# PulseRain_M10.net
KiCad netlist of a schematic drawn in EAGLE
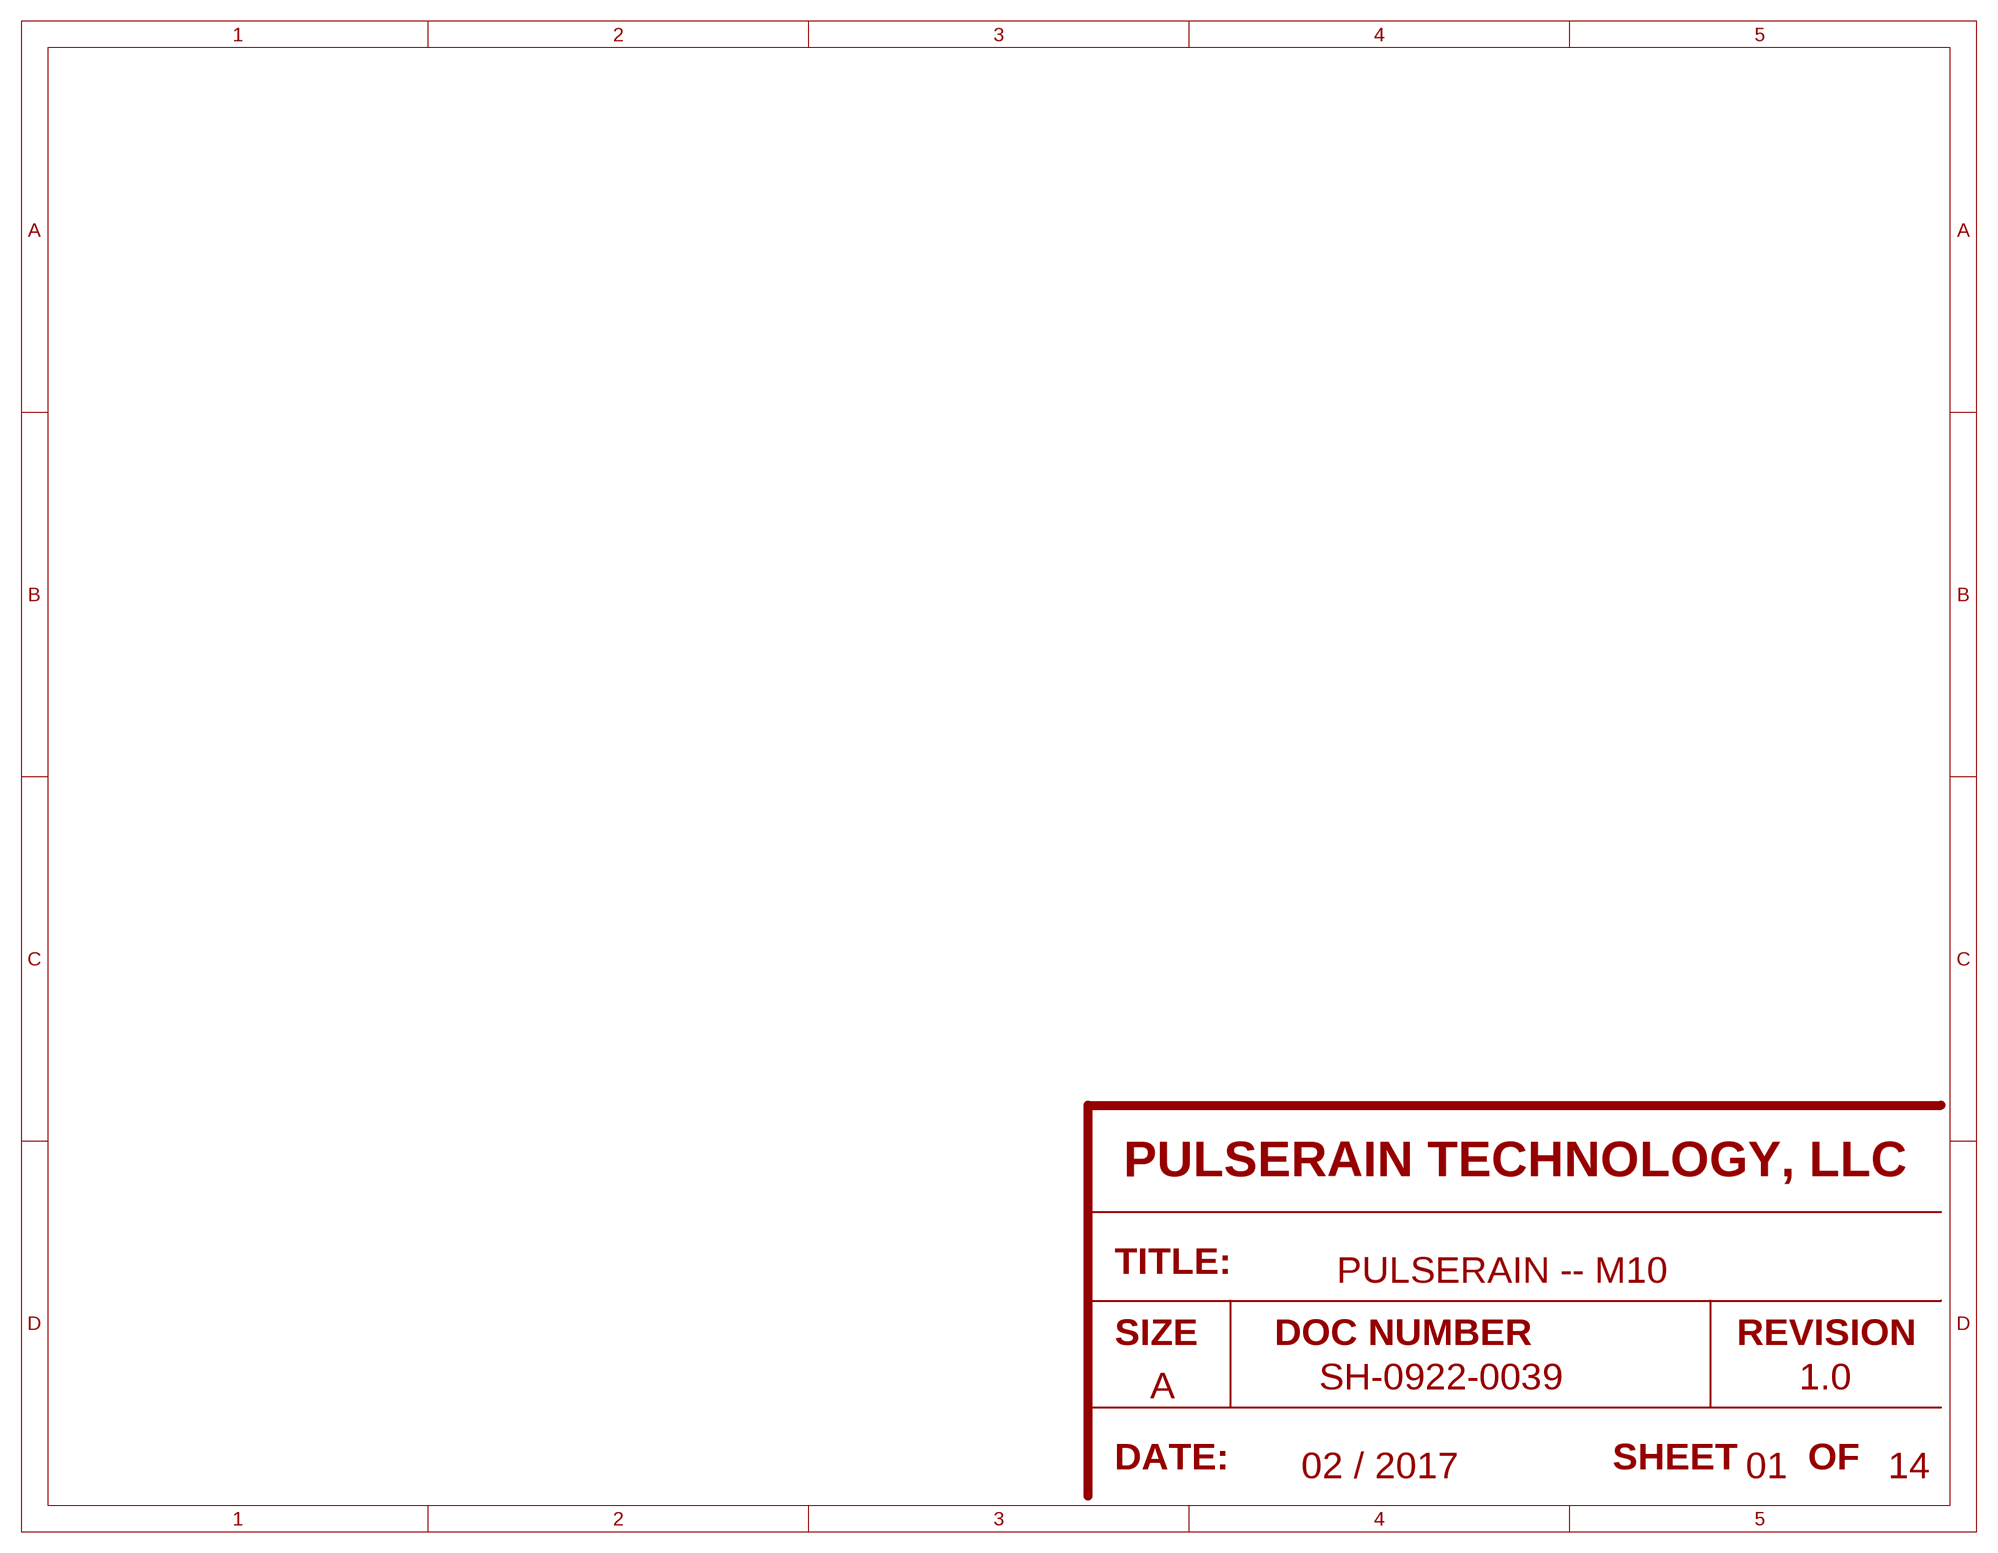
[diagram p0: schematic, sheet 1]
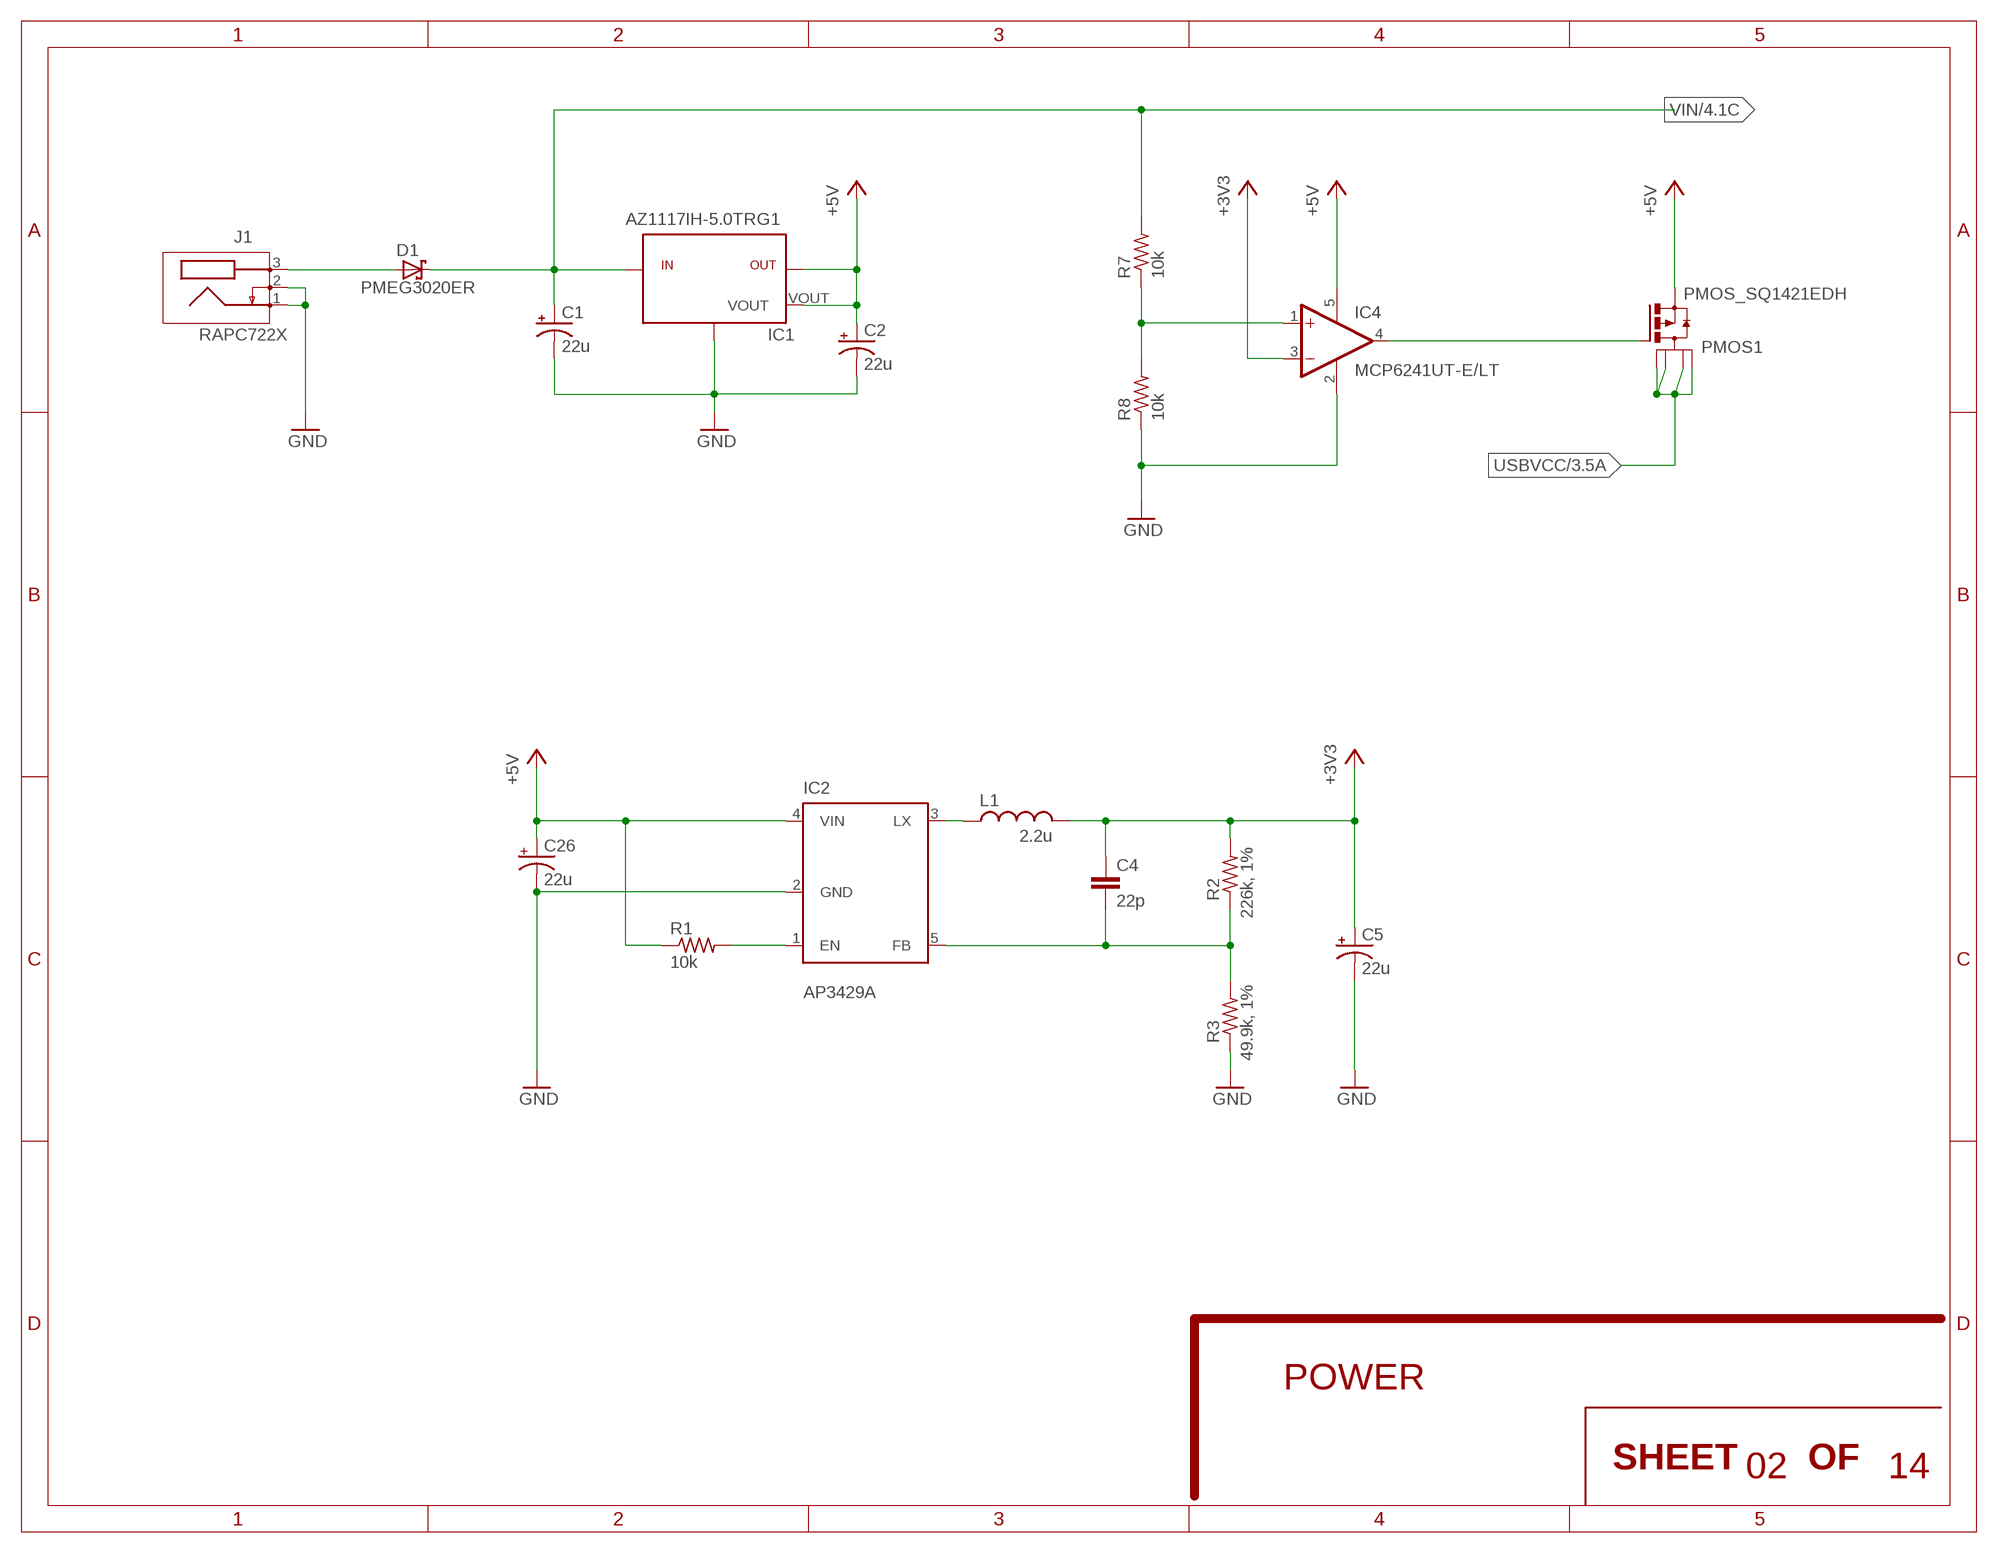
[diagram p1: schematic, sheet 2]
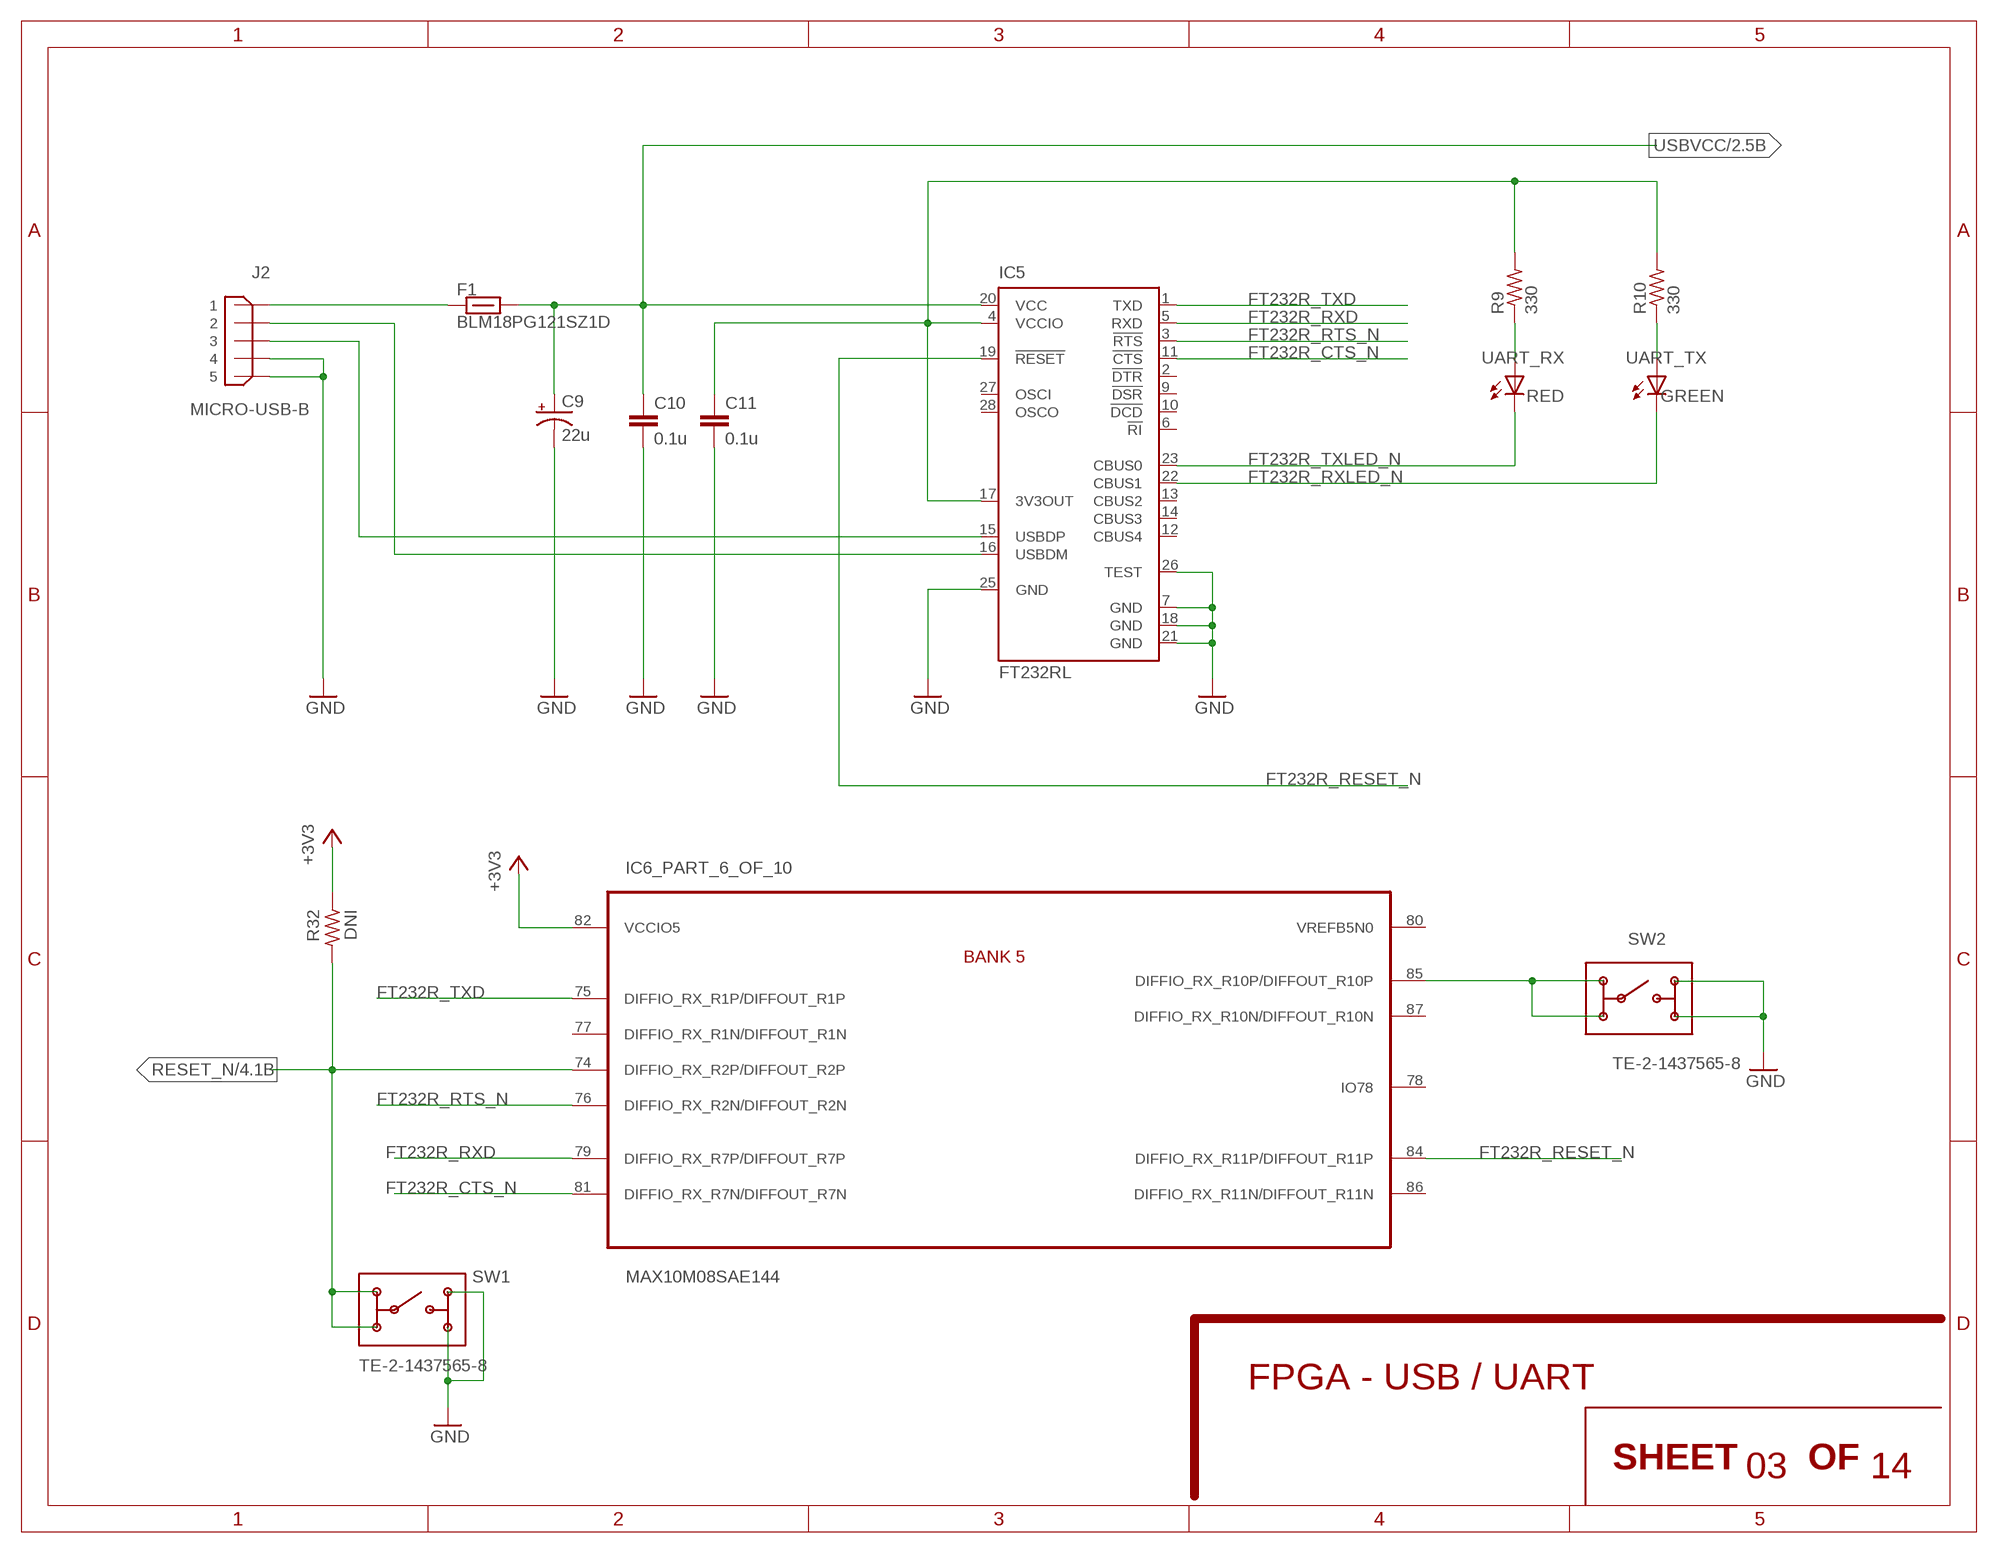
[diagram p2: schematic, sheet 3]
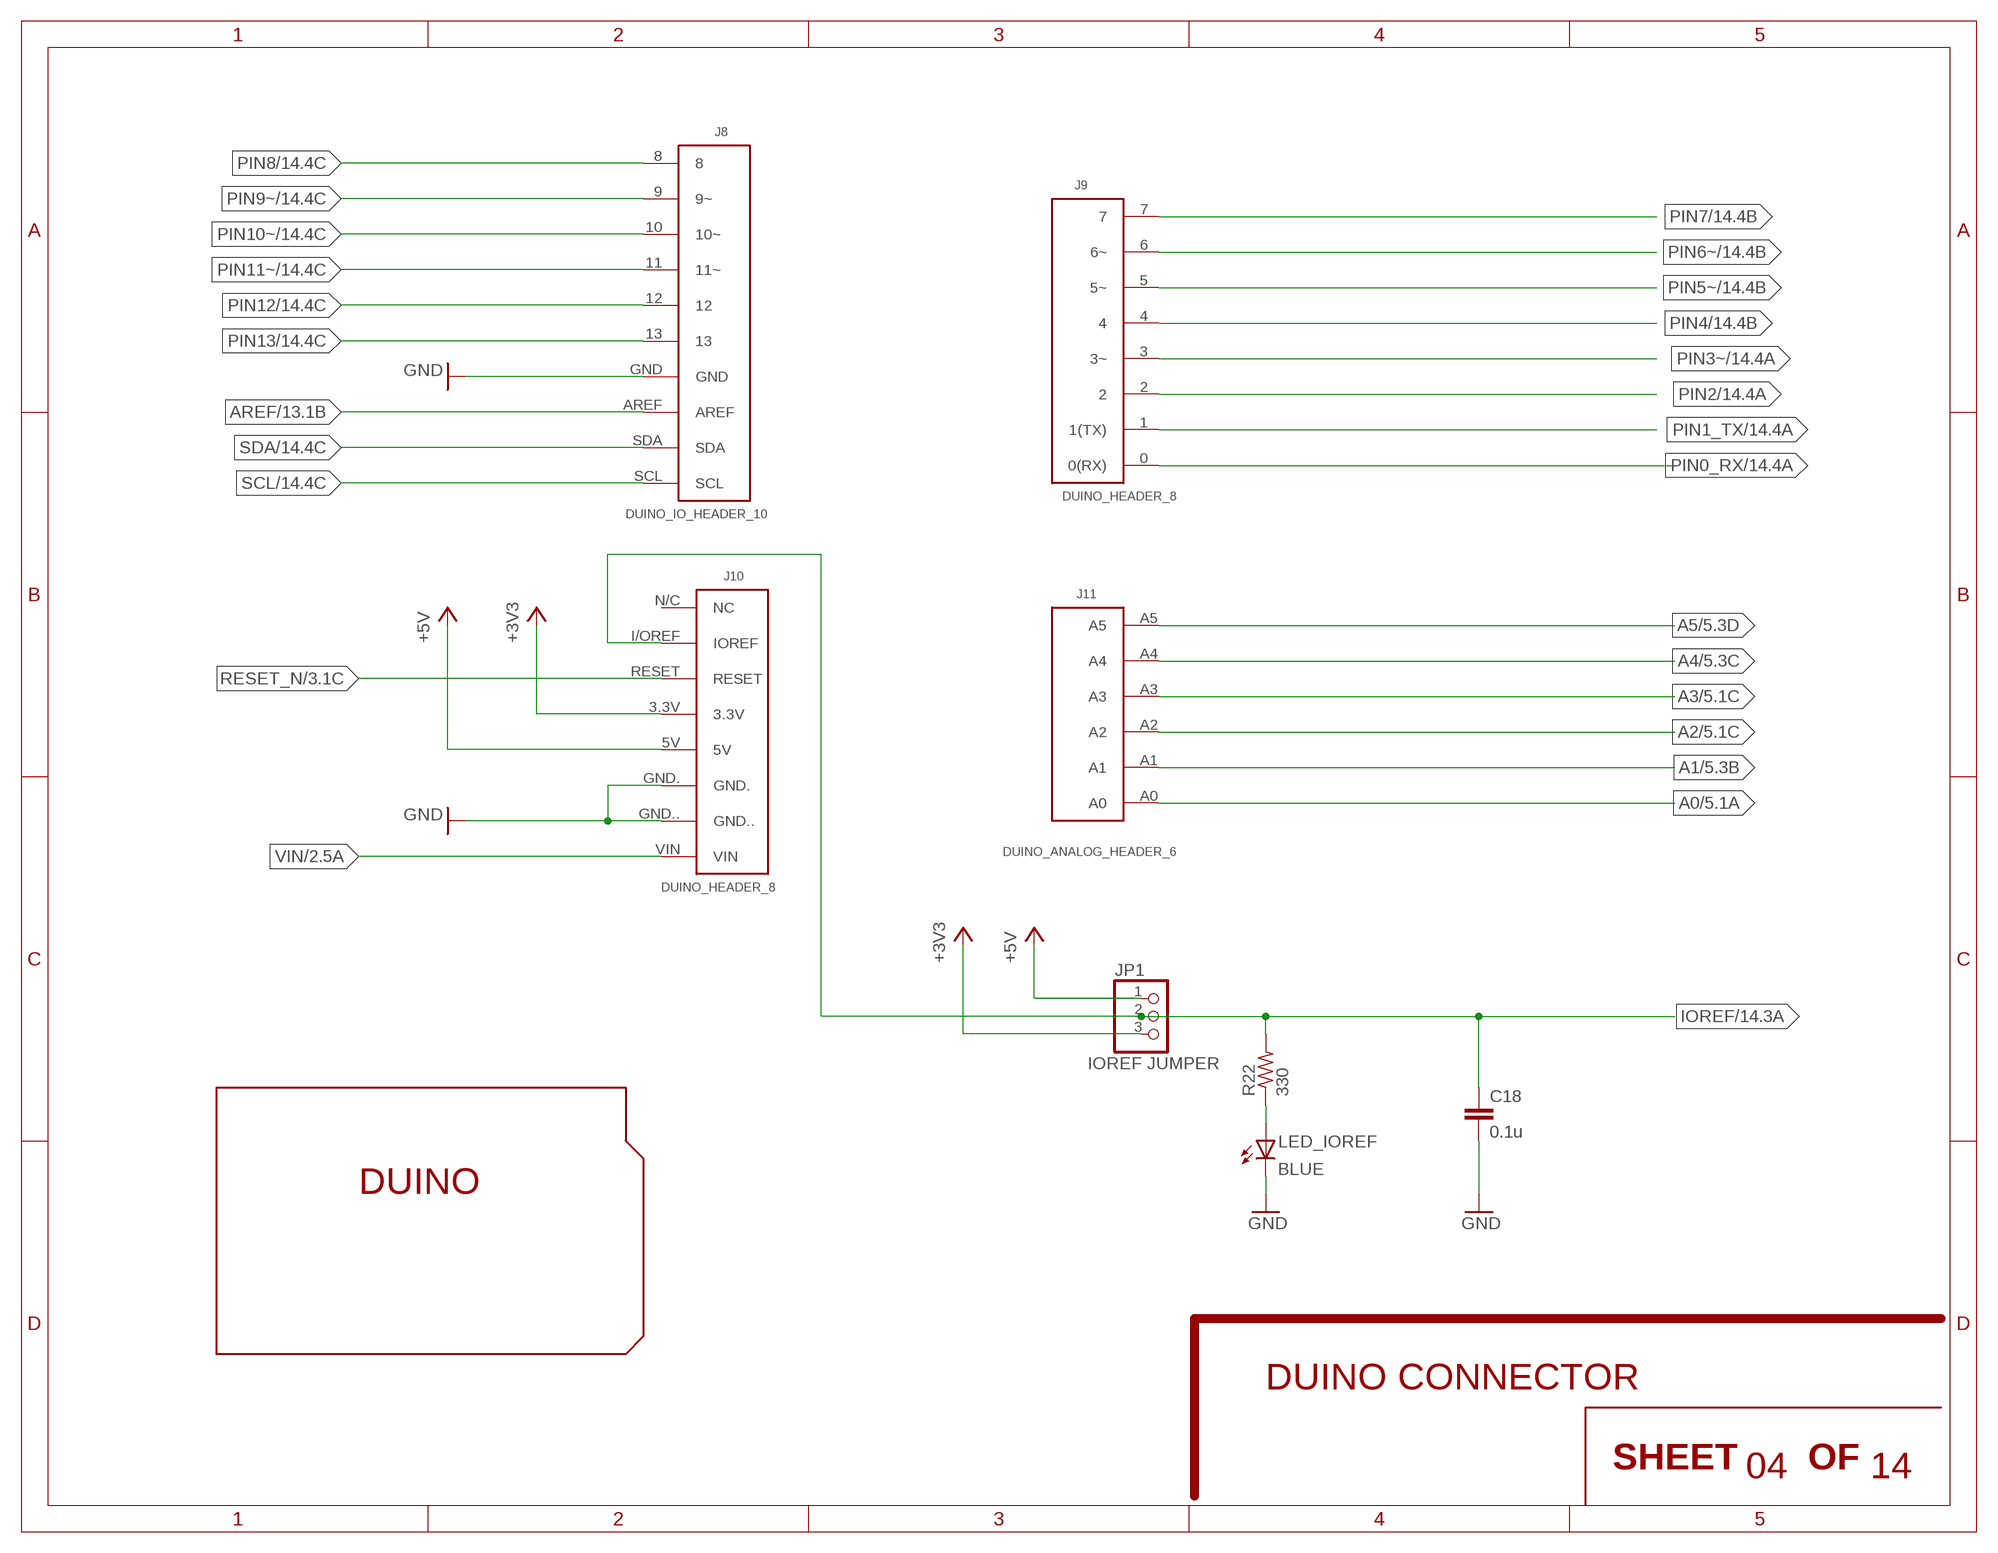
[diagram p3: schematic, sheet 4]
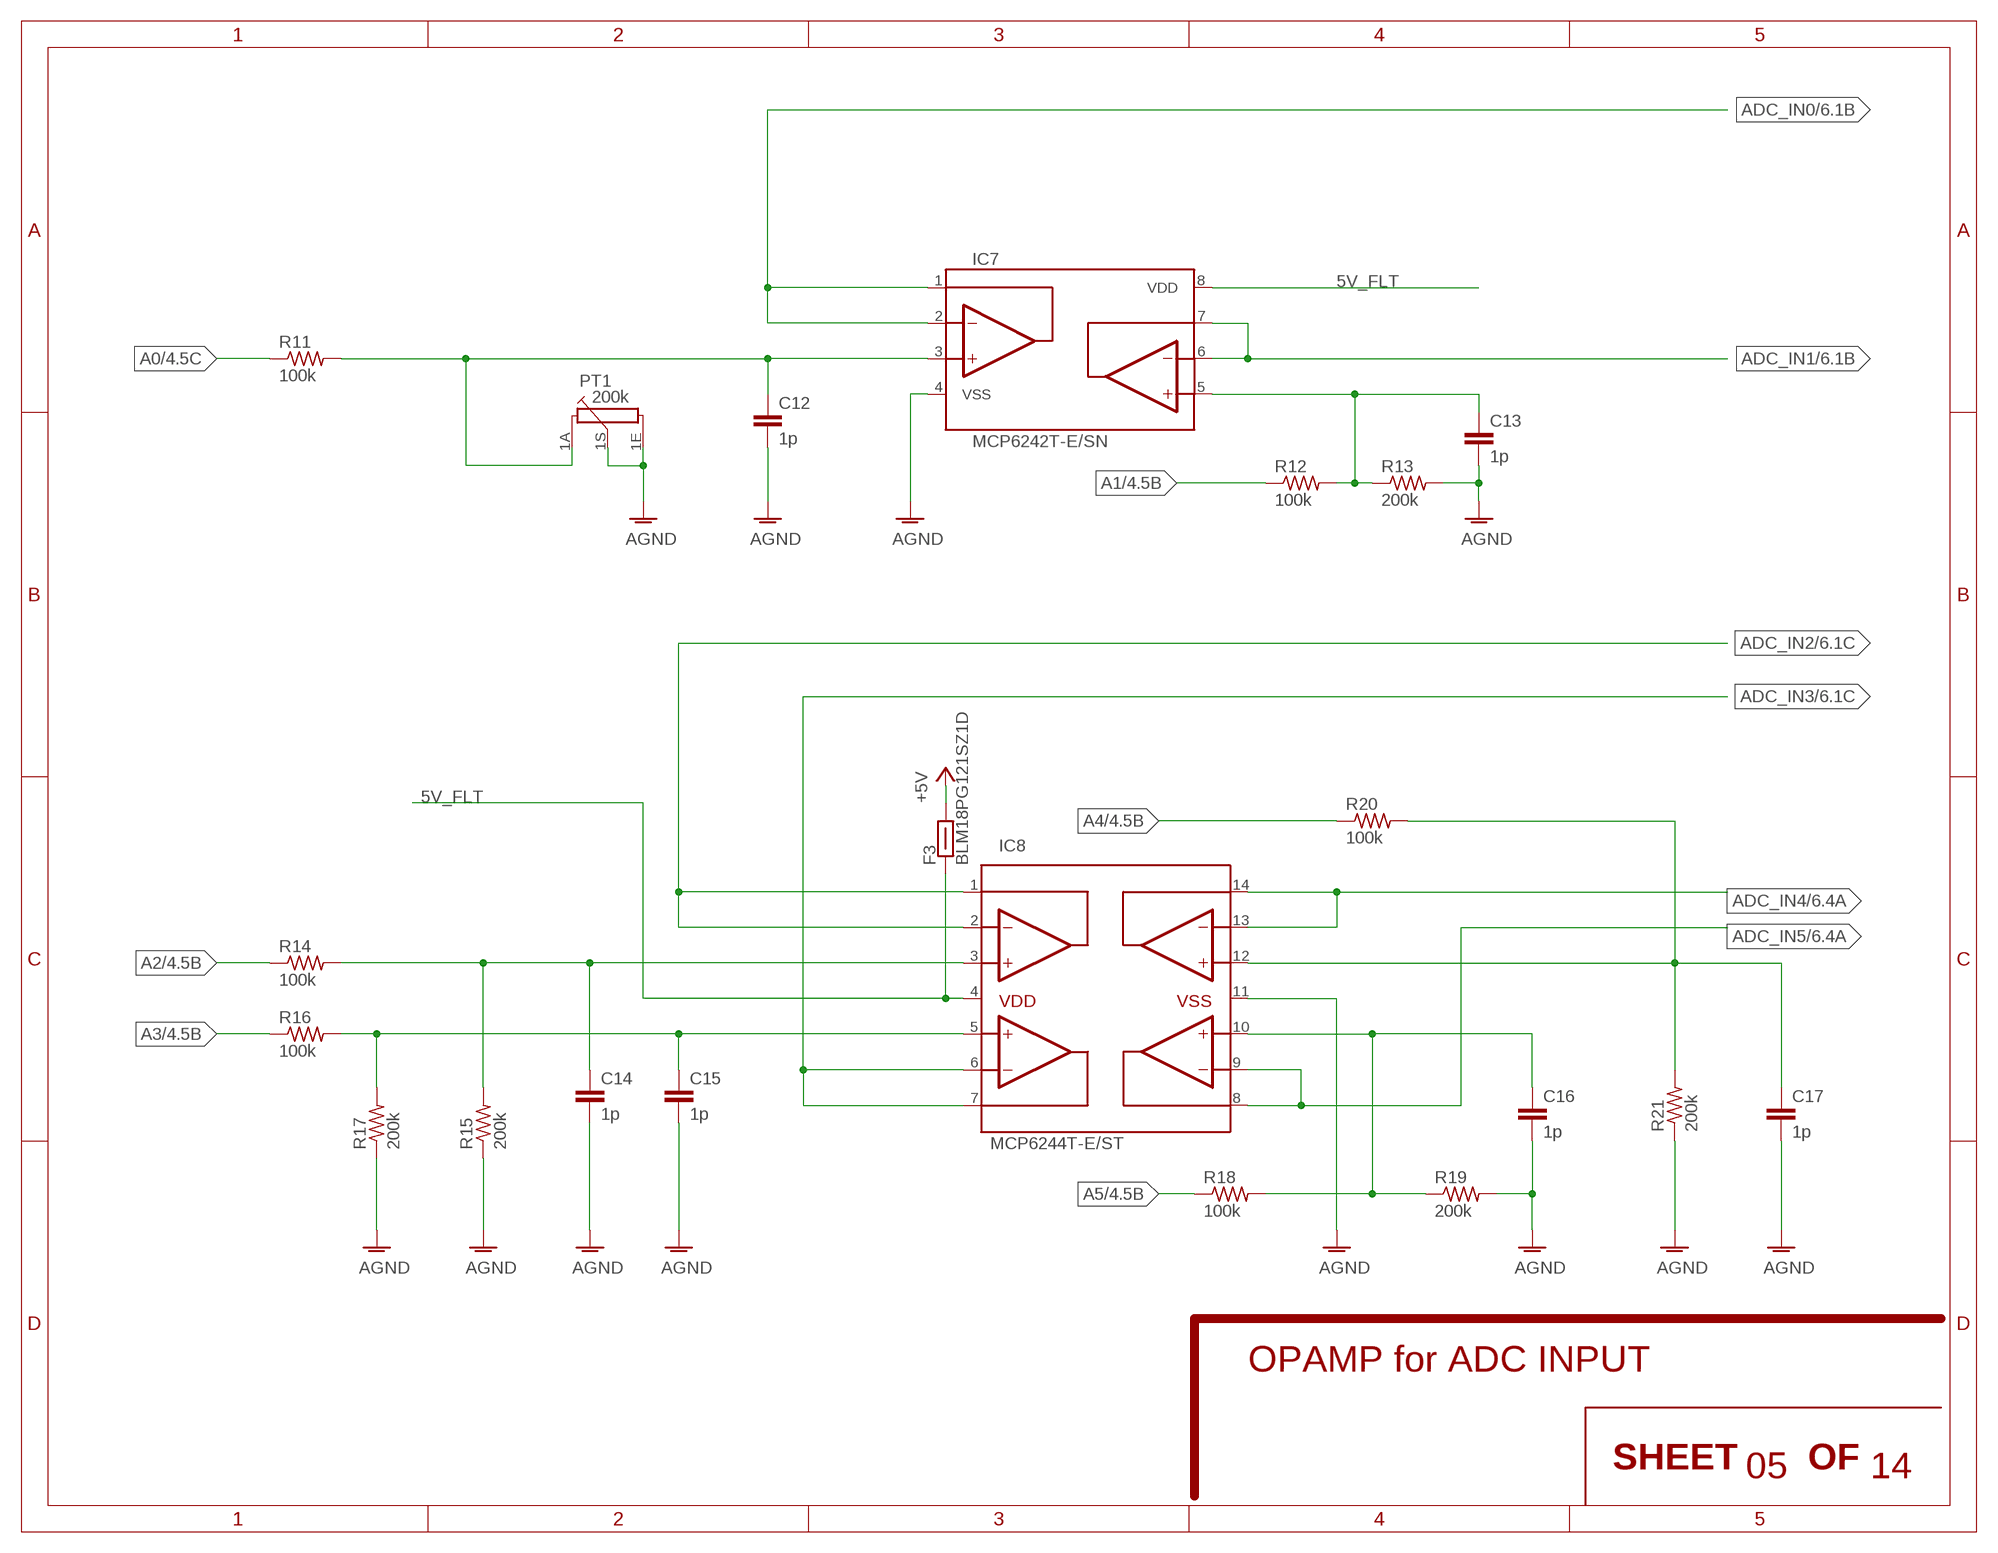
[diagram p4: schematic, sheet 5]
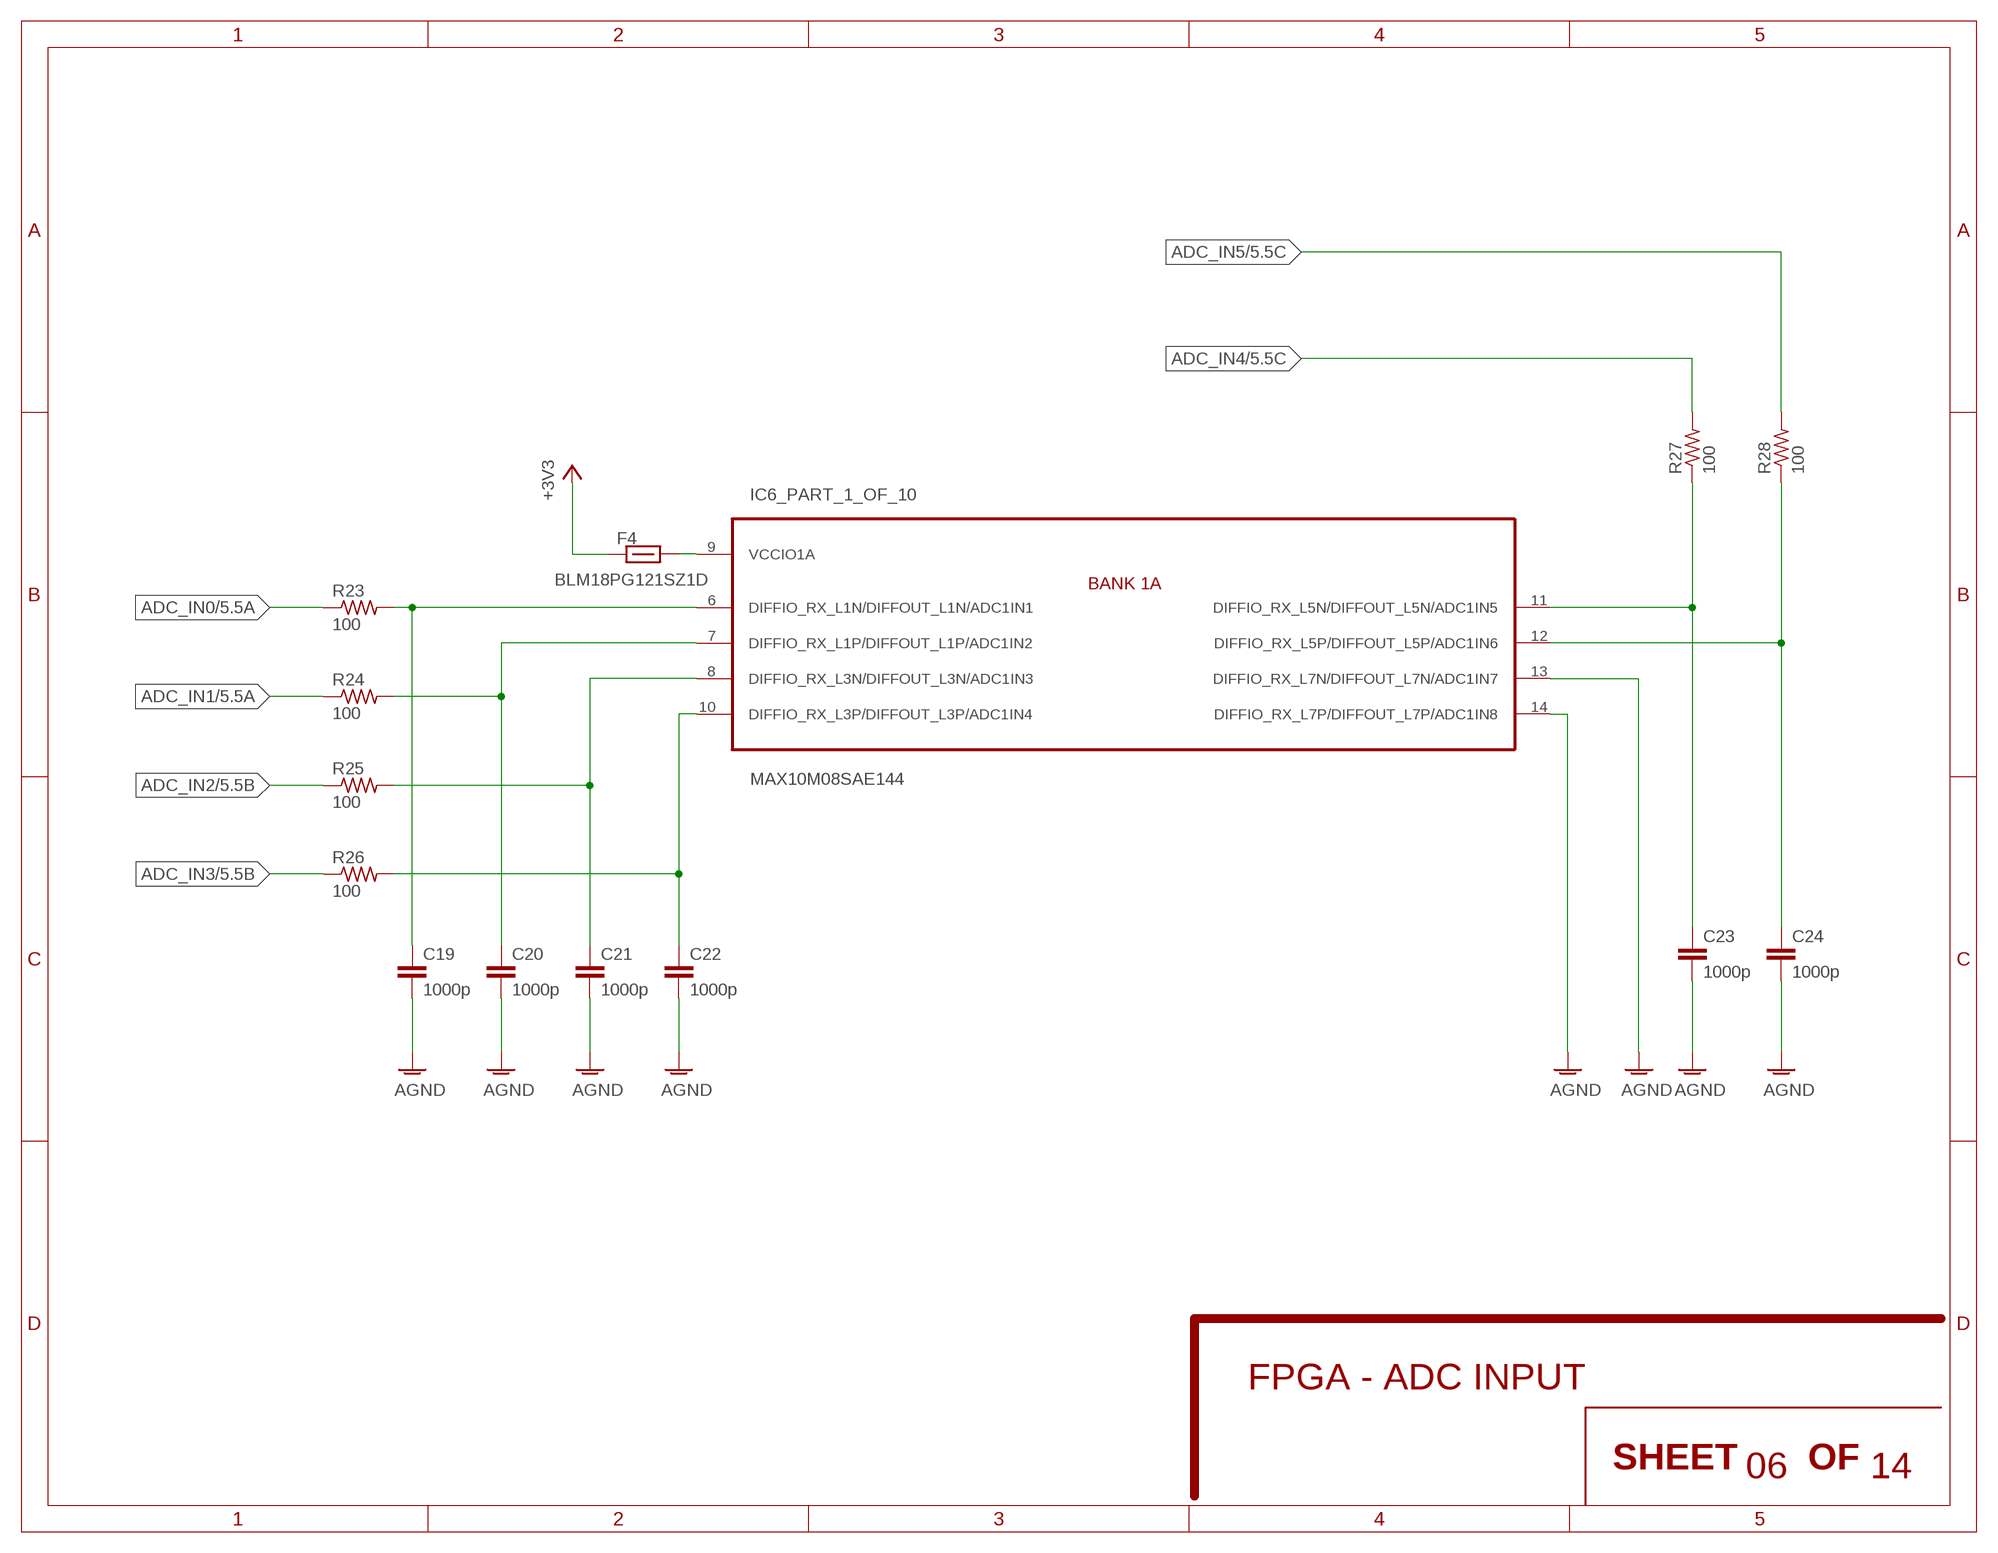
[diagram p5: schematic, sheet 6]
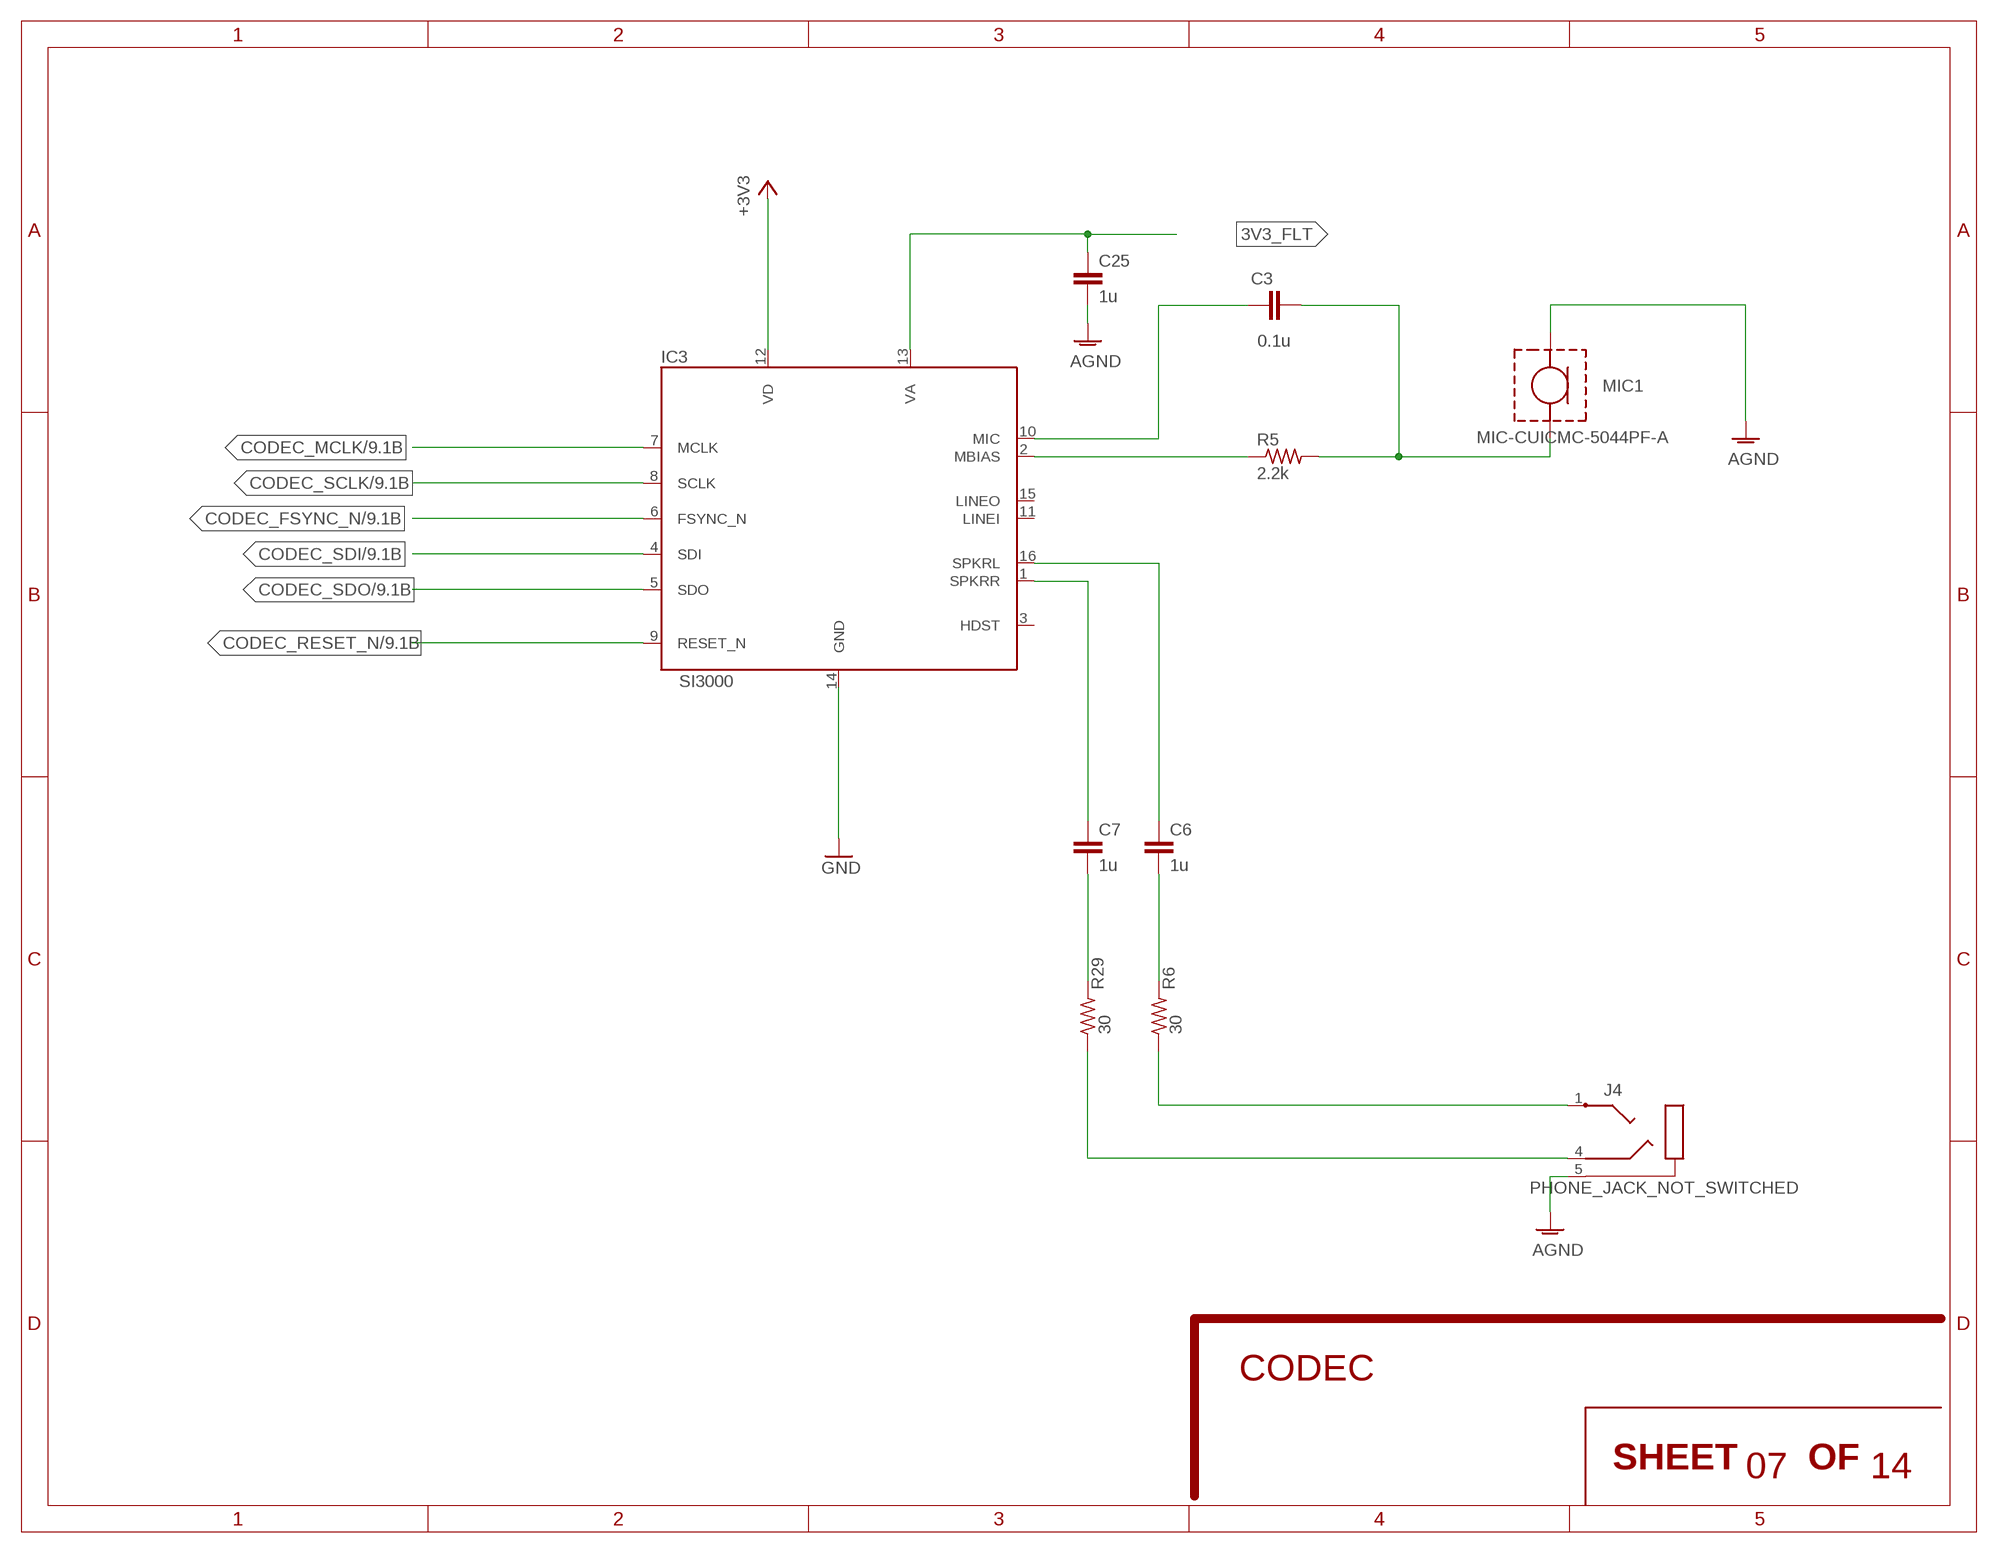
[diagram p6: schematic, sheet 7]
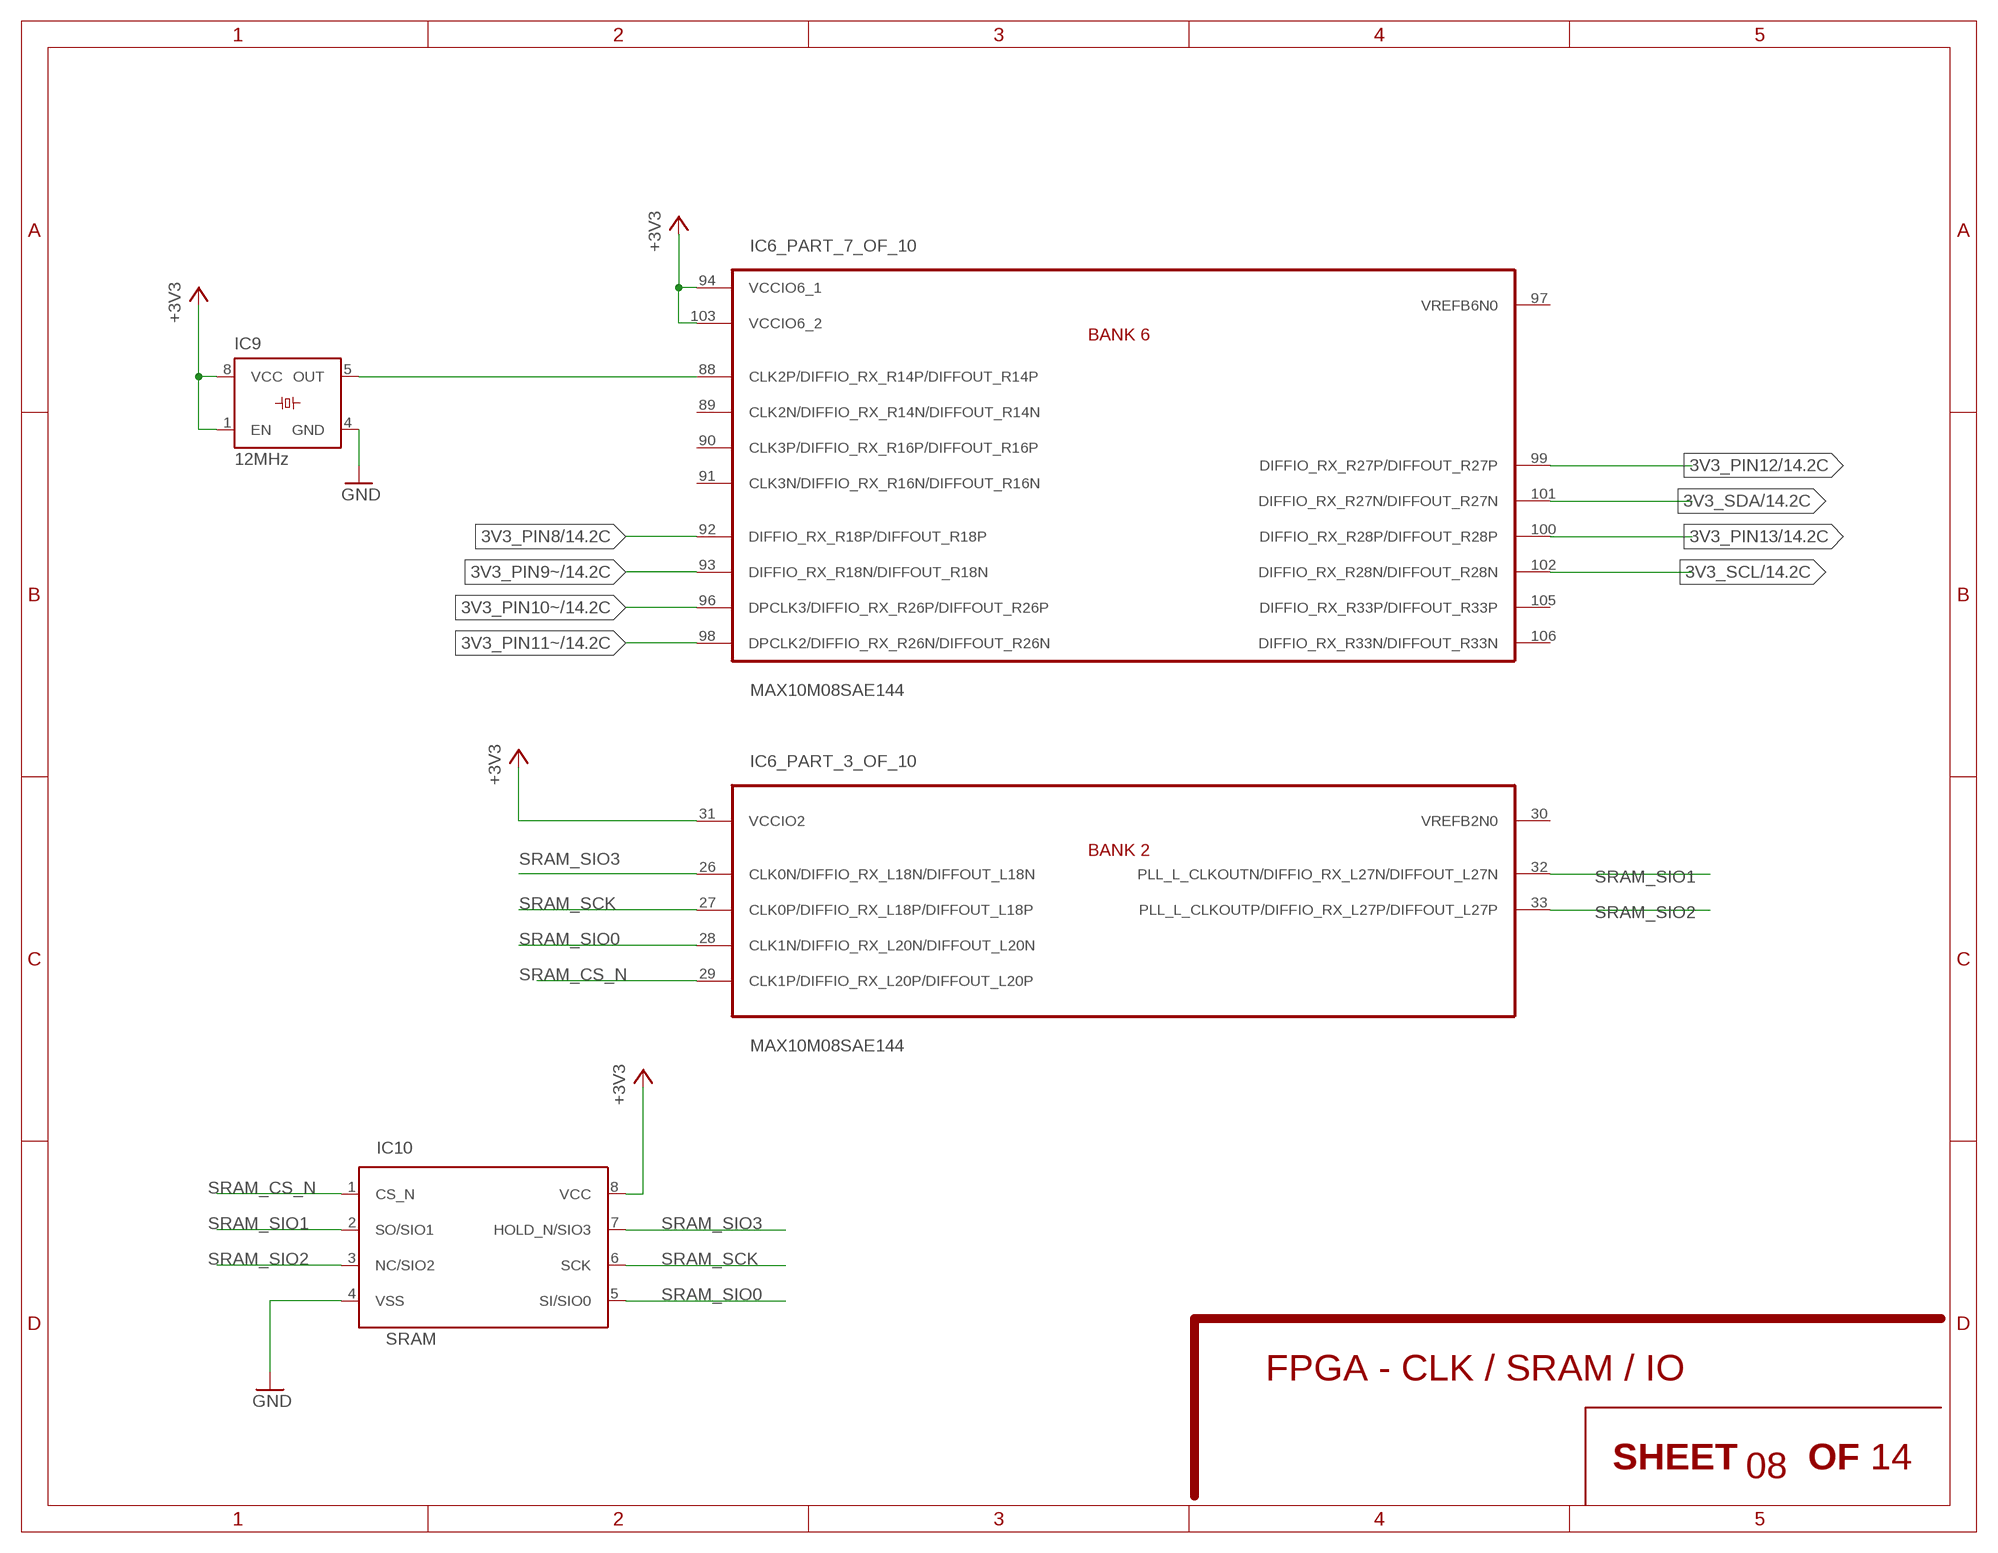
[diagram p7: schematic, sheet 8]
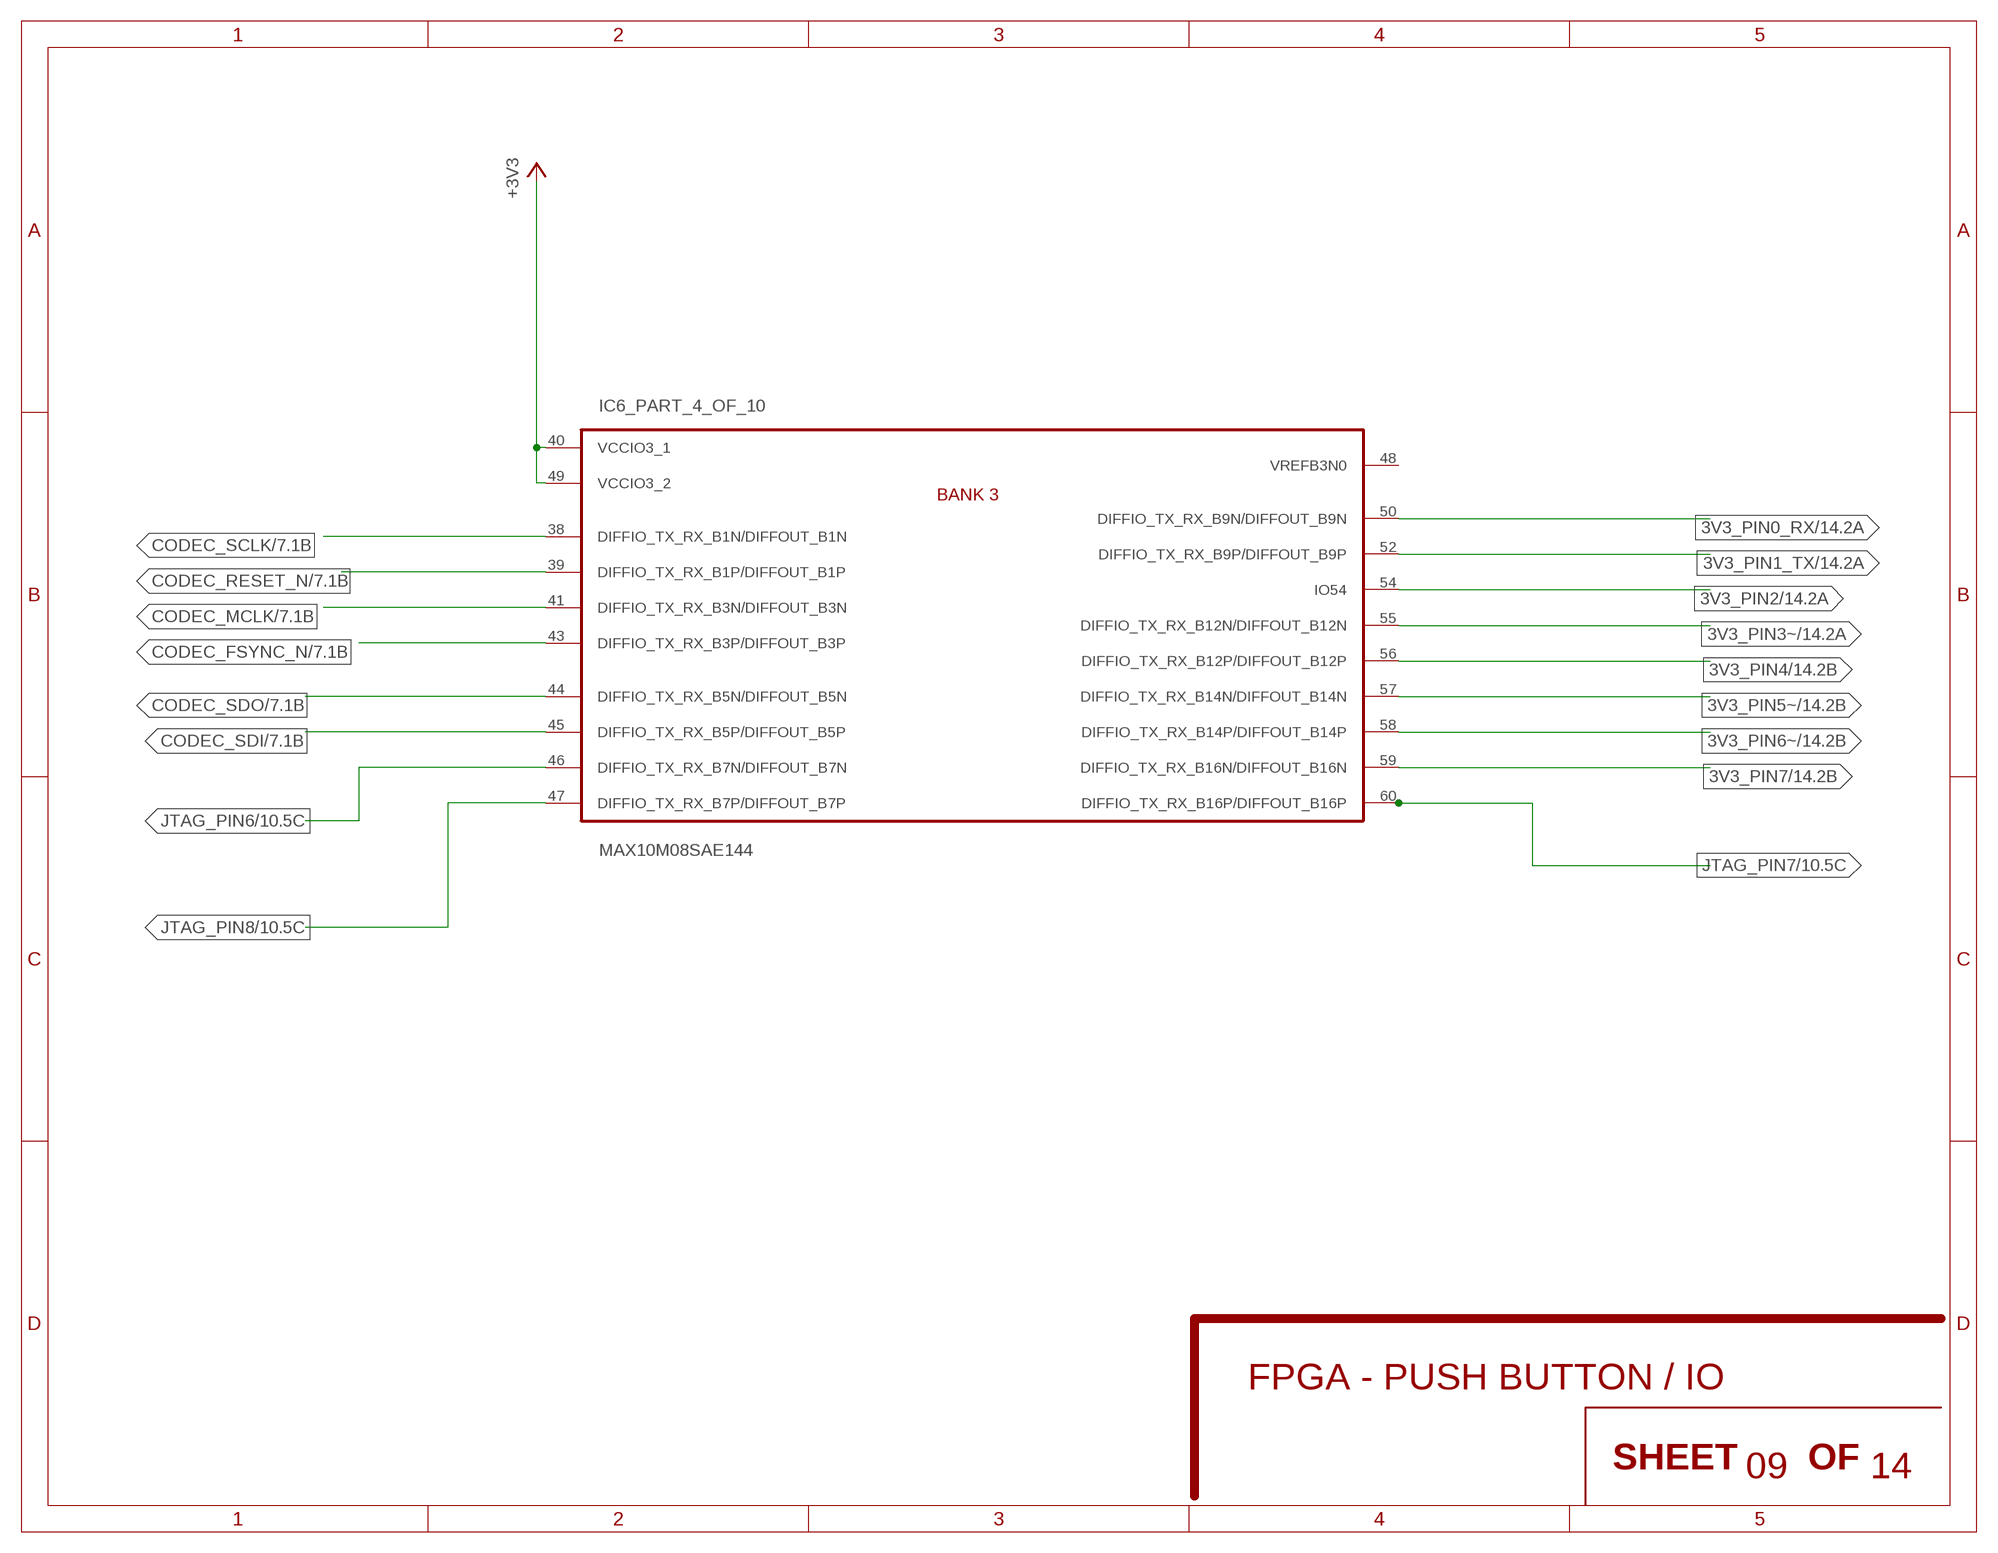
[diagram p8: schematic, sheet 9]
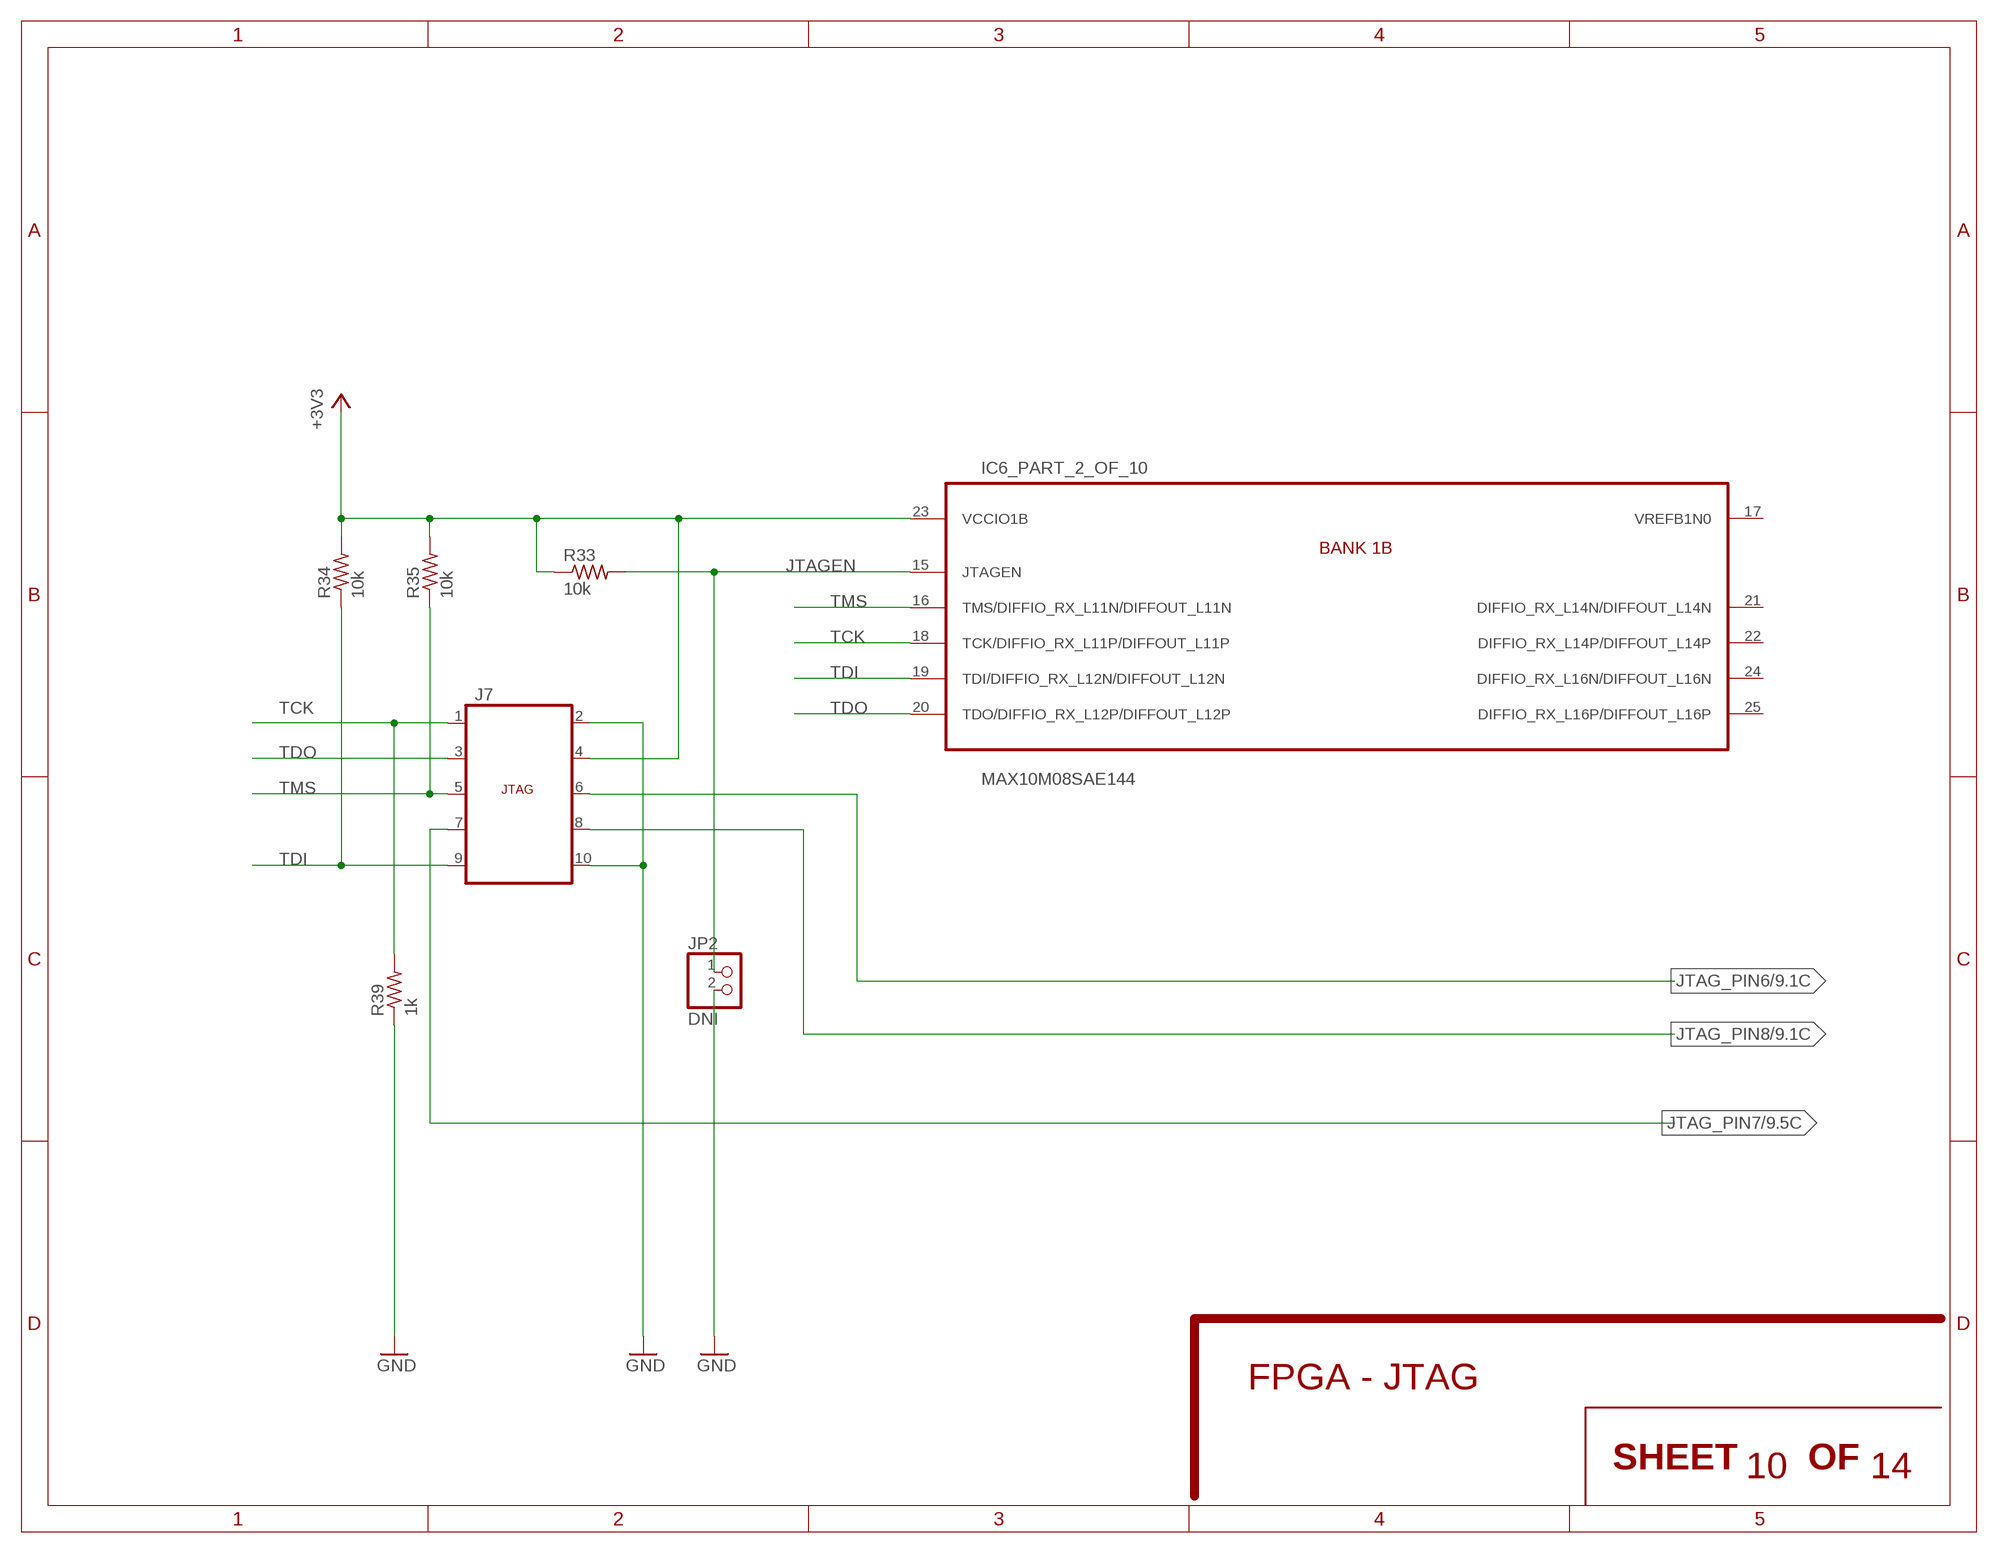
[diagram p9: schematic, sheet 10]
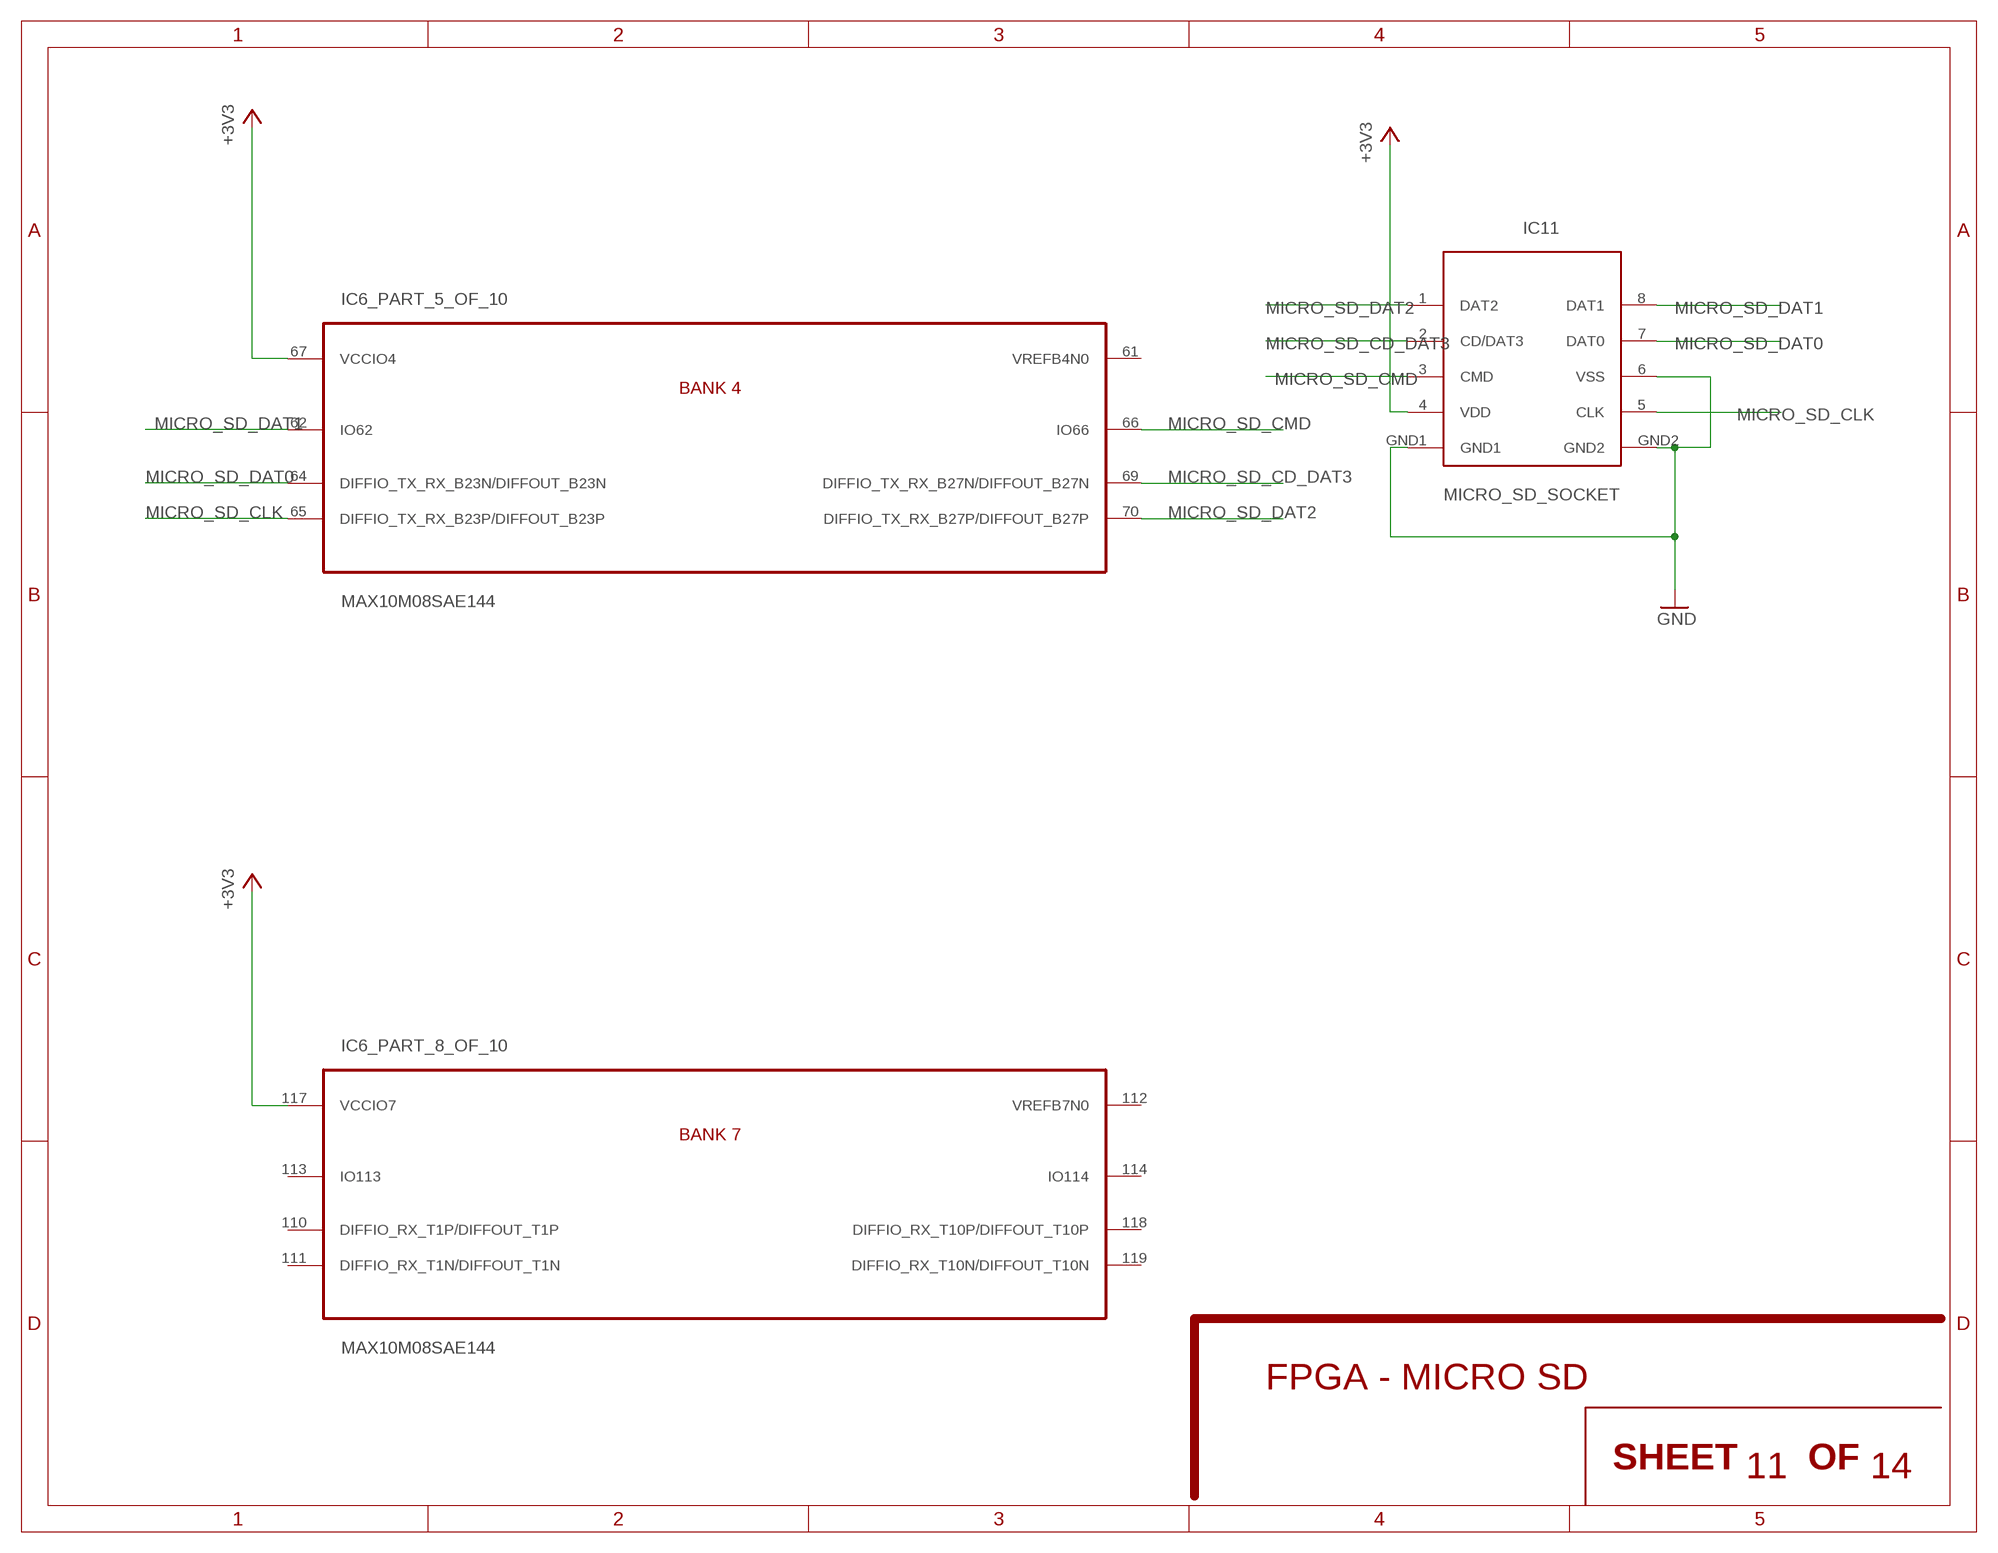
[diagram p10: schematic, sheet 11]
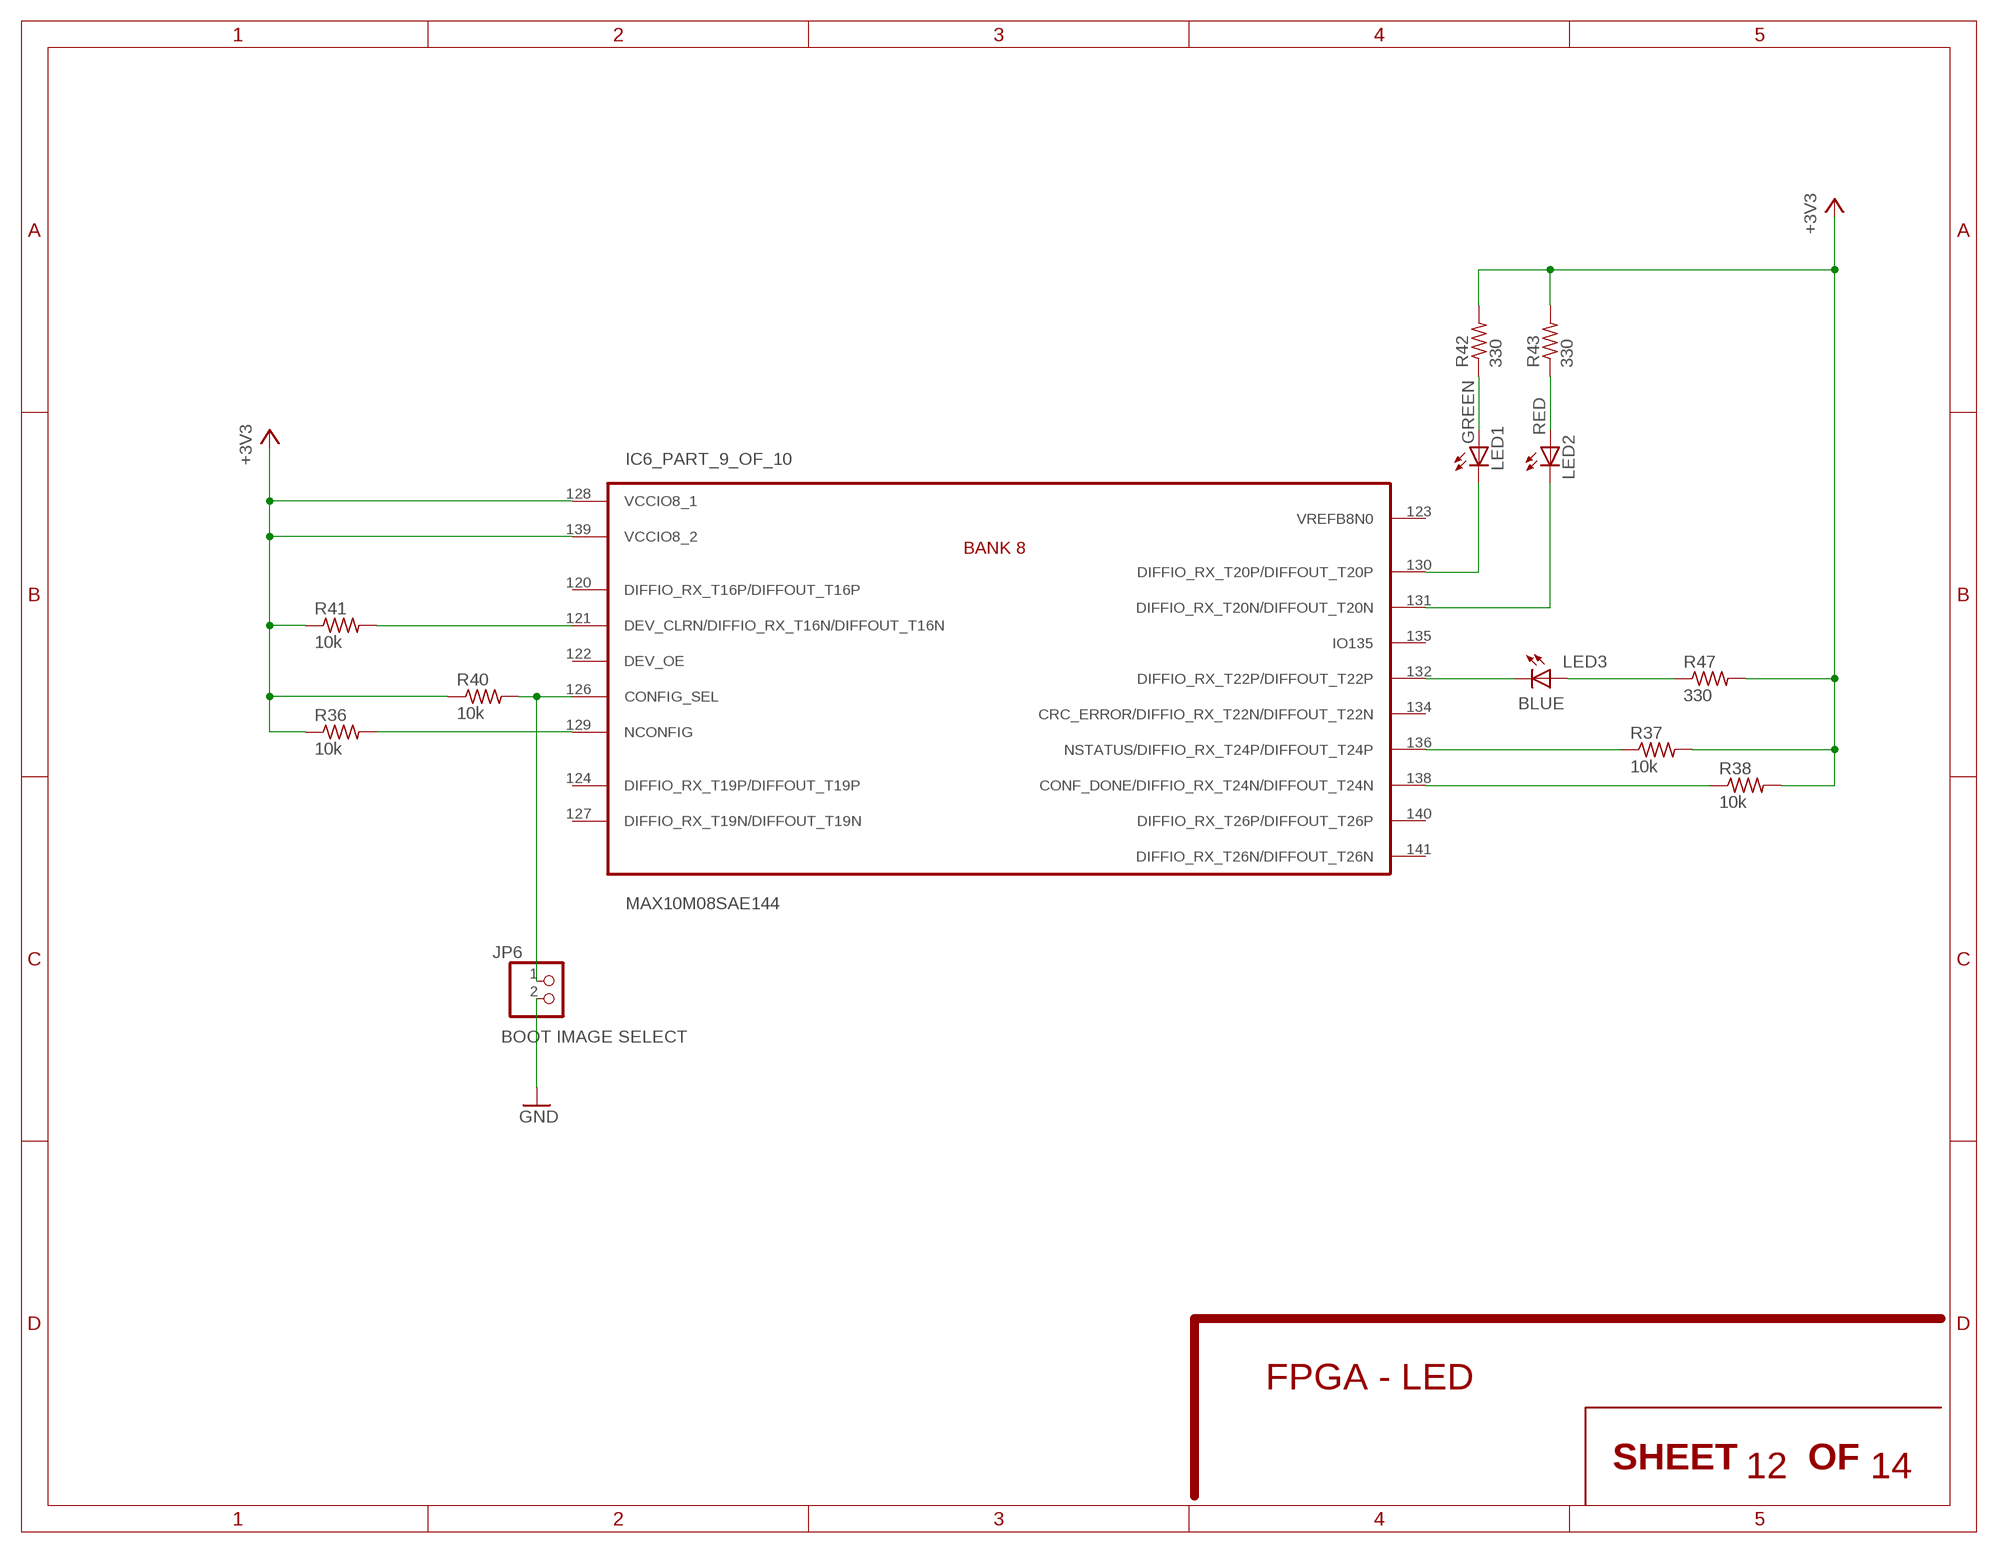
[diagram p11: schematic, sheet 12]
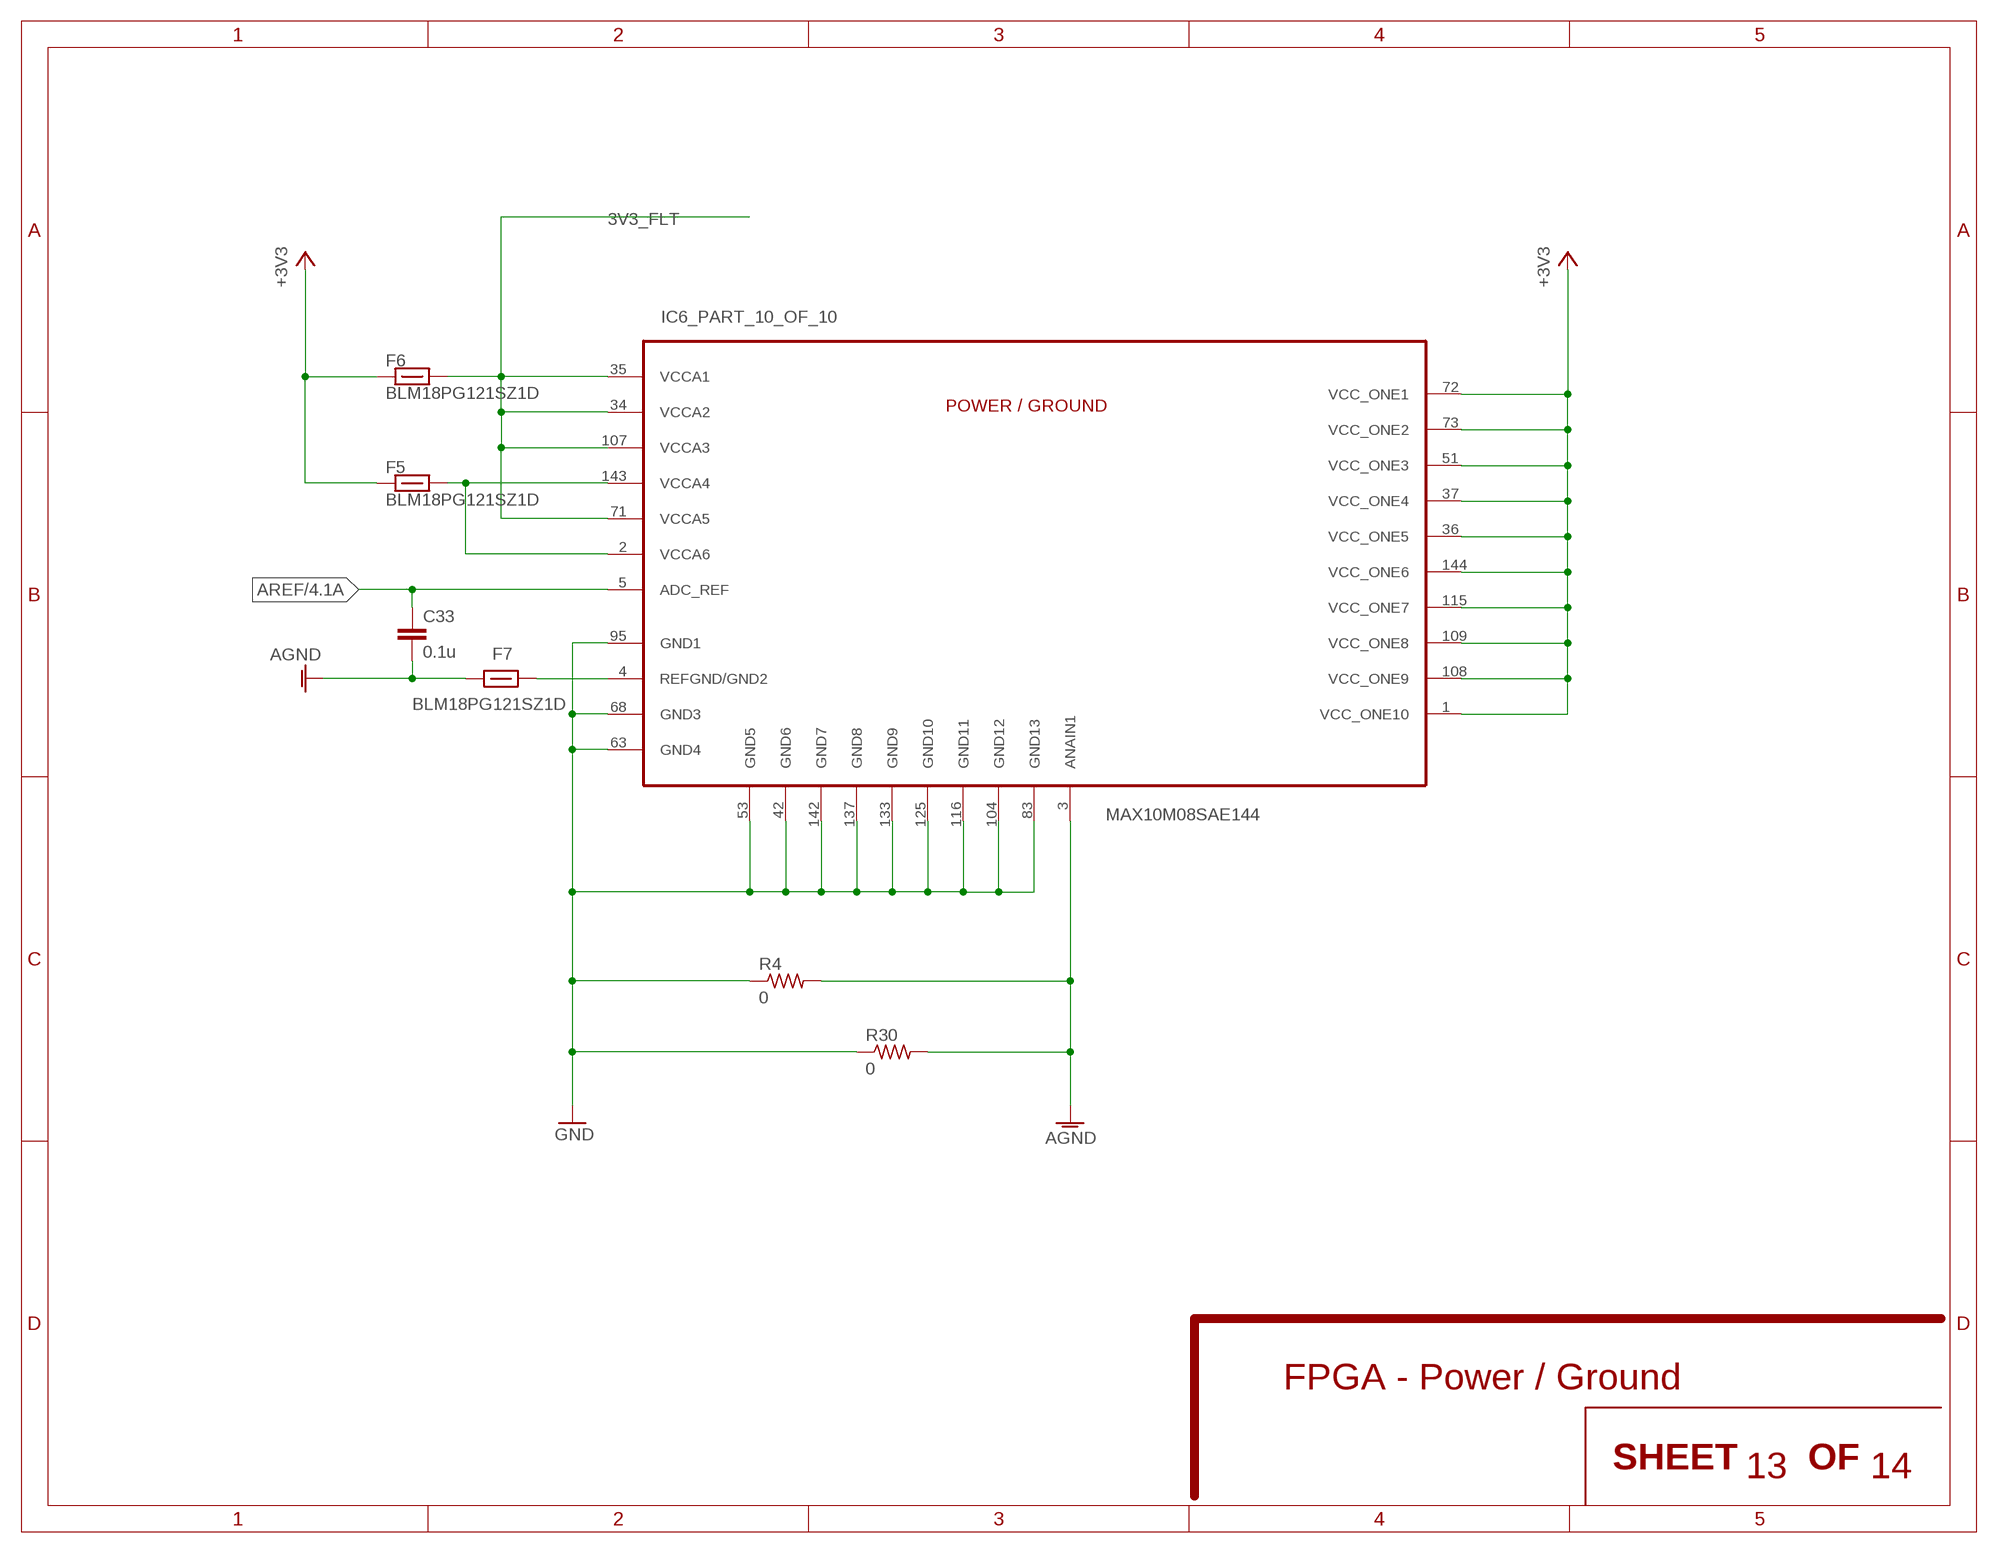
[diagram p12: schematic, sheet 13]
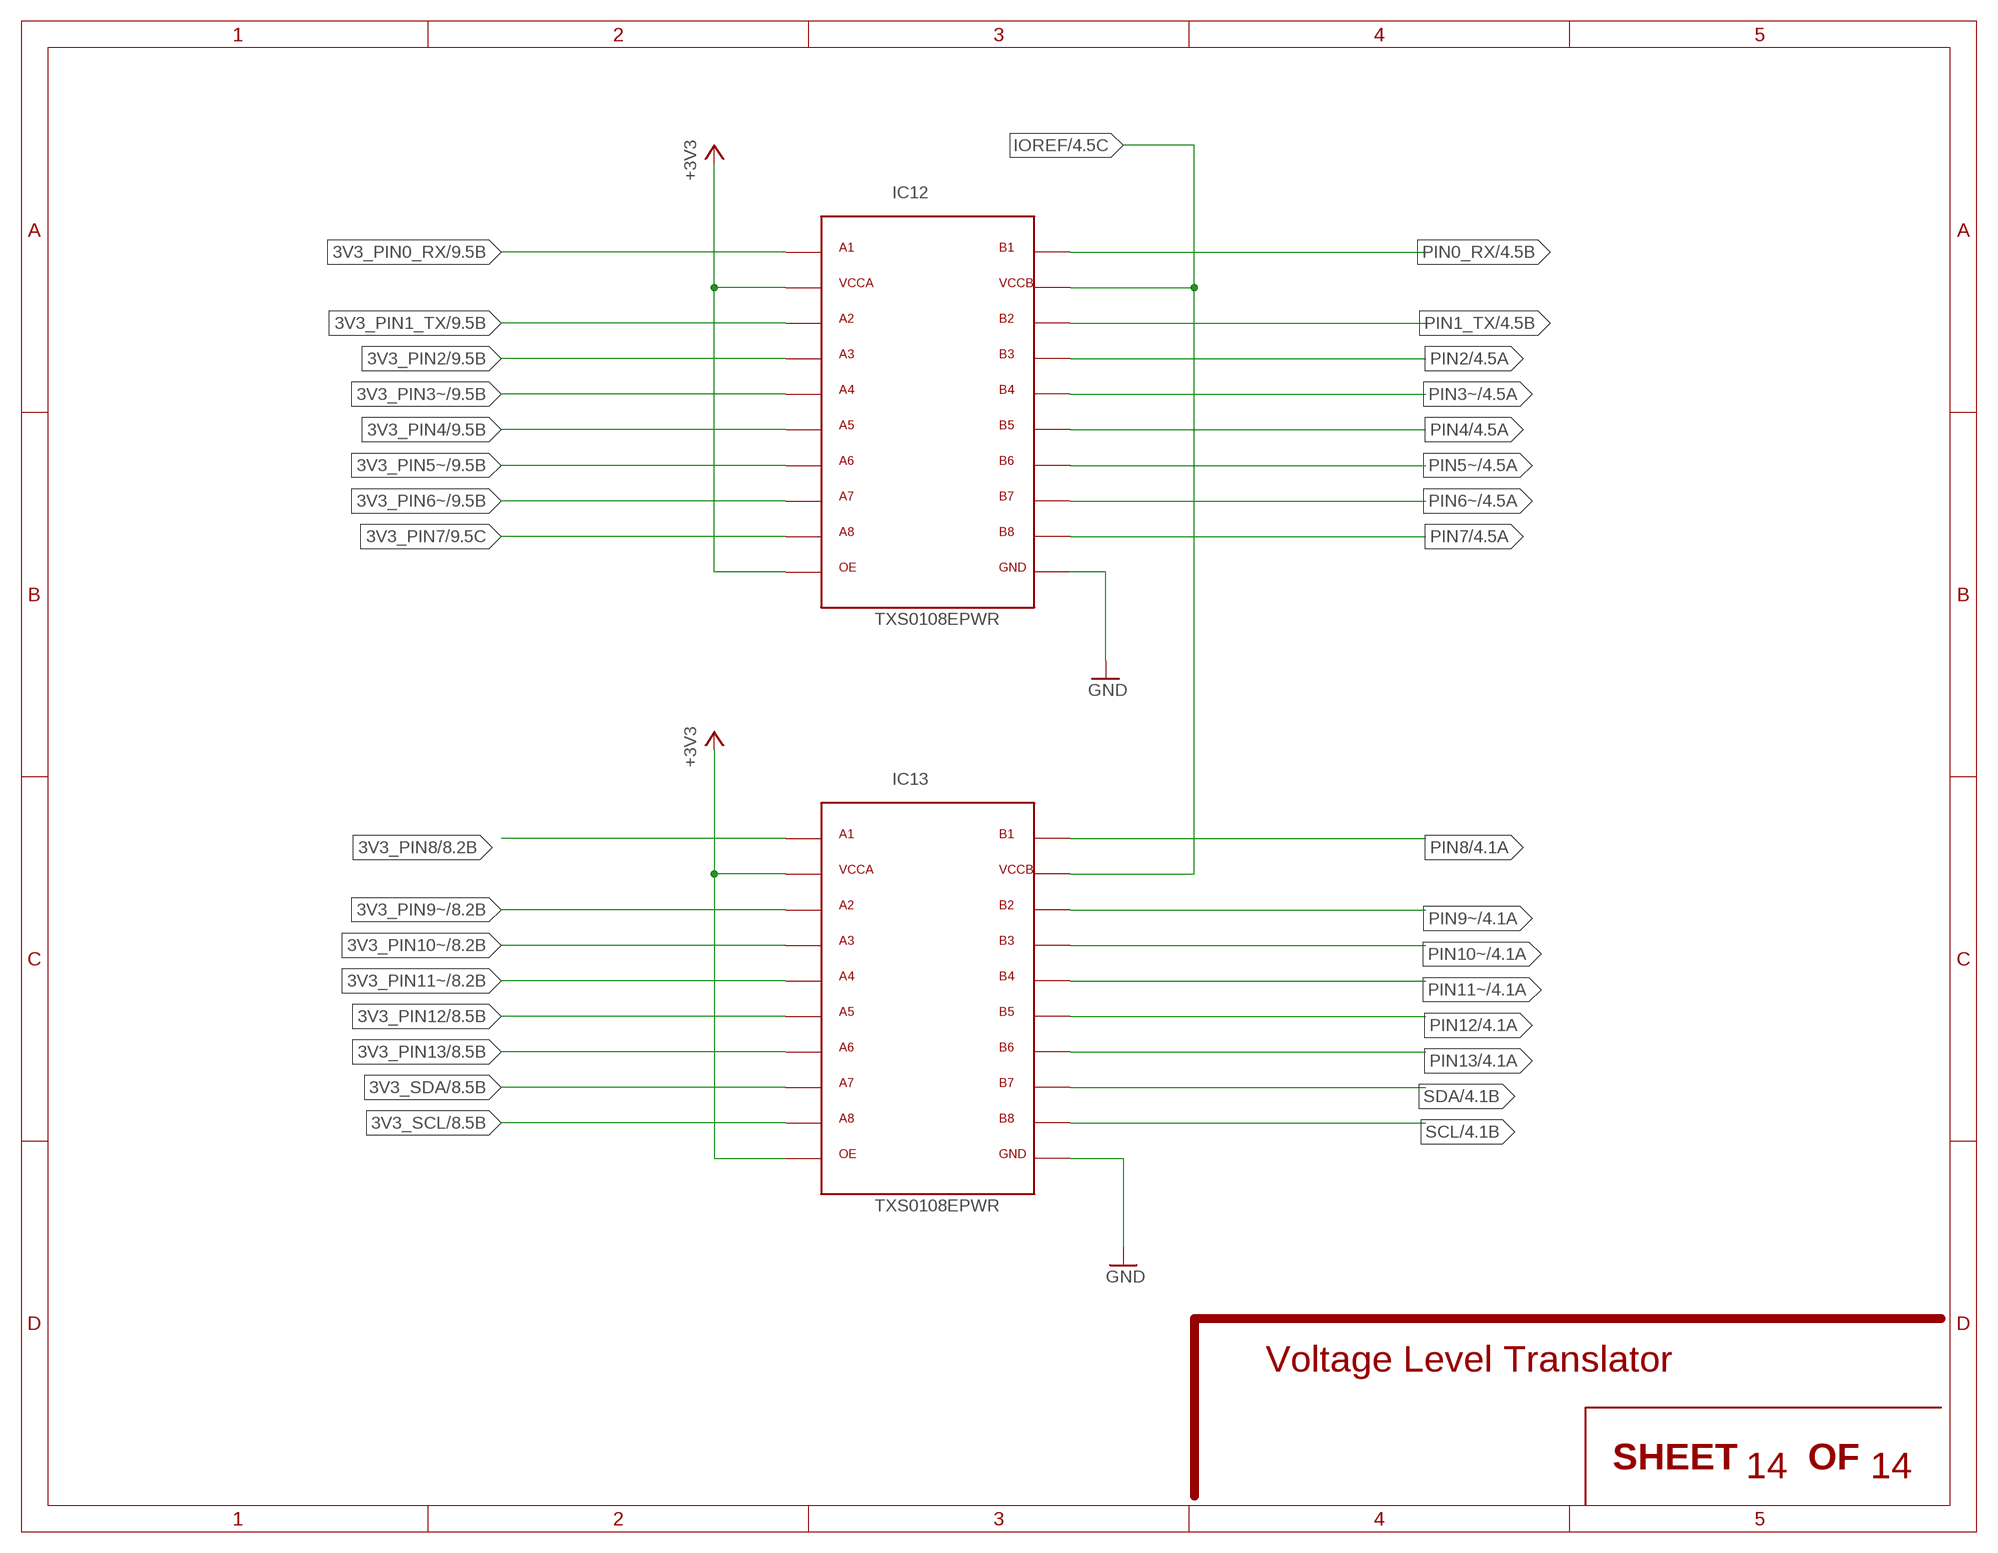
[diagram p13: schematic, sheet 14]

(export (version "E")
  (design (tool "Eeschema 10.0.6"))
  (components
    (comp (ref "IC12")
      (value "TXS0108EPWR")
      (footprint "eagle-import:TSSOP8")
      (fields (field (name "MF") "Texas Instruments"))
      (libsource (lib "eagle-import") (part "TXS0108E"))
    )
    (comp (ref "IC13")
      (value "TXS0108EPWR")
      (footprint "eagle-import:TSSOP8")
      (fields (field (name "MF") "Texas Instruments"))
      (libsource (lib "eagle-import") (part "TXS0108E"))
    )
    (comp (ref "IC6")
      (value "MAX10M08SAE144")
      (footprint "eagle-import:EQFP144")
      (fields (field (name "MF") "Altera") (field (name "MPN") "10M08SAE144C8G"))
      (libsource (lib "eagle-import") (part "MAX10M08SAE144"))
    )
    (comp (ref "C1")
      (value "22u")
      (footprint "eagle-import:PANASONIC_B")
      (fields (field (name "MF") "Panasonic") (field (name "MPN") "EEE-FK1A220AR"))
      (libsource (lib "eagle-import") (part "CPOL_USB22U"))
    )
    (comp (ref "C2")
      (value "22u")
      (footprint "eagle-import:PANASONIC_B")
      (fields (field (name "MF") "Panasonic") (field (name "MPN") "EEE-FK1A220AR"))
      (libsource (lib "eagle-import") (part "CPOL_USB22U"))
    )
    (comp (ref "C4")
      (value "22p")
      (footprint "eagle-import:0603-CAP")
      (fields (field (name "MF") "Vishay") (field (name "MPN") "VJ0603A220JXACW1BC"))
      (libsource (lib "eagle-import") (part "C-US_22P"))
    )
    (comp (ref "C5")
      (value "22u")
      (footprint "eagle-import:PANASONIC_B")
      (fields (field (name "MF") "Panasonic") (field (name "MPN") "EEE-FK1A220AR"))
      (libsource (lib "eagle-import") (part "CPOL_USB22U"))
    )
    (comp (ref "C26")
      (value "22u")
      (footprint "eagle-import:PANASONIC_B")
      (fields (field (name "MF") "Panasonic") (field (name "MPN") "EEE-FK1A220AR"))
      (libsource (lib "eagle-import") (part "CPOL_USB22U"))
    )
    (comp (ref "D1")
      (value "PMEG3020ER")
      (footprint "eagle-import:SOD123W")
      (fields (field (name "MF") "NXP"))
      (libsource (lib "eagle-import") (part "PMEG3020ER"))
    )
    (comp (ref "IC1")
      (value "AZ1117IH-5.0TRG1")
      (footprint "eagle-import:SOT223")
      (fields (field (name "MF") "Diodes Incorporated"))
      (libsource (lib "eagle-import") (part "AZ1117IH-5.0TRG1"))
    )
    (comp (ref "IC2")
      (value "AP3429A")
      (footprint "eagle-import:TSOT25")
      (fields (field (name "MF") "Diodes Incorporated") (field (name "MPN") "AP3429AKTTR-G1"))
      (libsource (lib "eagle-import") (part "AP3429A"))
    )
    (comp (ref "IC4")
      (value "MCP6241UT-E/LT")
      (footprint "eagle-import:SC-70-5")
      (fields (field (name "MF") "Microchip Technology"))
      (libsource (lib "eagle-import") (part "MCP6241UT-E/LT"))
    )
    (comp (ref "J1")
      (value "RAPC722X")
      (footprint "eagle-import:RAPC722X")
      (fields (field (name "MF") "Switchcraft"))
      (libsource (lib "eagle-import") (part "RAPC722X"))
    )
    (comp (ref "L1")
      (value "2.2u")
      (footprint "eagle-import:DFE252012C")
      (fields (field (name "MF") "muRata") (field (name "MPN") "1239AS-H-2R2M=P2"))
      (libsource (lib "eagle-import") (part "L-US_2.2U"))
    )
    (comp (ref "PMOS1")
      (value "PMOS_SQ1421EDH")
      (footprint "eagle-import:SC70-6L")
      (fields (field (name "MF") "Vishay") (field (name "MPN") " SQ1421EDH-T1_GE3 "))
      (libsource (lib "eagle-import") (part "PMOS_SQ1421EDH"))
    )
    (comp (ref "R1")
      (value "10k")
      (footprint "eagle-import:VISHAY-R-0603")
      (fields (field (name "MF") "Vishay") (field (name "MPN") "CRCW060310K0FKEA"))
      (libsource (lib "eagle-import") (part "R-US_10K"))
    )
    (comp (ref "R2")
      (value "226k, 1%")
      (footprint "eagle-import:VISHAY-R-0603")
      (fields (field (name "MF") "Vishay") (field (name "MPN") "CRCW0603226KFKEA"))
      (libsource (lib "eagle-import") (part "R-US_226K"))
    )
    (comp (ref "R3")
      (value "49.9k, 1%")
      (footprint "eagle-import:VISHAY-R-0603")
      (fields (field (name "MF") "Vishay") (field (name "MPN") "CRCW060349K9FKEA"))
      (libsource (lib "eagle-import") (part "R-US_49K9"))
    )
    (comp (ref "R7")
      (value "10k")
      (footprint "eagle-import:VISHAY-R-0603")
      (fields (field (name "MF") "Vishay") (field (name "MPN") "CRCW060310K0FKEA"))
      (libsource (lib "eagle-import") (part "R-US_10K"))
    )
    (comp (ref "R8")
      (value "10k")
      (footprint "eagle-import:VISHAY-R-0603")
      (fields (field (name "MF") "Vishay") (field (name "MPN") "CRCW060310K0FKEA"))
      (libsource (lib "eagle-import") (part "R-US_10K"))
    )
    (comp (ref "C9")
      (value "22u")
      (footprint "eagle-import:PANASONIC_B")
      (fields (field (name "MF") "Panasonic") (field (name "MPN") "EEE-FK1A220AR"))
      (libsource (lib "eagle-import") (part "CPOL_USB22U"))
    )
    (comp (ref "C10")
      (value "0.1u")
      (footprint "eagle-import:0603-CAP")
      (fields (field (name "MF") "Vishay") (field (name "MPN") "VJ0603Y104JXJPW1BC"))
      (libsource (lib "eagle-import") (part "C-US_0.1U"))
    )
    (comp (ref "C11")
      (value "0.1u")
      (footprint "eagle-import:0603-CAP")
      (fields (field (name "MF") "Vishay") (field (name "MPN") "VJ0603Y104JXJPW1BC"))
      (libsource (lib "eagle-import") (part "C-US_0.1U"))
    )
    (comp (ref "F1")
      (value "BLM18PG121SZ1D")
      (footprint "eagle-import:0603-BEAD")
      (fields (field (name "MF") "muRata"))
      (libsource (lib "eagle-import") (part "BLM18PG"))
    )
    (comp (ref "IC5")
      (value "FT232RL")
      (footprint "eagle-import:SSOP28")
      (fields (field (name "MF") "FTDI"))
      (libsource (lib "eagle-import") (part "FT232RL"))
    )
    (comp (ref "J2")
      (value "MICRO-USB-B")
      (footprint "eagle-import:SD-47346-001")
      (fields (field (name "MF") "Molex") (field (name "MPN") "47346-1001"))
      (libsource (lib "eagle-import") (part "MICRO-USB-B-REC-47346-001"))
    )
    (comp (ref "R9")
      (value "330")
      (footprint "eagle-import:VISHAY-R-0603")
      (fields (field (name "MF") "Vishay") (field (name "MPN") "CRCW0603330RFKEA"))
      (libsource (lib "eagle-import") (part "R-US_330"))
    )
    (comp (ref "R10")
      (value "330")
      (footprint "eagle-import:VISHAY-R-0603")
      (fields (field (name "MF") "Vishay") (field (name "MPN") "CRCW0603330RFKEA"))
      (libsource (lib "eagle-import") (part "R-US_330"))
    )
    (comp (ref "R32")
      (value "DNI")
      (footprint "eagle-import:VISHAY-R-0603")
      (fields (field (name "MF") "Vishay") (field (name "MPN") "CRCW060310K0FKEA"))
      (libsource (lib "eagle-import") (part "R-US_10K"))
    )
    (comp (ref "SW1")
      (value "TE-2-1437565-8")
      (footprint "eagle-import:TE-2-1437565-8")
      (fields (field (name "MF") "TE Connectivity") (field (name "MPN") "2-1437565-8"))
      (libsource (lib "eagle-import") (part "PUSH_BUTTON"))
    )
    (comp (ref "SW2")
      (value "TE-2-1437565-8")
      (footprint "eagle-import:TE-2-1437565-8")
      (fields (field (name "MF") "TE Connectivity") (field (name "MPN") "2-1437565-8"))
      (libsource (lib "eagle-import") (part "PUSH_BUTTON"))
    )
    (comp (ref "UART_RX")
      (value "RED")
      (footprint "eagle-import:HARVATEK_0603")
      (fields (field (name "MF") "Inolux / Harvatek") (field (name "MPN") "HT-191URO-5502"))
      (libsource (lib "eagle-import") (part "HT--191URO-5502-RED"))
    )
    (comp (ref "UART_TX")
      (value "GREEN")
      (footprint "eagle-import:HARVATEK_0603")
      (fields (field (name "MF") "Inolux / Harvatek") (field (name "MPN") "HT-193UYG-5592"))
      (libsource (lib "eagle-import") (part "HT--193UYG-5592-GREEN"))
    )
    (comp (ref "IC9")
      (value "12MHz")
      (footprint "eagle-import:ACHL-DIP")
      (fields (field (name "MF") "ABRACON") (field (name "MPN") "ACHL-12.000MHZ-EK"))
      (libsource (lib "eagle-import") (part "ACHL-DIPACHL-12.000MHZ-EK"))
    )
    (comp (ref "IC10")
      (value "SRAM")
      (footprint "eagle-import:TSSOP-ST-8")
      (fields (field (name "MF") "Microchip Technology") (field (name "MPN") "23LC1024-I/ST"))
      (libsource (lib "eagle-import") (part "23LC1024"))
    )
    (comp (ref "C12")
      (value "1p")
      (footprint "eagle-import:0603-CAP")
      (fields (field (name "MF") "Vishay") (field (name "MPN") "VJ0603A1R0BXACW1BC"))
      (libsource (lib "eagle-import") (part "C-US_1P"))
    )
    (comp (ref "C13")
      (value "1p")
      (footprint "eagle-import:0603-CAP")
      (fields (field (name "MF") "Vishay") (field (name "MPN") "VJ0603A1R0BXACW1BC"))
      (libsource (lib "eagle-import") (part "C-US_1P"))
    )
    (comp (ref "C14")
      (value "1p")
      (footprint "eagle-import:0603-CAP")
      (fields (field (name "MF") "Vishay") (field (name "MPN") "VJ0603A1R0BXACW1BC"))
      (libsource (lib "eagle-import") (part "C-US_1P"))
    )
    (comp (ref "C15")
      (value "1p")
      (footprint "eagle-import:0603-CAP")
      (fields (field (name "MF") "Vishay") (field (name "MPN") "VJ0603A1R0BXACW1BC"))
      (libsource (lib "eagle-import") (part "C-US_1P"))
    )
    (comp (ref "C16")
      (value "1p")
      (footprint "eagle-import:0603-CAP")
      (fields (field (name "MF") "Vishay") (field (name "MPN") "VJ0603A1R0BXACW1BC"))
      (libsource (lib "eagle-import") (part "C-US_1P"))
    )
    (comp (ref "C17")
      (value "1p")
      (footprint "eagle-import:0603-CAP")
      (fields (field (name "MF") "Vishay") (field (name "MPN") "VJ0603A1R0BXACW1BC"))
      (libsource (lib "eagle-import") (part "C-US_1P"))
    )
    (comp (ref "F3")
      (value "BLM18PG121SZ1D")
      (footprint "eagle-import:0603-BEAD")
      (fields (field (name "MF") "muRata"))
      (libsource (lib "eagle-import") (part "BLM18PG"))
    )
    (comp (ref "IC7")
      (value "MCP6242T-E/SN")
      (footprint "eagle-import:SOIC-SN-8")
      (fields (field (name "MF") "Microchip Technology"))
      (libsource (lib "eagle-import") (part "MCP6242T-E/SN"))
    )
    (comp (ref "IC8")
      (value "MCP6244T-E/ST")
      (footprint "eagle-import:TSSOP-ST-14")
      (fields (field (name "MF") "Microchip Technology"))
      (libsource (lib "eagle-import") (part "MCP6244T-E/ST"))
    )
    (comp (ref "PT1")
      (value "200k")
      (footprint "eagle-import:PT10LV10")
      (fields (field (name "MF") "Piher") (field (name "MPN") "PT10LV10-204A2020"))
      (libsource (lib "eagle-import") (part "PT10LV10"))
    )
    (comp (ref "R11")
      (value "100k")
      (footprint "eagle-import:VISHAY-R-0603")
      (fields (field (name "MF") "Vishay") (field (name "MPN") "CRCW0603100KFKEA"))
      (libsource (lib "eagle-import") (part "R-US_100K"))
    )
    (comp (ref "R12")
      (value "100k")
      (footprint "eagle-import:VISHAY-R-0603")
      (fields (field (name "MF") "Vishay") (field (name "MPN") "CRCW0603100KFKEA"))
      (libsource (lib "eagle-import") (part "R-US_100K"))
    )
    (comp (ref "R13")
      (value "200k")
      (footprint "eagle-import:VISHAY-R-0603")
      (fields (field (name "MF") "Vishay") (field (name "MPN") "CRCW0603200KFKEA"))
      (libsource (lib "eagle-import") (part "R-US_200K"))
    )
    (comp (ref "R14")
      (value "100k")
      (footprint "eagle-import:VISHAY-R-0603")
      (fields (field (name "MF") "Vishay") (field (name "MPN") "CRCW0603100KFKEA"))
      (libsource (lib "eagle-import") (part "R-US_100K"))
    )
    (comp (ref "R15")
      (value "200k")
      (footprint "eagle-import:VISHAY-R-0603")
      (fields (field (name "MF") "Vishay") (field (name "MPN") "CRCW0603200KFKEA"))
      (libsource (lib "eagle-import") (part "R-US_200K"))
    )
    (comp (ref "R16")
      (value "100k")
      (footprint "eagle-import:VISHAY-R-0603")
      (fields (field (name "MF") "Vishay") (field (name "MPN") "CRCW0603100KFKEA"))
      (libsource (lib "eagle-import") (part "R-US_100K"))
    )
    (comp (ref "R17")
      (value "200k")
      (footprint "eagle-import:VISHAY-R-0603")
      (fields (field (name "MF") "Vishay") (field (name "MPN") "CRCW0603200KFKEA"))
      (libsource (lib "eagle-import") (part "R-US_200K"))
    )
    (comp (ref "R18")
      (value "100k")
      (footprint "eagle-import:VISHAY-R-0603")
      (fields (field (name "MF") "Vishay") (field (name "MPN") "CRCW0603100KFKEA"))
      (libsource (lib "eagle-import") (part "R-US_100K"))
    )
    (comp (ref "R19")
      (value "200k")
      (footprint "eagle-import:VISHAY-R-0603")
      (fields (field (name "MF") "Vishay") (field (name "MPN") "CRCW0603200KFKEA"))
      (libsource (lib "eagle-import") (part "R-US_200K"))
    )
    (comp (ref "R20")
      (value "100k")
      (footprint "eagle-import:VISHAY-R-0603")
      (fields (field (name "MF") "Vishay") (field (name "MPN") "CRCW0603100KFKEA"))
      (libsource (lib "eagle-import") (part "R-US_100K"))
    )
    (comp (ref "R21")
      (value "200k")
      (footprint "eagle-import:VISHAY-R-0603")
      (fields (field (name "MF") "Vishay") (field (name "MPN") "CRCW0603200KFKEA"))
      (libsource (lib "eagle-import") (part "R-US_200K"))
    )
    (comp (ref "J7")
      (value "ALTERA_JTAG")
      (footprint "eagle-import:2X05")
      (fields (field (name "MF") "Harwin") (field (name "MPN") "M20-9760546 "))
      (libsource (lib "eagle-import") (part "ALTERA_JTAG"))
    )
    (comp (ref "JP2")
      (value "DNI")
      (footprint "eagle-import:1X02")
      (fields (field (name "MF") "Harwin") (field (name "MPN") "M20-9990246"))
      (libsource (lib "eagle-import") (part "PINHD-1X2"))
    )
    (comp (ref "R33")
      (value "10k")
      (footprint "eagle-import:VISHAY-R-0603")
      (fields (field (name "MF") "Vishay") (field (name "MPN") "CRCW060310K0FKEA"))
      (libsource (lib "eagle-import") (part "R-US_10K"))
    )
    (comp (ref "R34")
      (value "10k")
      (footprint "eagle-import:VISHAY-R-0603")
      (fields (field (name "MF") "Vishay") (field (name "MPN") "CRCW060310K0FKEA"))
      (libsource (lib "eagle-import") (part "R-US_10K"))
    )
    (comp (ref "R35")
      (value "10k")
      (footprint "eagle-import:VISHAY-R-0603")
      (fields (field (name "MF") "Vishay") (field (name "MPN") "CRCW060310K0FKEA"))
      (libsource (lib "eagle-import") (part "R-US_10K"))
    )
    (comp (ref "R39")
      (value "1k")
      (footprint "eagle-import:VISHAY-R-0603")
      (fields (field (name "MF") "Vishay") (field (name "MPN") "CRCW06031K00FKEA"))
      (libsource (lib "eagle-import") (part "R-US_1K"))
    )
    (comp (ref "C3")
      (value "0.1u")
      (footprint "eagle-import:0603-CAP")
      (fields (field (name "MF") "Vishay") (field (name "MPN") "VJ0603Y104JXJPW1BC"))
      (libsource (lib "eagle-import") (part "C-US_0.1U"))
    )
    (comp (ref "C6")
      (value "1u")
      (footprint "eagle-import:VISHAY-R-0603")
      (fields (field (name "MF") "Vishay") (field (name "MPN") "VJ0603V105MXQPW1BC"))
      (libsource (lib "eagle-import") (part "C-US_1U"))
    )
    (comp (ref "C7")
      (value "1u")
      (footprint "eagle-import:VISHAY-R-0603")
      (fields (field (name "MF") "Vishay") (field (name "MPN") "VJ0603V105MXQPW1BC"))
      (libsource (lib "eagle-import") (part "C-US_1U"))
    )
    (comp (ref "C25")
      (value "1u")
      (footprint "eagle-import:VISHAY-R-0603")
      (fields (field (name "MF") "Vishay") (field (name "MPN") "VJ0603V105MXQPW1BC"))
      (libsource (lib "eagle-import") (part "C-US_1U"))
    )
    (comp (ref "IC3")
      (value "SI3000")
      (footprint "eagle-import:SOIC-16")
      (fields (field (name "MF") "Silicon Labs") (field (name "MPN") "Si3000-C-FS"))
      (libsource (lib "eagle-import") (part "SI3000-C-FS"))
    )
    (comp (ref "J4")
      (value "PHONE_JACK_NOT_SWITCHED")
      (footprint "eagle-import:PHONE_JACK_NOT_SWITCHED")
      (fields (field (name "MF") "Switchcraft") (field (name "MPN") "35RASMT2BHNTRX"))
      (libsource (lib "eagle-import") (part "PHONE_JACK_NOT_SWITCHED"))
    )
    (comp (ref "MIC1")
      (value "MIC-CUICMC-5044PF-A")
      (footprint "eagle-import:CMC-5044PF-A")
      (fields (field (name "MF") "CUI") (field (name "MPN") "CMC-5044PF-A"))
      (libsource (lib "eagle-import") (part "MIC-CUICMC-5044PF-A"))
    )
    (comp (ref "R5")
      (value "2.2k")
      (footprint "eagle-import:VISHAY-R-0603")
      (fields (field (name "MF") "Vishay") (field (name "MPN") "CRCW06032K20FKEA"))
      (libsource (lib "eagle-import") (part "R-US_2.2K"))
    )
    (comp (ref "R6")
      (value "30")
      (footprint "eagle-import:VISHAY-R-0603")
      (fields (field (name "MF") "Vishay") (field (name "MPN") "CRCW060330R0FKEA"))
      (libsource (lib "eagle-import") (part "R-US_30"))
    )
    (comp (ref "R29")
      (value "30")
      (footprint "eagle-import:VISHAY-R-0603")
      (fields (field (name "MF") "Vishay") (field (name "MPN") "CRCW060330R0FKEA"))
      (libsource (lib "eagle-import") (part "R-US_30"))
    )
    (comp (ref "C18")
      (value "0.1u")
      (footprint "eagle-import:0603-CAP")
      (fields (field (name "MF") "Vishay") (field (name "MPN") "VJ0603Y104JXJPW1BC"))
      (libsource (lib "eagle-import") (part "C-US_0.1U"))
    )
    (comp (ref "J8")
      (value "DUINO_IO_HEADER_10")
      (footprint "eagle-import:DUINO_IO_HEADER_10")
      (fields (field (name "MF") "Sullins Connector Solutions") (field (name "MPN") "PPTC101LFBN-RC"))
      (libsource (lib "eagle-import") (part "DUINO_IO_HEADER_10"))
    )
    (comp (ref "J9")
      (value "DUINO_HEADER_8")
      (footprint "eagle-import:DUINO_IO_HEADER_8")
      (fields (field (name "MF") "Sullins Connector Solutions") (field (name "MPN") "PPPC081LFBN-RC"))
      (libsource (lib "eagle-import") (part "DUINO_IO_HEADER_8"))
    )
    (comp (ref "J10")
      (value "DUINO_HEADER_8")
      (footprint "eagle-import:DUINO_PWR_HEADER_8")
      (fields (field (name "MF") "Sullins Connector Solutions") (field (name "MPN") "PPPC081LFBN-RC"))
      (libsource (lib "eagle-import") (part "DUINO_PWR_HEADER_8"))
    )
    (comp (ref "J11")
      (value "DUINO_ANALOG_HEADER_6")
      (footprint "eagle-import:DUINO_ANALOG_HEADER_6")
      (fields (field (name "MF") "Sullins Connector Solutions") (field (name "MPN") "PPTC061LFBN-RC"))
      (libsource (lib "eagle-import") (part "DUINO_ANALOG_HEADER_6"))
    )
    (comp (ref "JP1")
      (value "IOREF JUMPER")
      (footprint "eagle-import:1X03")
      (fields (field (name "MF") "Harwin") (field (name "MPN") "M20-9990346"))
      (libsource (lib "eagle-import") (part "PINHD-1X3"))
    )
    (comp (ref "LED_IOREF")
      (value "BLUE")
      (footprint "eagle-import:HARVATEK_0603")
      (fields (field (name "MF") "Inolux / Harvatek") (field (name "MPN") "HT-193NB-5589"))
      (libsource (lib "eagle-import") (part "HT--193NB-5589-BLUE"))
    )
    (comp (ref "R22")
      (value "330")
      (footprint "eagle-import:VISHAY-R-0603")
      (fields (field (name "MF") "Vishay") (field (name "MPN") "CRCW0603330RFKEA"))
      (libsource (lib "eagle-import") (part "R-US_330"))
    )
    (comp (ref "U$8")
      (value "DUINO")
      (footprint "eagle-import:DUINO")
      (libsource (lib "eagle-import") (part "DUINO"))
    )
    (comp (ref "IC11")
      (value "MICRO_SD_SOCKET")
      (footprint "eagle-import:ALPS-SCHD3A0100")
      (fields (field (name "MF") "ALPS") (field (name "MPN") "SCHD3A0100"))
      (libsource (lib "eagle-import") (part "ALPS-SCHD3A0100"))
    )
    (comp (ref "C33")
      (value "0.1u")
      (footprint "eagle-import:0603-CAP")
      (fields (field (name "MF") "Vishay") (field (name "MPN") "VJ0603Y104JXJPW1BC"))
      (libsource (lib "eagle-import") (part "C-US_0.1U"))
    )
    (comp (ref "F5")
      (value "BLM18PG121SZ1D")
      (footprint "eagle-import:0603-BEAD")
      (fields (field (name "MF") "muRata"))
      (libsource (lib "eagle-import") (part "BLM18PG"))
    )
    (comp (ref "F6")
      (value "BLM18PG121SZ1D")
      (footprint "eagle-import:0603-BEAD")
      (fields (field (name "MF") "muRata"))
      (libsource (lib "eagle-import") (part "BLM18PG"))
    )
    (comp (ref "F7")
      (value "BLM18PG121SZ1D")
      (footprint "eagle-import:0603-BEAD")
      (fields (field (name "MF") "muRata"))
      (libsource (lib "eagle-import") (part "BLM18PG"))
    )
    (comp (ref "R4")
      (value "0")
      (footprint "eagle-import:VISHAY-R-0603")
      (fields (field (name "MF") "Vishay") (field (name "MPN") "CRCW06030000Z0EAHP"))
      (libsource (lib "eagle-import") (part "R-US_0"))
    )
    (comp (ref "R30")
      (value "0")
      (footprint "eagle-import:VISHAY-R-0603")
      (fields (field (name "MF") "Vishay") (field (name "MPN") "CRCW06030000Z0EAHP"))
      (libsource (lib "eagle-import") (part "R-US_0"))
    )
    (comp (ref "U$2")
      (value "PULSERAIN_LOGO_BIGGER")
      (footprint "eagle-import:PULSERAIN_LOGO_BIGGER")
      (libsource (lib "eagle-import") (part "PULSERAIN_LOGO_BIGGER"))
    )
    (comp (ref "JP6")
      (value "BOOT IMAGE SELECT")
      (footprint "eagle-import:1X02")
      (fields (field (name "MF") "Harwin") (field (name "MPN") "M20-9990246"))
      (libsource (lib "eagle-import") (part "PINHD-1X2"))
    )
    (comp (ref "LED1")
      (value "GREEN")
      (footprint "eagle-import:HARVATEK_0603")
      (fields (field (name "MF") "Inolux / Harvatek") (field (name "MPN") "HT-193UYG-5592"))
      (libsource (lib "eagle-import") (part "HT--193UYG-5592-GREEN"))
    )
    (comp (ref "LED2")
      (value "RED")
      (footprint "eagle-import:HARVATEK_0603")
      (fields (field (name "MF") "Inolux / Harvatek") (field (name "MPN") "HT-191URO-5502"))
      (libsource (lib "eagle-import") (part "HT--191URO-5502-RED"))
    )
    (comp (ref "LED3")
      (value "BLUE")
      (footprint "eagle-import:HARVATEK_0603")
      (fields (field (name "MF") "Inolux / Harvatek") (field (name "MPN") "HT-193NB-5589"))
      (libsource (lib "eagle-import") (part "HT--193NB-5589-BLUE"))
    )
    (comp (ref "R36")
      (value "10k")
      (footprint "eagle-import:VISHAY-R-0603")
      (fields (field (name "MF") "Vishay") (field (name "MPN") "CRCW060310K0FKEA"))
      (libsource (lib "eagle-import") (part "R-US_10K"))
    )
    (comp (ref "R37")
      (value "10k")
      (footprint "eagle-import:VISHAY-R-0603")
      (fields (field (name "MF") "Vishay") (field (name "MPN") "CRCW060310K0FKEA"))
      (libsource (lib "eagle-import") (part "R-US_10K"))
    )
    (comp (ref "R38")
      (value "10k")
      (footprint "eagle-import:VISHAY-R-0603")
      (fields (field (name "MF") "Vishay") (field (name "MPN") "CRCW060310K0FKEA"))
      (libsource (lib "eagle-import") (part "R-US_10K"))
    )
    (comp (ref "R40")
      (value "10k")
      (footprint "eagle-import:VISHAY-R-0603")
      (fields (field (name "MF") "Vishay") (field (name "MPN") "CRCW060310K0FKEA"))
      (libsource (lib "eagle-import") (part "R-US_10K"))
    )
    (comp (ref "R41")
      (value "10k")
      (footprint "eagle-import:VISHAY-R-0603")
      (fields (field (name "MF") "Vishay") (field (name "MPN") "CRCW060310K0FKEA"))
      (libsource (lib "eagle-import") (part "R-US_10K"))
    )
    (comp (ref "R42")
      (value "330")
      (footprint "eagle-import:VISHAY-R-0603")
      (fields (field (name "MF") "Vishay") (field (name "MPN") "CRCW0603330RFKEA"))
      (libsource (lib "eagle-import") (part "R-US_330"))
    )
    (comp (ref "R43")
      (value "330")
      (footprint "eagle-import:VISHAY-R-0603")
      (fields (field (name "MF") "Vishay") (field (name "MPN") "CRCW0603330RFKEA"))
      (libsource (lib "eagle-import") (part "R-US_330"))
    )
    (comp (ref "R47")
      (value "330")
      (footprint "eagle-import:VISHAY-R-0603")
      (fields (field (name "MF") "Vishay") (field (name "MPN") "CRCW0603330RFKEA"))
      (libsource (lib "eagle-import") (part "R-US_330"))
    )
    (comp (ref "C19")
      (value "1000p")
      (footprint "eagle-import:VISHAY-R-0603")
      (fields (field (name "MF") "Vishay") (field (name "MPN") "VJ0603Y102JXJPW1BC"))
      (libsource (lib "eagle-import") (part "C-US_1000P"))
    )
    (comp (ref "C20")
      (value "1000p")
      (footprint "eagle-import:VISHAY-R-0603")
      (fields (field (name "MF") "Vishay") (field (name "MPN") "VJ0603Y102JXJPW1BC"))
      (libsource (lib "eagle-import") (part "C-US_1000P"))
    )
    (comp (ref "C21")
      (value "1000p")
      (footprint "eagle-import:VISHAY-R-0603")
      (fields (field (name "MF") "Vishay") (field (name "MPN") "VJ0603Y102JXJPW1BC"))
      (libsource (lib "eagle-import") (part "C-US_1000P"))
    )
    (comp (ref "C22")
      (value "1000p")
      (footprint "eagle-import:VISHAY-R-0603")
      (fields (field (name "MF") "Vishay") (field (name "MPN") "VJ0603Y102JXJPW1BC"))
      (libsource (lib "eagle-import") (part "C-US_1000P"))
    )
    (comp (ref "C23")
      (value "1000p")
      (footprint "eagle-import:VISHAY-R-0603")
      (fields (field (name "MF") "Vishay") (field (name "MPN") "VJ0603Y102JXJPW1BC"))
      (libsource (lib "eagle-import") (part "C-US_1000P"))
    )
    (comp (ref "C24")
      (value "1000p")
      (footprint "eagle-import:VISHAY-R-0603")
      (fields (field (name "MF") "Vishay") (field (name "MPN") "VJ0603Y102JXJPW1BC"))
      (libsource (lib "eagle-import") (part "C-US_1000P"))
    )
    (comp (ref "F4")
      (value "BLM18PG121SZ1D")
      (footprint "eagle-import:0603-BEAD")
      (fields (field (name "MF") "muRata"))
      (libsource (lib "eagle-import") (part "BLM18PG"))
    )
    (comp (ref "R23")
      (value "100")
      (footprint "eagle-import:VISHAY-R-0603")
      (fields (field (name "MF") "Vishay") (field (name "MPN") "CRCW0603100RFKEA"))
      (libsource (lib "eagle-import") (part "R-US_100"))
    )
    (comp (ref "R24")
      (value "100")
      (footprint "eagle-import:VISHAY-R-0603")
      (fields (field (name "MF") "Vishay") (field (name "MPN") "CRCW0603100RFKEA"))
      (libsource (lib "eagle-import") (part "R-US_100"))
    )
    (comp (ref "R25")
      (value "100")
      (footprint "eagle-import:VISHAY-R-0603")
      (fields (field (name "MF") "Vishay") (field (name "MPN") "CRCW0603100RFKEA"))
      (libsource (lib "eagle-import") (part "R-US_100"))
    )
    (comp (ref "R26")
      (value "100")
      (footprint "eagle-import:VISHAY-R-0603")
      (fields (field (name "MF") "Vishay") (field (name "MPN") "CRCW0603100RFKEA"))
      (libsource (lib "eagle-import") (part "R-US_100"))
    )
    (comp (ref "R27")
      (value "100")
      (footprint "eagle-import:VISHAY-R-0603")
      (fields (field (name "MF") "Vishay") (field (name "MPN") "CRCW0603100RFKEA"))
      (libsource (lib "eagle-import") (part "R-US_100"))
    )
    (comp (ref "R28")
      (value "100")
      (footprint "eagle-import:VISHAY-R-0603")
      (fields (field (name "MF") "Vishay") (field (name "MPN") "CRCW0603100RFKEA"))
      (libsource (lib "eagle-import") (part "R-US_100"))
    )
  )
  (nets
    (net (code "1") (name "+3V3") (class "Default")
      (node (ref "C4") (pin "1") (pinfunction "1_1") (pintype "passive"))
      (node (ref "C5") (pin "+") (pinfunction "+_+") (pintype "passive"))
      (node (ref "F4") (pin "1") (pinfunction "1_1") (pintype "passive"))
      (node (ref "F5") (pin "1") (pinfunction "1_1") (pintype "passive"))
      (node (ref "F6") (pin "1") (pinfunction "1_1") (pintype "passive"))
      (node (ref "IC10") (pin "8") (pinfunction "VCC_8") (pintype "input"))
      (node (ref "IC11") (pin "4") (pinfunction "VDD_4") (pintype "input"))
      (node (ref "IC12") (pin "10") (pinfunction "10_10") (pintype "bidirectional"))
      (node (ref "IC12") (pin "2") (pinfunction "2_2") (pintype "input"))
      (node (ref "IC13") (pin "10") (pinfunction "10_10") (pintype "bidirectional"))
      (node (ref "IC13") (pin "2") (pinfunction "2_2") (pintype "input"))
      (node (ref "IC3") (pin "12") (pinfunction "VD_12") (pintype "input"))
      (node (ref "IC4") (pin "3") (pinfunction "-IN_3") (pintype "input"))
      (node (ref "IC6") (pin "1") (pinfunction "VCC_ONE10_1") (pintype "input"))
      (node (ref "IC6") (pin "103") (pinfunction "VCCIO6_2_103") (pintype "input"))
      (node (ref "IC6") (pin "108") (pinfunction "VCC_ONE9_108") (pintype "input"))
      (node (ref "IC6") (pin "109") (pinfunction "VCC_ONE8_109") (pintype "input"))
      (node (ref "IC6") (pin "115") (pinfunction "VCC_ONE7_115") (pintype "input"))
      (node (ref "IC6") (pin "117") (pinfunction "VCCIO7_117") (pintype "input"))
      (node (ref "IC6") (pin "128") (pinfunction "VCCIO8_1_128") (pintype "input"))
      (node (ref "IC6") (pin "139") (pinfunction "VCCIO8_2_139") (pintype "input"))
      (node (ref "IC6") (pin "144") (pinfunction "VCC_ONE6_144") (pintype "input"))
      (node (ref "IC6") (pin "23") (pinfunction "VCCIO1B_23") (pintype "input"))
      (node (ref "IC6") (pin "31") (pinfunction "VCCIO2_31") (pintype "input"))
      (node (ref "IC6") (pin "36") (pinfunction "VCC_ONE5_36") (pintype "input"))
      (node (ref "IC6") (pin "37") (pinfunction "VCC_ONE4_37") (pintype "input"))
      (node (ref "IC6") (pin "40") (pinfunction "VCCIO3_1_40") (pintype "input"))
      (node (ref "IC6") (pin "49") (pinfunction "VCCIO3_2_49") (pintype "input"))
      (node (ref "IC6") (pin "51") (pinfunction "VCC_ONE3_51") (pintype "input"))
      (node (ref "IC6") (pin "67") (pinfunction "VCCIO4_67") (pintype "input"))
      (node (ref "IC6") (pin "72") (pinfunction "VCC_ONE1_72") (pintype "input"))
      (node (ref "IC6") (pin "73") (pinfunction "VCC_ONE2_73") (pintype "input"))
      (node (ref "IC6") (pin "82") (pinfunction "VCCIO5_82") (pintype "input"))
      (node (ref "IC6") (pin "94") (pinfunction "VCCIO6_1_94") (pintype "input"))
      (node (ref "IC9") (pin "1") (pinfunction "EN_1") (pintype "input"))
      (node (ref "IC9") (pin "8") (pinfunction "VCC_8") (pintype "input"))
      (node (ref "J10") (pin "3.3V") (pinfunction "3.3V_3.3V") (pintype "bidirectional"))
      (node (ref "J7") (pin "4") (pinfunction "4_4") (pintype "passive"))
      (node (ref "JP1") (pin "3") (pinfunction "3_3") (pintype "passive"))
      (node (ref "L1") (pin "2") (pinfunction "2_2") (pintype "passive"))
      (node (ref "R2") (pin "P$2") (pinfunction "2_P$2") (pintype "passive"))
      (node (ref "R32") (pin "P$1") (pinfunction "1_P$1") (pintype "passive"))
      (node (ref "R33") (pin "P$1") (pinfunction "1_P$1") (pintype "passive"))
      (node (ref "R34") (pin "P$2") (pinfunction "2_P$2") (pintype "passive"))
      (node (ref "R35") (pin "P$2") (pinfunction "2_P$2") (pintype "passive"))
      (node (ref "R36") (pin "P$1") (pinfunction "1_P$1") (pintype "passive"))
      (node (ref "R37") (pin "P$2") (pinfunction "2_P$2") (pintype "passive"))
      (node (ref "R38") (pin "P$2") (pinfunction "2_P$2") (pintype "passive"))
      (node (ref "R40") (pin "P$1") (pinfunction "1_P$1") (pintype "passive"))
      (node (ref "R41") (pin "P$1") (pinfunction "1_P$1") (pintype "passive"))
      (node (ref "R42") (pin "P$2") (pinfunction "2_P$2") (pintype "passive"))
      (node (ref "R43") (pin "P$2") (pinfunction "2_P$2") (pintype "passive"))
      (node (ref "R47") (pin "P$2") (pinfunction "2_P$2") (pintype "passive"))
    )
    (net (code "2") (name "+5V") (class "Default")
      (node (ref "C2") (pin "+") (pinfunction "+_+") (pintype "passive"))
      (node (ref "C26") (pin "+") (pinfunction "+_+") (pintype "passive"))
      (node (ref "F3") (pin "2") (pinfunction "2_2") (pintype "passive"))
      (node (ref "IC1") (pin "2") (pinfunction "2_2") (pintype "input"))
      (node (ref "IC1") (pin "VOUT") (pinfunction "VOUT_VOUT") (pintype "input"))
      (node (ref "IC2") (pin "4") (pinfunction "VIN_4") (pintype "input"))
      (node (ref "IC4") (pin "5") (pinfunction "V+_5") (pintype "input"))
      (node (ref "J10") (pin "5V") (pinfunction "5V_5V") (pintype "bidirectional"))
      (node (ref "JP1") (pin "1") (pinfunction "1_1") (pintype "passive"))
      (node (ref "PMOS1") (pin "4") (pinfunction "S_4") (pintype "passive"))
      (node (ref "R1") (pin "P$1") (pinfunction "1_P$1") (pintype "passive"))
    )
    (net (code "3") (name "3V3_FLT") (class "Default")
      (node (ref "C25") (pin "P$1") (pinfunction "1_P$1") (pintype "passive"))
      (node (ref "F6") (pin "2") (pinfunction "2_2") (pintype "passive"))
      (node (ref "IC3") (pin "13") (pinfunction "VA_13") (pintype "input"))
      (node (ref "IC6") (pin "107") (pinfunction "VCCA3_107") (pintype "input"))
      (node (ref "IC6") (pin "34") (pinfunction "VCCA2_34") (pintype "input"))
      (node (ref "IC6") (pin "35") (pinfunction "VCCA1_35") (pintype "input"))
      (node (ref "IC6") (pin "71") (pinfunction "VCCA5_71") (pintype "input"))
    )
    (net (code "4") (name "3V3_PIN0_RX") (class "Default")
      (node (ref "IC12") (pin "1") (pinfunction "1_1") (pintype "bidirectional"))
      (node (ref "IC6") (pin "50") (pinfunction "DIFFIO_TX_RX_B9N/DIFFOUT_B9N_50") (pintype "bidirectional"))
    )
    (net (code "5") (name "3V3_PIN1_TX") (class "Default")
      (node (ref "IC12") (pin "3") (pinfunction "3_3") (pintype "bidirectional"))
      (node (ref "IC6") (pin "52") (pinfunction "DIFFIO_TX_RX_B9P/DIFFOUT_B9P_52") (pintype "bidirectional"))
    )
    (net (code "6") (name "3V3_PIN2") (class "Default")
      (node (ref "IC12") (pin "4") (pinfunction "4_4") (pintype "bidirectional"))
      (node (ref "IC6") (pin "54") (pinfunction "IO54_54") (pintype "bidirectional"))
    )
    (net (code "7") (name "3V3_PIN3~{}") (class "Default")
      (node (ref "IC12") (pin "5") (pinfunction "5_5") (pintype "bidirectional"))
      (node (ref "IC6") (pin "55") (pinfunction "DIFFIO_TX_RX_B12N/DIFFOUT_B12N_55") (pintype "bidirectional"))
    )
    (net (code "8") (name "3V3_PIN4") (class "Default")
      (node (ref "IC12") (pin "6") (pinfunction "6_6") (pintype "bidirectional"))
      (node (ref "IC6") (pin "56") (pinfunction "DIFFIO_TX_RX_B12P/DIFFOUT_B12P_56") (pintype "bidirectional"))
    )
    (net (code "9") (name "3V3_PIN5~{}") (class "Default")
      (node (ref "IC12") (pin "7") (pinfunction "7_7") (pintype "bidirectional"))
      (node (ref "IC6") (pin "57") (pinfunction "DIFFIO_TX_RX_B14N/DIFFOUT_B14N_57") (pintype "bidirectional"))
    )
    (net (code "10") (name "3V3_PIN6~{}") (class "Default")
      (node (ref "IC12") (pin "8") (pinfunction "8_8") (pintype "bidirectional"))
      (node (ref "IC6") (pin "58") (pinfunction "DIFFIO_TX_RX_B14P/DIFFOUT_B14P_58") (pintype "bidirectional"))
    )
    (net (code "11") (name "3V3_PIN7") (class "Default")
      (node (ref "IC12") (pin "9") (pinfunction "9_9") (pintype "bidirectional"))
      (node (ref "IC6") (pin "59") (pinfunction "DIFFIO_TX_RX_B16N/DIFFOUT_B16N_59") (pintype "bidirectional"))
    )
    (net (code "12") (name "3V3_PIN8") (class "Default")
      (node (ref "IC13") (pin "1") (pinfunction "1_1") (pintype "bidirectional"))
      (node (ref "IC6") (pin "92") (pinfunction "DIFFIO_RX_R18P/DIFFOUT_R18P_92") (pintype "bidirectional"))
    )
    (net (code "13") (name "3V3_PIN9~{}") (class "Default")
      (node (ref "IC13") (pin "3") (pinfunction "3_3") (pintype "bidirectional"))
      (node (ref "IC6") (pin "93") (pinfunction "DIFFIO_RX_R18N/DIFFOUT_R18N_93") (pintype "bidirectional"))
    )
    (net (code "14") (name "3V3_PIN10~{}") (class "Default")
      (node (ref "IC13") (pin "4") (pinfunction "4_4") (pintype "bidirectional"))
      (node (ref "IC6") (pin "96") (pinfunction "DPCLK3/DIFFIO_RX_R26P/DIFFOUT_R26P_96") (pintype "bidirectional"))
    )
    (net (code "15") (name "3V3_PIN11~{}") (class "Default")
      (node (ref "IC13") (pin "5") (pinfunction "5_5") (pintype "bidirectional"))
      (node (ref "IC6") (pin "98") (pinfunction "DPCLK2/DIFFIO_RX_R26N/DIFFOUT_R26N_98") (pintype "bidirectional"))
    )
    (net (code "16") (name "3V3_PIN12") (class "Default")
      (node (ref "IC13") (pin "6") (pinfunction "6_6") (pintype "bidirectional"))
      (node (ref "IC6") (pin "99") (pinfunction "DIFFIO_RX_R27P/DIFFOUT_R27P_99") (pintype "bidirectional"))
    )
    (net (code "17") (name "3V3_PIN13") (class "Default")
      (node (ref "IC13") (pin "7") (pinfunction "7_7") (pintype "bidirectional"))
      (node (ref "IC6") (pin "100") (pinfunction "DIFFIO_RX_R28P/DIFFOUT_R28P_100") (pintype "bidirectional"))
    )
    (net (code "18") (name "3V3_SCL") (class "Default")
      (node (ref "IC13") (pin "9") (pinfunction "9_9") (pintype "bidirectional"))
      (node (ref "IC6") (pin "102") (pinfunction "DIFFIO_RX_R28N/DIFFOUT_R28N_102") (pintype "bidirectional"))
    )
    (net (code "19") (name "3V3_SDA") (class "Default")
      (node (ref "IC13") (pin "8") (pinfunction "8_8") (pintype "bidirectional"))
      (node (ref "IC6") (pin "101") (pinfunction "DIFFIO_RX_R27N/DIFFOUT_R27N_101") (pintype "bidirectional"))
    )
    (net (code "20") (name "5V_FLT") (class "Default")
      (node (ref "F3") (pin "1") (pinfunction "1_1") (pintype "passive"))
      (node (ref "IC7") (pin "8") (pinfunction "VDD_8") (pintype "input"))
      (node (ref "IC8") (pin "4") (pinfunction "4_4") (pintype "input"))
    )
    (net (code "21") (name "A0") (class "Default")
      (node (ref "J11") (pin "A0") (pinfunction "A0_A0") (pintype "bidirectional"))
      (node (ref "R11") (pin "P$1") (pinfunction "1_P$1") (pintype "passive"))
    )
    (net (code "22") (name "A1") (class "Default")
      (node (ref "J11") (pin "A1") (pinfunction "A1_A1") (pintype "bidirectional"))
      (node (ref "R12") (pin "P$1") (pinfunction "1_P$1") (pintype "passive"))
    )
    (net (code "23") (name "A2") (class "Default")
      (node (ref "J11") (pin "A2") (pinfunction "A2_A2") (pintype "bidirectional"))
      (node (ref "R14") (pin "P$1") (pinfunction "1_P$1") (pintype "passive"))
    )
    (net (code "24") (name "A3") (class "Default")
      (node (ref "J11") (pin "A3") (pinfunction "A3_A3") (pintype "bidirectional"))
      (node (ref "R16") (pin "P$1") (pinfunction "1_P$1") (pintype "passive"))
    )
    (net (code "25") (name "A4") (class "Default")
      (node (ref "J11") (pin "A4") (pinfunction "A4_A4") (pintype "bidirectional"))
      (node (ref "R20") (pin "P$1") (pinfunction "1_P$1") (pintype "passive"))
    )
    (net (code "26") (name "A5") (class "Default")
      (node (ref "J11") (pin "A5") (pinfunction "A5_A5") (pintype "bidirectional"))
      (node (ref "R18") (pin "P$1") (pinfunction "1_P$1") (pintype "passive"))
    )
    (net (code "27") (name "ADC_IN0") (class "Default")
      (node (ref "IC7") (pin "1") (pinfunction "1_1") (pintype "output"))
      (node (ref "IC7") (pin "2") (pinfunction "2_2") (pintype "input"))
      (node (ref "R23") (pin "P$1") (pinfunction "1_P$1") (pintype "passive"))
    )
    (net (code "28") (name "ADC_IN1") (class "Default")
      (node (ref "IC7") (pin "6") (pinfunction "6_6") (pintype "input"))
      (node (ref "IC7") (pin "7") (pinfunction "7_7") (pintype "output"))
      (node (ref "R24") (pin "P$1") (pinfunction "1_P$1") (pintype "passive"))
    )
    (net (code "29") (name "ADC_IN2") (class "Default")
      (node (ref "IC8") (pin "1") (pinfunction "1_1") (pintype "output"))
      (node (ref "IC8") (pin "2") (pinfunction "2_2") (pintype "input"))
      (node (ref "R25") (pin "P$1") (pinfunction "1_P$1") (pintype "passive"))
    )
    (net (code "30") (name "ADC_IN3") (class "Default")
      (node (ref "IC8") (pin "6") (pinfunction "6_6") (pintype "input"))
      (node (ref "IC8") (pin "7") (pinfunction "7_7") (pintype "output"))
      (node (ref "R26") (pin "P$1") (pinfunction "1_P$1") (pintype "passive"))
    )
    (net (code "31") (name "ADC_IN4") (class "Default")
      (node (ref "IC8") (pin "13") (pinfunction "13_13") (pintype "input"))
      (node (ref "IC8") (pin "14") (pinfunction "14_14") (pintype "output"))
      (node (ref "R27") (pin "P$2") (pinfunction "2_P$2") (pintype "passive"))
    )
    (net (code "32") (name "ADC_IN5") (class "Default")
      (node (ref "IC8") (pin "8") (pinfunction "8_8") (pintype "output"))
      (node (ref "IC8") (pin "9") (pinfunction "9_9") (pintype "input"))
      (node (ref "R28") (pin "P$2") (pinfunction "2_P$2") (pintype "passive"))
    )
    (net (code "33") (name "AGND") (class "Default")
      (node (ref "C12") (pin "2") (pinfunction "2_2") (pintype "passive"))
      (node (ref "C13") (pin "2") (pinfunction "2_2") (pintype "passive"))
      (node (ref "C14") (pin "2") (pinfunction "2_2") (pintype "passive"))
      (node (ref "C15") (pin "2") (pinfunction "2_2") (pintype "passive"))
      (node (ref "C16") (pin "2") (pinfunction "2_2") (pintype "passive"))
      (node (ref "C17") (pin "2") (pinfunction "2_2") (pintype "passive"))
      (node (ref "C19") (pin "P$2") (pinfunction "2_P$2") (pintype "passive"))
      (node (ref "C20") (pin "P$2") (pinfunction "2_P$2") (pintype "passive"))
      (node (ref "C21") (pin "P$2") (pinfunction "2_P$2") (pintype "passive"))
      (node (ref "C22") (pin "P$2") (pinfunction "2_P$2") (pintype "passive"))
      (node (ref "C23") (pin "P$2") (pinfunction "2_P$2") (pintype "passive"))
      (node (ref "C24") (pin "P$2") (pinfunction "2_P$2") (pintype "passive"))
      (node (ref "C25") (pin "P$2") (pinfunction "2_P$2") (pintype "passive"))
      (node (ref "C33") (pin "2") (pinfunction "2_2") (pintype "passive"))
      (node (ref "F7") (pin "1") (pinfunction "1_1") (pintype "passive"))
      (node (ref "IC6") (pin "13") (pinfunction "DIFFIO_RX_L7N/DIFFOUT_L7N/ADC1IN7_13") (pintype "bidirectional"))
      (node (ref "IC6") (pin "14") (pinfunction "DIFFIO_RX_L7P/DIFFOUT_L7P/ADC1IN8_14") (pintype "bidirectional"))
      (node (ref "IC6") (pin "3") (pinfunction "ANAIN1_3") (pintype "input"))
      (node (ref "IC7") (pin "4") (pinfunction "VSS_4") (pintype "input"))
      (node (ref "IC8") (pin "11") (pinfunction "11_11") (pintype "input"))
      (node (ref "J4") (pin "5") (pinfunction "5_5") (pintype "passive"))
      (node (ref "MIC1") (pin "1") (pinfunction "2_1") (pintype "input"))
      (node (ref "PT1") (pin "1E") (pinfunction "1E_1E") (pintype "passive"))
      (node (ref "PT1") (pin "1S") (pinfunction "1S_1S") (pintype "passive"))
      (node (ref "R13") (pin "P$2") (pinfunction "2_P$2") (pintype "passive"))
      (node (ref "R15") (pin "P$1") (pinfunction "1_P$1") (pintype "passive"))
      (node (ref "R17") (pin "P$1") (pinfunction "1_P$1") (pintype "passive"))
      (node (ref "R19") (pin "P$2") (pinfunction "2_P$2") (pintype "passive"))
      (node (ref "R21") (pin "P$1") (pinfunction "1_P$1") (pintype "passive"))
      (node (ref "R30") (pin "P$2") (pinfunction "2_P$2") (pintype "passive"))
      (node (ref "R4") (pin "P$2") (pinfunction "2_P$2") (pintype "passive"))
    )
    (net (code "34") (name "AREF") (class "Default")
      (node (ref "C33") (pin "1") (pinfunction "1_1") (pintype "passive"))
      (node (ref "IC6") (pin "5") (pinfunction "ADC_REF_5") (pintype "input"))
      (node (ref "J8") (pin "AREF") (pinfunction "AREF_AREF") (pintype "bidirectional"))
    )
    (net (code "35") (name "CODEC_FSYNC_N") (class "Default")
      (node (ref "IC3") (pin "6") (pinfunction "FSYNC_N_6") (pintype "bidirectional"))
      (node (ref "IC6") (pin "43") (pinfunction "DIFFIO_TX_RX_B3P/DIFFOUT_B3P_43") (pintype "bidirectional"))
    )
    (net (code "36") (name "CODEC_MCLK") (class "Default")
      (node (ref "IC3") (pin "7") (pinfunction "MCLK_7") (pintype "input"))
      (node (ref "IC6") (pin "41") (pinfunction "DIFFIO_TX_RX_B3N/DIFFOUT_B3N_41") (pintype "bidirectional"))
    )
    (net (code "37") (name "CODEC_RESET_N") (class "Default")
      (node (ref "IC3") (pin "9") (pinfunction "RESET_N_9") (pintype "input"))
      (node (ref "IC6") (pin "39") (pinfunction "DIFFIO_TX_RX_B1P/DIFFOUT_B1P_39") (pintype "bidirectional"))
    )
    (net (code "38") (name "CODEC_SCLK") (class "Default")
      (node (ref "IC3") (pin "8") (pinfunction "SCLK_8") (pintype "bidirectional"))
      (node (ref "IC6") (pin "38") (pinfunction "DIFFIO_TX_RX_B1N/DIFFOUT_B1N_38") (pintype "bidirectional"))
    )
    (net (code "39") (name "CODEC_SDI") (class "Default")
      (node (ref "IC3") (pin "4") (pinfunction "SDI_4") (pintype "input"))
      (node (ref "IC6") (pin "45") (pinfunction "DIFFIO_TX_RX_B5P/DIFFOUT_B5P_45") (pintype "bidirectional"))
    )
    (net (code "40") (name "CODEC_SDO") (class "Default")
      (node (ref "IC3") (pin "5") (pinfunction "SDO_5") (pintype "output"))
      (node (ref "IC6") (pin "44") (pinfunction "DIFFIO_TX_RX_B5N/DIFFOUT_B5N_44") (pintype "bidirectional"))
    )
    (net (code "41") (name "FT232R_CTS_N") (class "Default")
      (node (ref "IC5") (pin "11") (pinfunction "~{CTS}_11") (pintype "input"))
      (node (ref "IC6") (pin "81") (pinfunction "DIFFIO_RX_R7N/DIFFOUT_R7N_81") (pintype "bidirectional"))
    )
    (net (code "42") (name "FT232R_RESET_N") (class "Default")
      (node (ref "IC5") (pin "19") (pinfunction "~{RESET}_19") (pintype "input"))
      (node (ref "IC6") (pin "84") (pinfunction "DIFFIO_RX_R11P/DIFFOUT_R11P_84") (pintype "bidirectional"))
    )
    (net (code "43") (name "FT232R_RTS_N") (class "Default")
      (node (ref "IC5") (pin "3") (pinfunction "~{RTS}_3") (pintype "output"))
      (node (ref "IC6") (pin "76") (pinfunction "DIFFIO_RX_R2N/DIFFOUT_R2N_76") (pintype "bidirectional"))
    )
    (net (code "44") (name "FT232R_RXD") (class "Default")
      (node (ref "IC5") (pin "5") (pinfunction "RXD_5") (pintype "input"))
      (node (ref "IC6") (pin "79") (pinfunction "DIFFIO_RX_R7P/DIFFOUT_R7P_79") (pintype "bidirectional"))
    )
    (net (code "45") (name "FT232R_RXLED_N") (class "Default")
      (node (ref "IC5") (pin "22") (pinfunction "CBUS1_22") (pintype "bidirectional"))
      (node (ref "UART_TX") (pin "C") (pinfunction "C_C") (pintype "passive"))
    )
    (net (code "46") (name "FT232R_TXD") (class "Default")
      (node (ref "IC5") (pin "1") (pinfunction "TXD_1") (pintype "output"))
      (node (ref "IC6") (pin "75") (pinfunction "DIFFIO_RX_R1P/DIFFOUT_R1P_75") (pintype "bidirectional"))
    )
    (net (code "47") (name "FT232R_TXLED_N") (class "Default")
      (node (ref "IC5") (pin "23") (pinfunction "CBUS0_23") (pintype "bidirectional"))
      (node (ref "UART_RX") (pin "C") (pinfunction "C_C") (pintype "passive"))
    )
    (net (code "48") (name "GND") (class "Default")
      (node (ref "C1") (pin "-") (pinfunction "-_-") (pintype "passive"))
      (node (ref "C10") (pin "2") (pinfunction "2_2") (pintype "passive"))
      (node (ref "C11") (pin "2") (pinfunction "2_2") (pintype "passive"))
      (node (ref "C18") (pin "2") (pinfunction "2_2") (pintype "passive"))
      (node (ref "C2") (pin "-") (pinfunction "-_-") (pintype "passive"))
      (node (ref "C26") (pin "-") (pinfunction "-_-") (pintype "passive"))
      (node (ref "C5") (pin "-") (pinfunction "-_-") (pintype "passive"))
      (node (ref "C9") (pin "-") (pinfunction "-_-") (pintype "passive"))
      (node (ref "IC1") (pin "1") (pinfunction "1_1") (pintype "input"))
      (node (ref "IC10") (pin "4") (pinfunction "VSS_4") (pintype "input"))
      (node (ref "IC11") (pin "6") (pinfunction "VSS_6") (pintype "input"))
      (node (ref "IC11") (pin "GND1") (pinfunction "GND1_GND1") (pintype "input"))
      (node (ref "IC11") (pin "GND2") (pinfunction "GND2_GND2") (pintype "input"))
      (node (ref "IC12") (pin "11") (pinfunction "11_11") (pintype "input"))
      (node (ref "IC13") (pin "11") (pinfunction "11_11") (pintype "input"))
      (node (ref "IC2") (pin "2") (pinfunction "GND_2") (pintype "input"))
      (node (ref "IC3") (pin "14") (pinfunction "GND_14") (pintype "input"))
      (node (ref "IC4") (pin "2") (pinfunction "V-_2") (pintype "input"))
      (node (ref "IC5") (pin "18") (pinfunction "GND_18") (pintype "power_in"))
      (node (ref "IC5") (pin "21") (pinfunction "GND_21") (pintype "power_in"))
      (node (ref "IC5") (pin "25") (pinfunction "GND_25") (pintype "power_in"))
      (node (ref "IC5") (pin "26") (pinfunction "TEST_26") (pintype "input"))
      (node (ref "IC5") (pin "7") (pinfunction "GND_7") (pintype "power_in"))
      (node (ref "IC6") (pin "104") (pinfunction "GND12_104") (pintype "input"))
      (node (ref "IC6") (pin "116") (pinfunction "GND11_116") (pintype "input"))
      (node (ref "IC6") (pin "125") (pinfunction "GND10_125") (pintype "input"))
      (node (ref "IC6") (pin "133") (pinfunction "GND9_133") (pintype "input"))
      (node (ref "IC6") (pin "137") (pinfunction "GND8_137") (pintype "input"))
      (node (ref "IC6") (pin "142") (pinfunction "GND7_142") (pintype "input"))
      (node (ref "IC6") (pin "42") (pinfunction "GND6_42") (pintype "input"))
      (node (ref "IC6") (pin "53") (pinfunction "GND5_53") (pintype "input"))
      (node (ref "IC6") (pin "63") (pinfunction "GND4_63") (pintype "input"))
      (node (ref "IC6") (pin "68") (pinfunction "GND3_68") (pintype "input"))
      (node (ref "IC6") (pin "83") (pinfunction "GND13_83") (pintype "input"))
      (node (ref "IC6") (pin "95") (pinfunction "GND1_95") (pintype "input"))
      (node (ref "IC9") (pin "4") (pinfunction "GND_4") (pintype "input"))
      (node (ref "J1") (pin "1") (pinfunction "1_1") (pintype "passive"))
      (node (ref "J1") (pin "2") (pinfunction "2_2") (pintype "passive"))
      (node (ref "J10") (pin "GND.") (pinfunction "GND._GND.") (pintype "bidirectional"))
      (node (ref "J10") (pin "GND..") (pinfunction "GND.._GND..") (pintype "bidirectional"))
      (node (ref "J2") (pin "4") (pinfunction "4_4") (pintype "passive"))
      (node (ref "J2") (pin "5") (pinfunction "5_5") (pintype "passive"))
      (node (ref "J7") (pin "10") (pinfunction "10_10") (pintype "passive"))
      (node (ref "J7") (pin "2") (pinfunction "2_2") (pintype "passive"))
      (node (ref "J8") (pin "GND") (pinfunction "GND_GND") (pintype "bidirectional"))
      (node (ref "JP2") (pin "2") (pinfunction "2_2") (pintype "passive"))
      (node (ref "JP6") (pin "2") (pinfunction "2_2") (pintype "passive"))
      (node (ref "LED_IOREF") (pin "C") (pinfunction "C_C") (pintype "passive"))
      (node (ref "R3") (pin "P$1") (pinfunction "1_P$1") (pintype "passive"))
      (node (ref "R30") (pin "P$1") (pinfunction "1_P$1") (pintype "passive"))
      (node (ref "R39") (pin "P$1") (pinfunction "1_P$1") (pintype "passive"))
      (node (ref "R4") (pin "P$1") (pinfunction "1_P$1") (pintype "passive"))
      (node (ref "R8") (pin "P$1") (pinfunction "1_P$1") (pintype "passive"))
      (node (ref "SW1") (pin "3") (pinfunction "3_3") (pintype "bidirectional"))
      (node (ref "SW1") (pin "4") (pinfunction "4_4") (pintype "bidirectional"))
      (node (ref "SW2") (pin "3") (pinfunction "3_3") (pintype "bidirectional"))
      (node (ref "SW2") (pin "4") (pinfunction "4_4") (pintype "bidirectional"))
    )
    (net (code "49") (name "IOREF") (class "Default")
      (node (ref "C18") (pin "1") (pinfunction "1_1") (pintype "passive"))
      (node (ref "IC12") (pin "19") (pinfunction "19_19") (pintype "input"))
      (node (ref "IC13") (pin "19") (pinfunction "19_19") (pintype "input"))
      (node (ref "J10") (pin "I/OREF") (pinfunction "IOREF_I/OREF") (pintype "bidirectional"))
      (node (ref "JP1") (pin "2") (pinfunction "2_2") (pintype "passive"))
      (node (ref "R22") (pin "P$2") (pinfunction "2_P$2") (pintype "passive"))
    )
    (net (code "50") (name "JTAGEN") (class "Default")
      (node (ref "IC6") (pin "15") (pinfunction "JTAGEN_15") (pintype "bidirectional"))
      (node (ref "JP2") (pin "1") (pinfunction "1_1") (pintype "passive"))
      (node (ref "R33") (pin "P$2") (pinfunction "2_P$2") (pintype "passive"))
    )
    (net (code "51") (name "JTAG_PIN6") (class "Default")
      (node (ref "IC6") (pin "46") (pinfunction "DIFFIO_TX_RX_B7N/DIFFOUT_B7N_46") (pintype "bidirectional"))
      (node (ref "J7") (pin "6") (pinfunction "6_6") (pintype "passive"))
    )
    (net (code "52") (name "JTAG_PIN7") (class "Default")
      (node (ref "IC6") (pin "60") (pinfunction "DIFFIO_TX_RX_B16P/DIFFOUT_B16P_60") (pintype "bidirectional"))
      (node (ref "J7") (pin "7") (pinfunction "7_7") (pintype "passive"))
    )
    (net (code "53") (name "JTAG_PIN8") (class "Default")
      (node (ref "IC6") (pin "47") (pinfunction "DIFFIO_TX_RX_B7P/DIFFOUT_B7P_47") (pintype "bidirectional"))
      (node (ref "J7") (pin "8") (pinfunction "8_8") (pintype "passive"))
    )
    (net (code "54") (name "MICRO_SD_CD_DAT3") (class "Default")
      (node (ref "IC11") (pin "2") (pinfunction "CD/DAT3_2") (pintype "bidirectional"))
      (node (ref "IC6") (pin "69") (pinfunction "DIFFIO_TX_RX_B27N/DIFFOUT_B27N_69") (pintype "bidirectional"))
    )
    (net (code "55") (name "MICRO_SD_CLK") (class "Default")
      (node (ref "IC11") (pin "5") (pinfunction "CLK_5") (pintype "bidirectional"))
      (node (ref "IC6") (pin "65") (pinfunction "DIFFIO_TX_RX_B23P/DIFFOUT_B23P_65") (pintype "bidirectional"))
    )
    (net (code "56") (name "MICRO_SD_CMD") (class "Default")
      (node (ref "IC11") (pin "3") (pinfunction "CMD_3") (pintype "bidirectional"))
      (node (ref "IC6") (pin "66") (pinfunction "IO66_66") (pintype "bidirectional"))
    )
    (net (code "57") (name "MICRO_SD_DAT0") (class "Default")
      (node (ref "IC11") (pin "7") (pinfunction "DAT0_7") (pintype "bidirectional"))
      (node (ref "IC6") (pin "64") (pinfunction "DIFFIO_TX_RX_B23N/DIFFOUT_B23N_64") (pintype "bidirectional"))
    )
    (net (code "58") (name "MICRO_SD_DAT1") (class "Default")
      (node (ref "IC11") (pin "8") (pinfunction "DAT1_8") (pintype "bidirectional"))
      (node (ref "IC6") (pin "62") (pinfunction "IO62_62") (pintype "bidirectional"))
    )
    (net (code "59") (name "MICRO_SD_DAT2") (class "Default")
      (node (ref "IC11") (pin "1") (pinfunction "DAT2_1") (pintype "bidirectional"))
      (node (ref "IC6") (pin "70") (pinfunction "DIFFIO_TX_RX_B27P/DIFFOUT_B27P_70") (pintype "bidirectional"))
    )
    (net (code "60") (name "Net-(C6-1)") (class "Default")
      (node (ref "C6") (pin "P$1") (pinfunction "1_P$1") (pintype "passive"))
      (node (ref "IC3") (pin "16") (pinfunction "SPKRL_16") (pintype "output"))
    )
    (net (code "61") (name "Net-(C6-2)") (class "Default")
      (node (ref "C6") (pin "P$2") (pinfunction "2_P$2") (pintype "passive"))
      (node (ref "R6") (pin "P$2") (pinfunction "2_P$2") (pintype "passive"))
    )
    (net (code "62") (name "Net-(C7-1)") (class "Default")
      (node (ref "C7") (pin "P$1") (pinfunction "1_P$1") (pintype "passive"))
      (node (ref "IC3") (pin "1") (pinfunction "SPKRR_1") (pintype "output"))
    )
    (net (code "63") (name "Net-(C7-2)") (class "Default")
      (node (ref "C7") (pin "P$2") (pinfunction "2_P$2") (pintype "passive"))
      (node (ref "R29") (pin "P$2") (pinfunction "2_P$2") (pintype "passive"))
    )
    (net (code "64") (name "Net-(C19-1)") (class "Default")
      (node (ref "C19") (pin "P$1") (pinfunction "1_P$1") (pintype "passive"))
      (node (ref "IC6") (pin "6") (pinfunction "DIFFIO_RX_L1N/DIFFOUT_L1N/ADC1IN1_6") (pintype "bidirectional"))
      (node (ref "R23") (pin "P$2") (pinfunction "2_P$2") (pintype "passive"))
    )
    (net (code "65") (name "Net-(C20-1)") (class "Default")
      (node (ref "C20") (pin "P$1") (pinfunction "1_P$1") (pintype "passive"))
      (node (ref "IC6") (pin "7") (pinfunction "DIFFIO_RX_L1P/DIFFOUT_L1P/ADC1IN2_7") (pintype "bidirectional"))
      (node (ref "R24") (pin "P$2") (pinfunction "2_P$2") (pintype "passive"))
    )
    (net (code "66") (name "Net-(C21-1)") (class "Default")
      (node (ref "C21") (pin "P$1") (pinfunction "1_P$1") (pintype "passive"))
      (node (ref "IC6") (pin "8") (pinfunction "DIFFIO_RX_L3N/DIFFOUT_L3N/ADC1IN3_8") (pintype "bidirectional"))
      (node (ref "R25") (pin "P$2") (pinfunction "2_P$2") (pintype "passive"))
    )
    (net (code "67") (name "Net-(C22-1)") (class "Default")
      (node (ref "C22") (pin "P$1") (pinfunction "1_P$1") (pintype "passive"))
      (node (ref "IC6") (pin "10") (pinfunction "DIFFIO_RX_L3P/DIFFOUT_L3P/ADC1IN4_10") (pintype "bidirectional"))
      (node (ref "R26") (pin "P$2") (pinfunction "2_P$2") (pintype "passive"))
    )
    (net (code "68") (name "Net-(C23-1)") (class "Default")
      (node (ref "C23") (pin "P$1") (pinfunction "1_P$1") (pintype "passive"))
      (node (ref "IC6") (pin "11") (pinfunction "DIFFIO_RX_L5N/DIFFOUT_L5N/ADC1IN5_11") (pintype "bidirectional"))
      (node (ref "R27") (pin "P$1") (pinfunction "1_P$1") (pintype "passive"))
    )
    (net (code "69") (name "Net-(C24-1)") (class "Default")
      (node (ref "C24") (pin "P$1") (pinfunction "1_P$1") (pintype "passive"))
      (node (ref "IC6") (pin "12") (pinfunction "DIFFIO_RX_L5P/DIFFOUT_L5P/ADC1IN6_12") (pintype "bidirectional"))
      (node (ref "R28") (pin "P$1") (pinfunction "1_P$1") (pintype "passive"))
    )
    (net (code "70") (name "Net-(D1-Pad2)") (class "Default")
      (node (ref "D1") (pin "2") (pinfunction "2_2") (pintype "passive"))
      (node (ref "J1") (pin "3") (pinfunction "3_3") (pintype "passive"))
    )
    (net (code "71") (name "Net-(F1-Pad1)") (class "Default")
      (node (ref "F1") (pin "1") (pinfunction "1_1") (pintype "passive"))
      (node (ref "J2") (pin "1") (pinfunction "1_1") (pintype "passive"))
    )
    (net (code "72") (name "Net-(IC2-EN)") (class "Default")
      (node (ref "IC2") (pin "1") (pinfunction "EN_1") (pintype "input"))
      (node (ref "R1") (pin "P$2") (pinfunction "2_P$2") (pintype "passive"))
    )
    (net (code "73") (name "Net-(IC2-FB)") (class "Default")
      (node (ref "C4") (pin "2") (pinfunction "2_2") (pintype "passive"))
      (node (ref "IC2") (pin "5") (pinfunction "FB_5") (pintype "passive"))
      (node (ref "R2") (pin "P$1") (pinfunction "1_P$1") (pintype "passive"))
      (node (ref "R3") (pin "P$2") (pinfunction "2_P$2") (pintype "passive"))
    )
    (net (code "74") (name "Net-(IC2-LX)") (class "Default")
      (node (ref "IC2") (pin "3") (pinfunction "LX_3") (pintype "input"))
      (node (ref "L1") (pin "1") (pinfunction "1_1") (pintype "passive"))
    )
    (net (code "75") (name "Net-(IC3-MBIAS)") (class "Default")
      (node (ref "IC3") (pin "2") (pinfunction "MBIAS_2") (pintype "output"))
      (node (ref "R5") (pin "P$1") (pinfunction "1_P$1") (pintype "passive"))
    )
    (net (code "76") (name "Net-(IC3-MIC)") (class "Default")
      (node (ref "C3") (pin "1") (pinfunction "1_1") (pintype "passive"))
      (node (ref "IC3") (pin "10") (pinfunction "MIC_10") (pintype "input"))
    )
    (net (code "77") (name "Net-(IC4-+IN)") (class "Default")
      (node (ref "IC4") (pin "1") (pinfunction "+IN_1") (pintype "input"))
      (node (ref "R7") (pin "P$1") (pinfunction "1_P$1") (pintype "passive"))
      (node (ref "R8") (pin "P$2") (pinfunction "2_P$2") (pintype "passive"))
    )
    (net (code "78") (name "Net-(IC4-OUT)") (class "Default")
      (node (ref "IC4") (pin "4") (pinfunction "OUT_4") (pintype "output"))
      (node (ref "PMOS1") (pin "3") (pinfunction "G_3") (pintype "passive"))
    )
    (net (code "79") (name "Net-(IC5-3V3OUT)") (class "Default")
      (node (ref "C11") (pin "1") (pinfunction "1_1") (pintype "passive"))
      (node (ref "IC5") (pin "17") (pinfunction "3V3OUT_17") (pintype "output"))
      (node (ref "IC5") (pin "4") (pinfunction "VCCIO_4") (pintype "power_in"))
      (node (ref "R10") (pin "P$2") (pinfunction "2_P$2") (pintype "passive"))
      (node (ref "R9") (pin "P$2") (pinfunction "2_P$2") (pintype "passive"))
    )
    (net (code "80") (name "Net-(IC5-USBDM)") (class "Default")
      (node (ref "IC5") (pin "16") (pinfunction "USBDM_16") (pintype "bidirectional"))
      (node (ref "J2") (pin "2") (pinfunction "2_2") (pintype "passive"))
    )
    (net (code "81") (name "Net-(IC5-USBDP)") (class "Default")
      (node (ref "IC5") (pin "15") (pinfunction "USBDP_15") (pintype "bidirectional"))
      (node (ref "J2") (pin "3") (pinfunction "3_3") (pintype "passive"))
    )
    (net (code "82") (name "Net-(IC6A-REFGND{slash}GND2)") (class "Default")
      (node (ref "F7") (pin "2") (pinfunction "2_2") (pintype "passive"))
      (node (ref "IC6") (pin "4") (pinfunction "REFGND/GND2_4") (pintype "input"))
    )
    (net (code "83") (name "Net-(IC6A-VCCA4)") (class "Default")
      (node (ref "F5") (pin "2") (pinfunction "2_2") (pintype "passive"))
      (node (ref "IC6") (pin "143") (pinfunction "VCCA4_143") (pintype "input"))
      (node (ref "IC6") (pin "2") (pinfunction "VCCA6_2") (pintype "input"))
    )
    (net (code "84") (name "Net-(IC6B-VCCIO1A)") (class "Default")
      (node (ref "F4") (pin "2") (pinfunction "2_2") (pintype "passive"))
      (node (ref "IC6") (pin "9") (pinfunction "VCCIO1A_9") (pintype "input"))
    )
    (net (code "85") (name "Net-(IC6G-DIFFIO_RX_R10P{slash}DIFFOUT_R10P)") (class "Default")
      (node (ref "IC6") (pin "85") (pinfunction "DIFFIO_RX_R10P/DIFFOUT_R10P_85") (pintype "bidirectional"))
      (node (ref "SW2") (pin "1") (pinfunction "1_1") (pintype "bidirectional"))
      (node (ref "SW2") (pin "2") (pinfunction "2_2") (pintype "bidirectional"))
    )
    (net (code "86") (name "Net-(IC6H-CLK2P{slash}DIFFIO_RX_R14P{slash}DIFFOUT_R14P)") (class "Default")
      (node (ref "IC6") (pin "88") (pinfunction "CLK2P/DIFFIO_RX_R14P/DIFFOUT_R14P_88") (pintype "bidirectional"))
      (node (ref "IC9") (pin "5") (pinfunction "OUT_5") (pintype "output"))
    )
    (net (code "87") (name "Net-(IC6J-CONFIG_SEL)") (class "Default")
      (node (ref "IC6") (pin "126") (pinfunction "CONFIG_SEL_126") (pintype "bidirectional"))
      (node (ref "JP6") (pin "1") (pinfunction "1_1") (pintype "passive"))
      (node (ref "R40") (pin "P$2") (pinfunction "2_P$2") (pintype "passive"))
    )
    (net (code "88") (name "Net-(IC6J-CONF_DONE{slash}DIFFIO_RX_T24N{slash}DIFFOUT_T24N)") (class "Default")
      (node (ref "IC6") (pin "138") (pinfunction "CONF_DONE/DIFFIO_RX_T24N/DIFFOUT_T24N_138") (pintype "bidirectional"))
      (node (ref "R38") (pin "P$1") (pinfunction "1_P$1") (pintype "passive"))
    )
    (net (code "89") (name "Net-(IC6J-DEV_CLRN{slash}DIFFIO_RX_T16N{slash}DIFFOUT_T16N)") (class "Default")
      (node (ref "IC6") (pin "121") (pinfunction "DEV_CLRN/DIFFIO_RX_T16N/DIFFOUT_T16N_121") (pintype "bidirectional"))
      (node (ref "R41") (pin "P$2") (pinfunction "2_P$2") (pintype "passive"))
    )
    (net (code "90") (name "Net-(IC6J-DIFFIO_RX_T20N{slash}DIFFOUT_T20N)") (class "Default")
      (node (ref "IC6") (pin "131") (pinfunction "DIFFIO_RX_T20N/DIFFOUT_T20N_131") (pintype "bidirectional"))
      (node (ref "LED2") (pin "C") (pinfunction "C_C") (pintype "passive"))
    )
    (net (code "91") (name "Net-(IC6J-DIFFIO_RX_T20P{slash}DIFFOUT_T20P)") (class "Default")
      (node (ref "IC6") (pin "130") (pinfunction "DIFFIO_RX_T20P/DIFFOUT_T20P_130") (pintype "bidirectional"))
      (node (ref "LED1") (pin "C") (pinfunction "C_C") (pintype "passive"))
    )
    (net (code "92") (name "Net-(IC6J-DIFFIO_RX_T22P{slash}DIFFOUT_T22P)") (class "Default")
      (node (ref "IC6") (pin "132") (pinfunction "DIFFIO_RX_T22P/DIFFOUT_T22P_132") (pintype "bidirectional"))
      (node (ref "LED3") (pin "C") (pinfunction "C_C") (pintype "passive"))
    )
    (net (code "93") (name "Net-(IC6J-NCONFIG)") (class "Default")
      (node (ref "IC6") (pin "129") (pinfunction "NCONFIG_129") (pintype "input"))
      (node (ref "R36") (pin "P$2") (pinfunction "2_P$2") (pintype "passive"))
    )
    (net (code "94") (name "Net-(IC6J-NSTATUS{slash}DIFFIO_RX_T24P{slash}DIFFOUT_T24P)") (class "Default")
      (node (ref "IC6") (pin "136") (pinfunction "NSTATUS/DIFFIO_RX_T24P/DIFFOUT_T24P_136") (pintype "bidirectional"))
      (node (ref "R37") (pin "P$1") (pinfunction "1_P$1") (pintype "passive"))
    )
    (net (code "95") (name "Net-(MIC1-1)") (class "Default")
      (node (ref "C3") (pin "2") (pinfunction "2_2") (pintype "passive"))
      (node (ref "MIC1") (pin "2") (pinfunction "1_2") (pintype "input"))
      (node (ref "R5") (pin "P$2") (pinfunction "2_P$2") (pintype "passive"))
    )
    (net (code "96") (name "Net-(R6-1)") (class "Default")
      (node (ref "J4") (pin "1") (pinfunction "1_1") (pintype "passive"))
      (node (ref "R6") (pin "P$1") (pinfunction "1_P$1") (pintype "passive"))
    )
    (net (code "97") (name "Net-(R9-1)") (class "Default")
      (node (ref "R9") (pin "P$1") (pinfunction "1_P$1") (pintype "passive"))
      (node (ref "UART_RX") (pin "A") (pinfunction "A_A") (pintype "passive"))
    )
    (net (code "98") (name "Net-(R10-1)") (class "Default")
      (node (ref "R10") (pin "P$1") (pinfunction "1_P$1") (pintype "passive"))
      (node (ref "UART_TX") (pin "A") (pinfunction "A_A") (pintype "passive"))
    )
    (net (code "99") (name "Net-(R11-2)") (class "Default")
      (node (ref "C12") (pin "1") (pinfunction "1_1") (pintype "passive"))
      (node (ref "IC7") (pin "3") (pinfunction "3_3") (pintype "input"))
      (node (ref "PT1") (pin "1A") (pinfunction "1A_1A") (pintype "passive"))
      (node (ref "R11") (pin "P$2") (pinfunction "2_P$2") (pintype "passive"))
    )
    (net (code "100") (name "Net-(R12-2)") (class "Default")
      (node (ref "C13") (pin "1") (pinfunction "1_1") (pintype "passive"))
      (node (ref "IC7") (pin "5") (pinfunction "5_5") (pintype "input"))
      (node (ref "R12") (pin "P$2") (pinfunction "2_P$2") (pintype "passive"))
      (node (ref "R13") (pin "P$1") (pinfunction "1_P$1") (pintype "passive"))
    )
    (net (code "101") (name "Net-(R14-2)") (class "Default")
      (node (ref "C14") (pin "1") (pinfunction "1_1") (pintype "passive"))
      (node (ref "IC8") (pin "3") (pinfunction "3_3") (pintype "input"))
      (node (ref "R14") (pin "P$2") (pinfunction "2_P$2") (pintype "passive"))
      (node (ref "R15") (pin "P$2") (pinfunction "2_P$2") (pintype "passive"))
    )
    (net (code "102") (name "Net-(R16-2)") (class "Default")
      (node (ref "C15") (pin "1") (pinfunction "1_1") (pintype "passive"))
      (node (ref "IC8") (pin "5") (pinfunction "5_5") (pintype "input"))
      (node (ref "R16") (pin "P$2") (pinfunction "2_P$2") (pintype "passive"))
      (node (ref "R17") (pin "P$2") (pinfunction "2_P$2") (pintype "passive"))
    )
    (net (code "103") (name "Net-(R18-2)") (class "Default")
      (node (ref "C16") (pin "1") (pinfunction "1_1") (pintype "passive"))
      (node (ref "IC8") (pin "10") (pinfunction "10_10") (pintype "input"))
      (node (ref "R18") (pin "P$2") (pinfunction "2_P$2") (pintype "passive"))
      (node (ref "R19") (pin "P$1") (pinfunction "1_P$1") (pintype "passive"))
    )
    (net (code "104") (name "Net-(R20-2)") (class "Default")
      (node (ref "C17") (pin "1") (pinfunction "1_1") (pintype "passive"))
      (node (ref "IC8") (pin "12") (pinfunction "12_12") (pintype "input"))
      (node (ref "R20") (pin "P$2") (pinfunction "2_P$2") (pintype "passive"))
      (node (ref "R21") (pin "P$2") (pinfunction "2_P$2") (pintype "passive"))
    )
    (net (code "105") (name "Net-(R22-1)") (class "Default")
      (node (ref "LED_IOREF") (pin "A") (pinfunction "A_A") (pintype "passive"))
      (node (ref "R22") (pin "P$1") (pinfunction "1_P$1") (pintype "passive"))
    )
    (net (code "106") (name "Net-(R29-1)") (class "Default")
      (node (ref "J4") (pin "4") (pinfunction "4_4") (pintype "passive"))
      (node (ref "R29") (pin "P$1") (pinfunction "1_P$1") (pintype "passive"))
    )
    (net (code "107") (name "Net-(R42-1)") (class "Default")
      (node (ref "LED1") (pin "A") (pinfunction "A_A") (pintype "passive"))
      (node (ref "R42") (pin "P$1") (pinfunction "1_P$1") (pintype "passive"))
    )
    (net (code "108") (name "Net-(R43-1)") (class "Default")
      (node (ref "LED2") (pin "A") (pinfunction "A_A") (pintype "passive"))
      (node (ref "R43") (pin "P$1") (pinfunction "1_P$1") (pintype "passive"))
    )
    (net (code "109") (name "Net-(R47-1)") (class "Default")
      (node (ref "LED3") (pin "A") (pinfunction "A_A") (pintype "passive"))
      (node (ref "R47") (pin "P$1") (pinfunction "1_P$1") (pintype "passive"))
    )
    (net (code "110") (name "PIN0_RX") (class "Default")
      (node (ref "IC12") (pin "20") (pinfunction "20_20") (pintype "bidirectional"))
      (node (ref "J9") (pin "0") (pinfunction "0(RX)_0") (pintype "bidirectional"))
    )
    (net (code "111") (name "PIN1_TX") (class "Default")
      (node (ref "IC12") (pin "18") (pinfunction "18_18") (pintype "bidirectional"))
      (node (ref "J9") (pin "1") (pinfunction "1(TX)_1") (pintype "bidirectional"))
    )
    (net (code "112") (name "PIN2") (class "Default")
      (node (ref "IC12") (pin "17") (pinfunction "17_17") (pintype "bidirectional"))
      (node (ref "J9") (pin "2") (pinfunction "2_2") (pintype "bidirectional"))
    )
    (net (code "113") (name "PIN3~{}") (class "Default")
      (node (ref "IC12") (pin "16") (pinfunction "16_16") (pintype "bidirectional"))
      (node (ref "J9") (pin "3") (pinfunction "3~{}_3") (pintype "bidirectional"))
    )
    (net (code "114") (name "PIN4") (class "Default")
      (node (ref "IC12") (pin "15") (pinfunction "15_15") (pintype "bidirectional"))
      (node (ref "J9") (pin "4") (pinfunction "4_4") (pintype "bidirectional"))
    )
    (net (code "115") (name "PIN5~{}") (class "Default")
      (node (ref "IC12") (pin "14") (pinfunction "14_14") (pintype "bidirectional"))
      (node (ref "J9") (pin "5") (pinfunction "5~{}_5") (pintype "bidirectional"))
    )
    (net (code "116") (name "PIN6~{}") (class "Default")
      (node (ref "IC12") (pin "13") (pinfunction "13_13") (pintype "bidirectional"))
      (node (ref "J9") (pin "6") (pinfunction "6~{}_6") (pintype "bidirectional"))
    )
    (net (code "117") (name "PIN7") (class "Default")
      (node (ref "IC12") (pin "12") (pinfunction "12_12") (pintype "bidirectional"))
      (node (ref "J9") (pin "7") (pinfunction "7_7") (pintype "bidirectional"))
    )
    (net (code "118") (name "PIN8") (class "Default")
      (node (ref "IC13") (pin "20") (pinfunction "20_20") (pintype "bidirectional"))
      (node (ref "J8") (pin "8") (pinfunction "8_8") (pintype "bidirectional"))
    )
    (net (code "119") (name "PIN9~{}") (class "Default")
      (node (ref "IC13") (pin "18") (pinfunction "18_18") (pintype "bidirectional"))
      (node (ref "J8") (pin "9") (pinfunction "9~{}_9") (pintype "bidirectional"))
    )
    (net (code "120") (name "PIN10~{}") (class "Default")
      (node (ref "IC13") (pin "17") (pinfunction "17_17") (pintype "bidirectional"))
      (node (ref "J8") (pin "10") (pinfunction "10~{}_10") (pintype "bidirectional"))
    )
    (net (code "121") (name "PIN11~{}") (class "Default")
      (node (ref "IC13") (pin "16") (pinfunction "16_16") (pintype "bidirectional"))
      (node (ref "J8") (pin "11") (pinfunction "11~{}_11") (pintype "bidirectional"))
    )
    (net (code "122") (name "PIN12") (class "Default")
      (node (ref "IC13") (pin "15") (pinfunction "15_15") (pintype "bidirectional"))
      (node (ref "J8") (pin "12") (pinfunction "12_12") (pintype "bidirectional"))
    )
    (net (code "123") (name "PIN13") (class "Default")
      (node (ref "IC13") (pin "14") (pinfunction "14_14") (pintype "bidirectional"))
      (node (ref "J8") (pin "13") (pinfunction "13_13") (pintype "bidirectional"))
    )
    (net (code "124") (name "RESET_N") (class "Default")
      (node (ref "IC6") (pin "74") (pinfunction "DIFFIO_RX_R2P/DIFFOUT_R2P_74") (pintype "bidirectional"))
      (node (ref "J10") (pin "RESET") (pinfunction "RESET_RESET") (pintype "bidirectional"))
      (node (ref "R32") (pin "P$2") (pinfunction "2_P$2") (pintype "passive"))
      (node (ref "SW1") (pin "1") (pinfunction "1_1") (pintype "bidirectional"))
      (node (ref "SW1") (pin "2") (pinfunction "2_2") (pintype "bidirectional"))
    )
    (net (code "125") (name "SCL") (class "Default")
      (node (ref "IC13") (pin "12") (pinfunction "12_12") (pintype "bidirectional"))
      (node (ref "J8") (pin "SCL") (pinfunction "SCL_SCL") (pintype "bidirectional"))
    )
    (net (code "126") (name "SDA") (class "Default")
      (node (ref "IC13") (pin "13") (pinfunction "13_13") (pintype "bidirectional"))
      (node (ref "J8") (pin "SDA") (pinfunction "SDA_SDA") (pintype "bidirectional"))
    )
    (net (code "127") (name "SRAM_CS_N") (class "Default")
      (node (ref "IC10") (pin "1") (pinfunction "CS_N_1") (pintype "input"))
      (node (ref "IC6") (pin "29") (pinfunction "CLK1P/DIFFIO_RX_L20P/DIFFOUT_L20P_29") (pintype "bidirectional"))
    )
    (net (code "128") (name "SRAM_SCK") (class "Default")
      (node (ref "IC10") (pin "6") (pinfunction "SCK_6") (pintype "input"))
      (node (ref "IC6") (pin "27") (pinfunction "CLK0P/DIFFIO_RX_L18P/DIFFOUT_L18P_27") (pintype "bidirectional"))
    )
    (net (code "129") (name "SRAM_SIO0") (class "Default")
      (node (ref "IC10") (pin "5") (pinfunction "SI/SIO0_5") (pintype "bidirectional"))
      (node (ref "IC6") (pin "28") (pinfunction "CLK1N/DIFFIO_RX_L20N/DIFFOUT_L20N_28") (pintype "bidirectional"))
    )
    (net (code "130") (name "SRAM_SIO1") (class "Default")
      (node (ref "IC10") (pin "2") (pinfunction "SO/SIO1_2") (pintype "bidirectional"))
      (node (ref "IC6") (pin "32") (pinfunction "PLL_L_CLKOUTN/DIFFIO_RX_L27N/DIFFOUT_L27N_32") (pintype "bidirectional"))
    )
    (net (code "131") (name "SRAM_SIO2") (class "Default")
      (node (ref "IC10") (pin "3") (pinfunction "NC/SIO2_3") (pintype "bidirectional"))
      (node (ref "IC6") (pin "33") (pinfunction "PLL_L_CLKOUTP/DIFFIO_RX_L27P/DIFFOUT_L27P_33") (pintype "bidirectional"))
    )
    (net (code "132") (name "SRAM_SIO3") (class "Default")
      (node (ref "IC10") (pin "7") (pinfunction "HOLD_N/SIO3_7") (pintype "bidirectional"))
      (node (ref "IC6") (pin "26") (pinfunction "CLK0N/DIFFIO_RX_L18N/DIFFOUT_L18N_26") (pintype "bidirectional"))
    )
    (net (code "133") (name "TCK") (class "Default")
      (node (ref "IC6") (pin "18") (pinfunction "TCK/DIFFIO_RX_L11P/DIFFOUT_L11P_18") (pintype "bidirectional"))
      (node (ref "J7") (pin "1") (pinfunction "1_1") (pintype "passive"))
      (node (ref "R39") (pin "P$2") (pinfunction "2_P$2") (pintype "passive"))
    )
    (net (code "134") (name "TDI") (class "Default")
      (node (ref "IC6") (pin "19") (pinfunction "TDI/DIFFIO_RX_L12N/DIFFOUT_L12N_19") (pintype "bidirectional"))
      (node (ref "J7") (pin "9") (pinfunction "9_9") (pintype "passive"))
      (node (ref "R34") (pin "P$1") (pinfunction "1_P$1") (pintype "passive"))
    )
    (net (code "135") (name "TDO") (class "Default")
      (node (ref "IC6") (pin "20") (pinfunction "TDO/DIFFIO_RX_L12P/DIFFOUT_L12P_20") (pintype "bidirectional"))
      (node (ref "J7") (pin "3") (pinfunction "3_3") (pintype "passive"))
    )
    (net (code "136") (name "TMS") (class "Default")
      (node (ref "IC6") (pin "16") (pinfunction "TMS/DIFFIO_RX_L11N/DIFFOUT_L11N_16") (pintype "bidirectional"))
      (node (ref "J7") (pin "5") (pinfunction "5_5") (pintype "passive"))
      (node (ref "R35") (pin "P$1") (pinfunction "1_P$1") (pintype "passive"))
    )
    (net (code "137") (name "USBVCC") (class "Default")
      (node (ref "C10") (pin "1") (pinfunction "1_1") (pintype "passive"))
      (node (ref "C9") (pin "+") (pinfunction "+_+") (pintype "passive"))
      (node (ref "F1") (pin "2") (pinfunction "2_2") (pintype "passive"))
      (node (ref "IC5") (pin "20") (pinfunction "VCC_20") (pintype "power_in"))
      (node (ref "PMOS1") (pin "1") (pinfunction "D1_1") (pintype "passive"))
      (node (ref "PMOS1") (pin "2") (pinfunction "D2_2") (pintype "passive"))
      (node (ref "PMOS1") (pin "5") (pinfunction "D3_5") (pintype "passive"))
      (node (ref "PMOS1") (pin "6") (pinfunction "D4_6") (pintype "passive"))
    )
    (net (code "138") (name "VIN") (class "Default")
      (node (ref "C1") (pin "+") (pinfunction "+_+") (pintype "passive"))
      (node (ref "D1") (pin "1") (pinfunction "1_1") (pintype "passive"))
      (node (ref "IC1") (pin "3") (pinfunction "3_3") (pintype "input"))
      (node (ref "J10") (pin "VIN") (pinfunction "VIN_VIN") (pintype "bidirectional"))
      (node (ref "R7") (pin "P$2") (pinfunction "2_P$2") (pintype "passive"))
    )
    (net (code "139") (name "unconnected-(IC3-HDST-Pad3)") (class "Default")
      (node (ref "IC3") (pin "3") (pinfunction "HDST_3") (pintype "output"))
    )
    (net (code "140") (name "unconnected-(IC3-LINEI-Pad11)") (class "Default")
      (node (ref "IC3") (pin "11") (pinfunction "LINEI_11") (pintype "input"))
    )
    (net (code "141") (name "unconnected-(IC3-LINEO-Pad15)") (class "Default")
      (node (ref "IC3") (pin "15") (pinfunction "LINEO_15") (pintype "output"))
    )
    (net (code "142") (name "unconnected-(IC5-CBUS2-Pad13)") (class "Default")
      (node (ref "IC5") (pin "13") (pinfunction "CBUS2_13") (pintype "bidirectional"))
    )
    (net (code "143") (name "unconnected-(IC5-CBUS3-Pad14)") (class "Default")
      (node (ref "IC5") (pin "14") (pinfunction "CBUS3_14") (pintype "bidirectional"))
    )
    (net (code "144") (name "unconnected-(IC5-CBUS4-Pad12)") (class "Default")
      (node (ref "IC5") (pin "12") (pinfunction "CBUS4_12") (pintype "bidirectional"))
    )
    (net (code "145") (name "unconnected-(IC5-OSCI-Pad27)") (class "Default")
      (node (ref "IC5") (pin "27") (pinfunction "OSCI_27") (pintype "input"))
    )
    (net (code "146") (name "unconnected-(IC5-OSCO-Pad28)") (class "Default")
      (node (ref "IC5") (pin "28") (pinfunction "OSCO_28") (pintype "output"))
    )
    (net (code "147") (name "unconnected-(IC5-~{DCD}-Pad10)") (class "Default")
      (node (ref "IC5") (pin "10") (pinfunction "~{DCD}_10") (pintype "input"))
    )
    (net (code "148") (name "unconnected-(IC5-~{DSR}-Pad9)") (class "Default")
      (node (ref "IC5") (pin "9") (pinfunction "~{DSR}_9") (pintype "input"))
    )
    (net (code "149") (name "unconnected-(IC5-~{DTR}-Pad2)") (class "Default")
      (node (ref "IC5") (pin "2") (pinfunction "~{DTR}_2") (pintype "output"))
    )
    (net (code "150") (name "unconnected-(IC5-~{RI}-Pad6)") (class "Default")
      (node (ref "IC5") (pin "6") (pinfunction "~{RI}_6") (pintype "input"))
    )
    (net (code "151") (name "unconnected-(IC6C-DIFFIO_RX_L14N{slash}DIFFOUT_L14N-Pad21)") (class "Default")
      (node (ref "IC6") (pin "21") (pinfunction "DIFFIO_RX_L14N/DIFFOUT_L14N_21") (pintype "bidirectional"))
    )
    (net (code "152") (name "unconnected-(IC6C-DIFFIO_RX_L14P{slash}DIFFOUT_L14P-Pad22)") (class "Default")
      (node (ref "IC6") (pin "22") (pinfunction "DIFFIO_RX_L14P/DIFFOUT_L14P_22") (pintype "bidirectional"))
    )
    (net (code "153") (name "unconnected-(IC6C-DIFFIO_RX_L16N{slash}DIFFOUT_L16N-Pad24)") (class "Default")
      (node (ref "IC6") (pin "24") (pinfunction "DIFFIO_RX_L16N/DIFFOUT_L16N_24") (pintype "bidirectional"))
    )
    (net (code "154") (name "unconnected-(IC6C-DIFFIO_RX_L16P{slash}DIFFOUT_L16P-Pad25)") (class "Default")
      (node (ref "IC6") (pin "25") (pinfunction "DIFFIO_RX_L16P/DIFFOUT_L16P_25") (pintype "bidirectional"))
    )
    (net (code "155") (name "unconnected-(IC6C-VREFB1N0-Pad17)") (class "Default")
      (node (ref "IC6") (pin "17") (pinfunction "VREFB1N0_17") (pintype "input"))
    )
    (net (code "156") (name "unconnected-(IC6D-VREFB2N0-Pad30)") (class "Default")
      (node (ref "IC6") (pin "30") (pinfunction "VREFB2N0_30") (pintype "input"))
    )
    (net (code "157") (name "unconnected-(IC6E-VREFB3N0-Pad48)") (class "Default")
      (node (ref "IC6") (pin "48") (pinfunction "VREFB3N0_48") (pintype "input"))
    )
    (net (code "158") (name "unconnected-(IC6F-VREFB4N0-Pad61)") (class "Default")
      (node (ref "IC6") (pin "61") (pinfunction "VREFB4N0_61") (pintype "input"))
    )
    (net (code "159") (name "unconnected-(IC6G-DIFFIO_RX_R1N{slash}DIFFOUT_R1N-Pad77)") (class "Default")
      (node (ref "IC6") (pin "77") (pinfunction "DIFFIO_RX_R1N/DIFFOUT_R1N_77") (pintype "bidirectional"))
    )
    (net (code "160") (name "unconnected-(IC6G-DIFFIO_RX_R10N{slash}DIFFOUT_R10N-Pad87)") (class "Default")
      (node (ref "IC6") (pin "87") (pinfunction "DIFFIO_RX_R10N/DIFFOUT_R10N_87") (pintype "bidirectional"))
    )
    (net (code "161") (name "unconnected-(IC6G-DIFFIO_RX_R11N{slash}DIFFOUT_R11N-Pad86)") (class "Default")
      (node (ref "IC6") (pin "86") (pinfunction "DIFFIO_RX_R11N/DIFFOUT_R11N_86") (pintype "bidirectional"))
    )
    (net (code "162") (name "unconnected-(IC6G-IO78-Pad78)") (class "Default")
      (node (ref "IC6") (pin "78") (pinfunction "IO78_78") (pintype "bidirectional"))
    )
    (net (code "163") (name "unconnected-(IC6G-VREFB5N0-Pad80)") (class "Default")
      (node (ref "IC6") (pin "80") (pinfunction "VREFB5N0_80") (pintype "input"))
    )
    (net (code "164") (name "unconnected-(IC6H-CLK2N{slash}DIFFIO_RX_R14N{slash}DIFFOUT_R14N-Pad89)") (class "Default")
      (node (ref "IC6") (pin "89") (pinfunction "CLK2N/DIFFIO_RX_R14N/DIFFOUT_R14N_89") (pintype "bidirectional"))
    )
    (net (code "165") (name "unconnected-(IC6H-CLK3N{slash}DIFFIO_RX_R16N{slash}DIFFOUT_R16N-Pad91)") (class "Default")
      (node (ref "IC6") (pin "91") (pinfunction "CLK3N/DIFFIO_RX_R16N/DIFFOUT_R16N_91") (pintype "bidirectional"))
    )
    (net (code "166") (name "unconnected-(IC6H-CLK3P{slash}DIFFIO_RX_R16P{slash}DIFFOUT_R16P-Pad90)") (class "Default")
      (node (ref "IC6") (pin "90") (pinfunction "CLK3P/DIFFIO_RX_R16P/DIFFOUT_R16P_90") (pintype "bidirectional"))
    )
    (net (code "167") (name "unconnected-(IC6H-DIFFIO_RX_R33N{slash}DIFFOUT_R33N-Pad106)") (class "Default")
      (node (ref "IC6") (pin "106") (pinfunction "DIFFIO_RX_R33N/DIFFOUT_R33N_106") (pintype "bidirectional"))
    )
    (net (code "168") (name "unconnected-(IC6H-DIFFIO_RX_R33P{slash}DIFFOUT_R33P-Pad105)") (class "Default")
      (node (ref "IC6") (pin "105") (pinfunction "DIFFIO_RX_R33P/DIFFOUT_R33P_105") (pintype "bidirectional"))
    )
    (net (code "169") (name "unconnected-(IC6H-VREFB6N0-Pad97)") (class "Default")
      (node (ref "IC6") (pin "97") (pinfunction "VREFB6N0_97") (pintype "input"))
    )
    (net (code "170") (name "unconnected-(IC6I-DIFFIO_RX_T1N{slash}DIFFOUT_T1N-Pad111)") (class "Default")
      (node (ref "IC6") (pin "111") (pinfunction "DIFFIO_RX_T1N/DIFFOUT_T1N_111") (pintype "bidirectional"))
    )
    (net (code "171") (name "unconnected-(IC6I-DIFFIO_RX_T1P{slash}DIFFOUT_T1P-Pad110)") (class "Default")
      (node (ref "IC6") (pin "110") (pinfunction "DIFFIO_RX_T1P/DIFFOUT_T1P_110") (pintype "bidirectional"))
    )
    (net (code "172") (name "unconnected-(IC6I-DIFFIO_RX_T10N{slash}DIFFOUT_T10N-Pad119)") (class "Default")
      (node (ref "IC6") (pin "119") (pinfunction "DIFFIO_RX_T10N/DIFFOUT_T10N_119") (pintype "bidirectional"))
    )
    (net (code "173") (name "unconnected-(IC6I-DIFFIO_RX_T10P{slash}DIFFOUT_T10P-Pad118)") (class "Default")
      (node (ref "IC6") (pin "118") (pinfunction "DIFFIO_RX_T10P/DIFFOUT_T10P_118") (pintype "bidirectional"))
    )
    (net (code "174") (name "unconnected-(IC6I-IO113-Pad113)") (class "Default")
      (node (ref "IC6") (pin "113") (pinfunction "IO113_113") (pintype "bidirectional"))
    )
    (net (code "175") (name "unconnected-(IC6I-IO114-Pad114)") (class "Default")
      (node (ref "IC6") (pin "114") (pinfunction "IO114_114") (pintype "bidirectional"))
    )
    (net (code "176") (name "unconnected-(IC6I-VREFB7N0-Pad112)") (class "Default")
      (node (ref "IC6") (pin "112") (pinfunction "VREFB7N0_112") (pintype "input"))
    )
    (net (code "177") (name "unconnected-(IC6J-CRC_ERROR{slash}DIFFIO_RX_T22N{slash}DIFFOUT_T22N-Pad134)") (class "Default")
      (node (ref "IC6") (pin "134") (pinfunction "CRC_ERROR/DIFFIO_RX_T22N/DIFFOUT_T22N_134") (pintype "bidirectional"))
    )
    (net (code "178") (name "unconnected-(IC6J-DEV_OE-Pad122)") (class "Default")
      (node (ref "IC6") (pin "122") (pinfunction "DEV_OE_122") (pintype "bidirectional"))
    )
    (net (code "179") (name "unconnected-(IC6J-DIFFIO_RX_T16P{slash}DIFFOUT_T16P-Pad120)") (class "Default")
      (node (ref "IC6") (pin "120") (pinfunction "DIFFIO_RX_T16P/DIFFOUT_T16P_120") (pintype "bidirectional"))
    )
    (net (code "180") (name "unconnected-(IC6J-DIFFIO_RX_T19N{slash}DIFFOUT_T19N-Pad127)") (class "Default")
      (node (ref "IC6") (pin "127") (pinfunction "DIFFIO_RX_T19N/DIFFOUT_T19N_127") (pintype "bidirectional"))
    )
    (net (code "181") (name "unconnected-(IC6J-DIFFIO_RX_T19P{slash}DIFFOUT_T19P-Pad124)") (class "Default")
      (node (ref "IC6") (pin "124") (pinfunction "DIFFIO_RX_T19P/DIFFOUT_T19P_124") (pintype "bidirectional"))
    )
    (net (code "182") (name "unconnected-(IC6J-DIFFIO_RX_T26N{slash}DIFFOUT_T26N-Pad141)") (class "Default")
      (node (ref "IC6") (pin "141") (pinfunction "DIFFIO_RX_T26N/DIFFOUT_T26N_141") (pintype "bidirectional"))
    )
    (net (code "183") (name "unconnected-(IC6J-DIFFIO_RX_T26P{slash}DIFFOUT_T26P-Pad140)") (class "Default")
      (node (ref "IC6") (pin "140") (pinfunction "DIFFIO_RX_T26P/DIFFOUT_T26P_140") (pintype "bidirectional"))
    )
    (net (code "184") (name "unconnected-(IC6J-IO135-Pad135)") (class "Default")
      (node (ref "IC6") (pin "135") (pinfunction "IO135_135") (pintype "bidirectional"))
    )
    (net (code "185") (name "unconnected-(IC6J-VREFB8N0-Pad123)") (class "Default")
      (node (ref "IC6") (pin "123") (pinfunction "VREFB8N0_123") (pintype "input"))
    )
    (net (code "186") (name "unconnected-(J10-NC-PadN{slash}C)") (class "Default")
      (node (ref "J10") (pin "N/C") (pinfunction "NC_N/C") (pintype "bidirectional"))
    )
  )
)
